# Schematic3.net
KiCad netlist of a schematic drawn in EAGLE
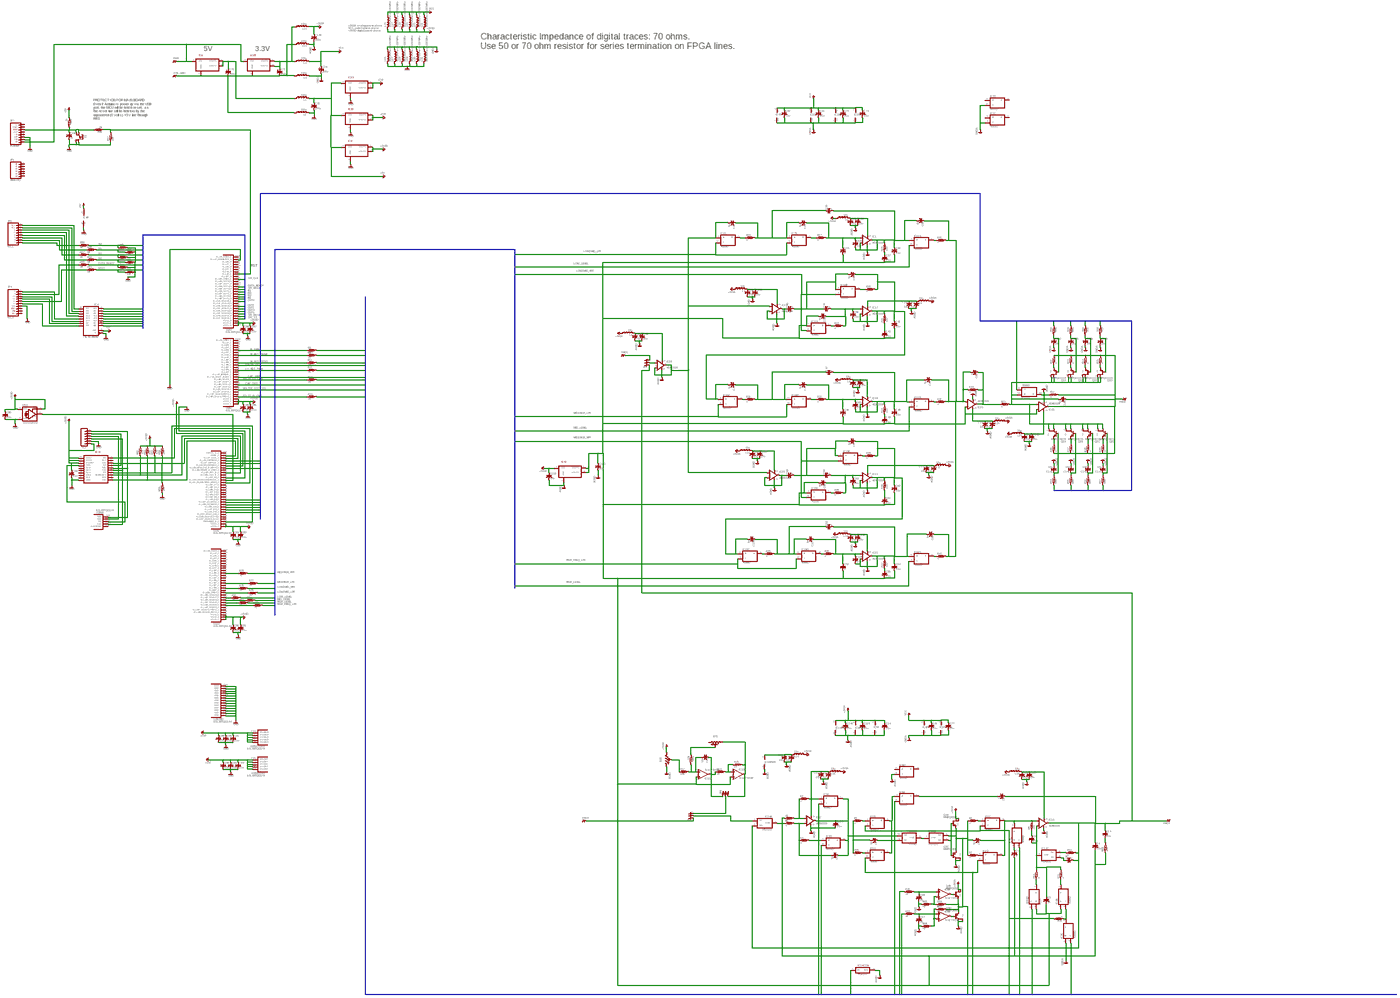
[diagram p0: schematic, sheet 1, overview]
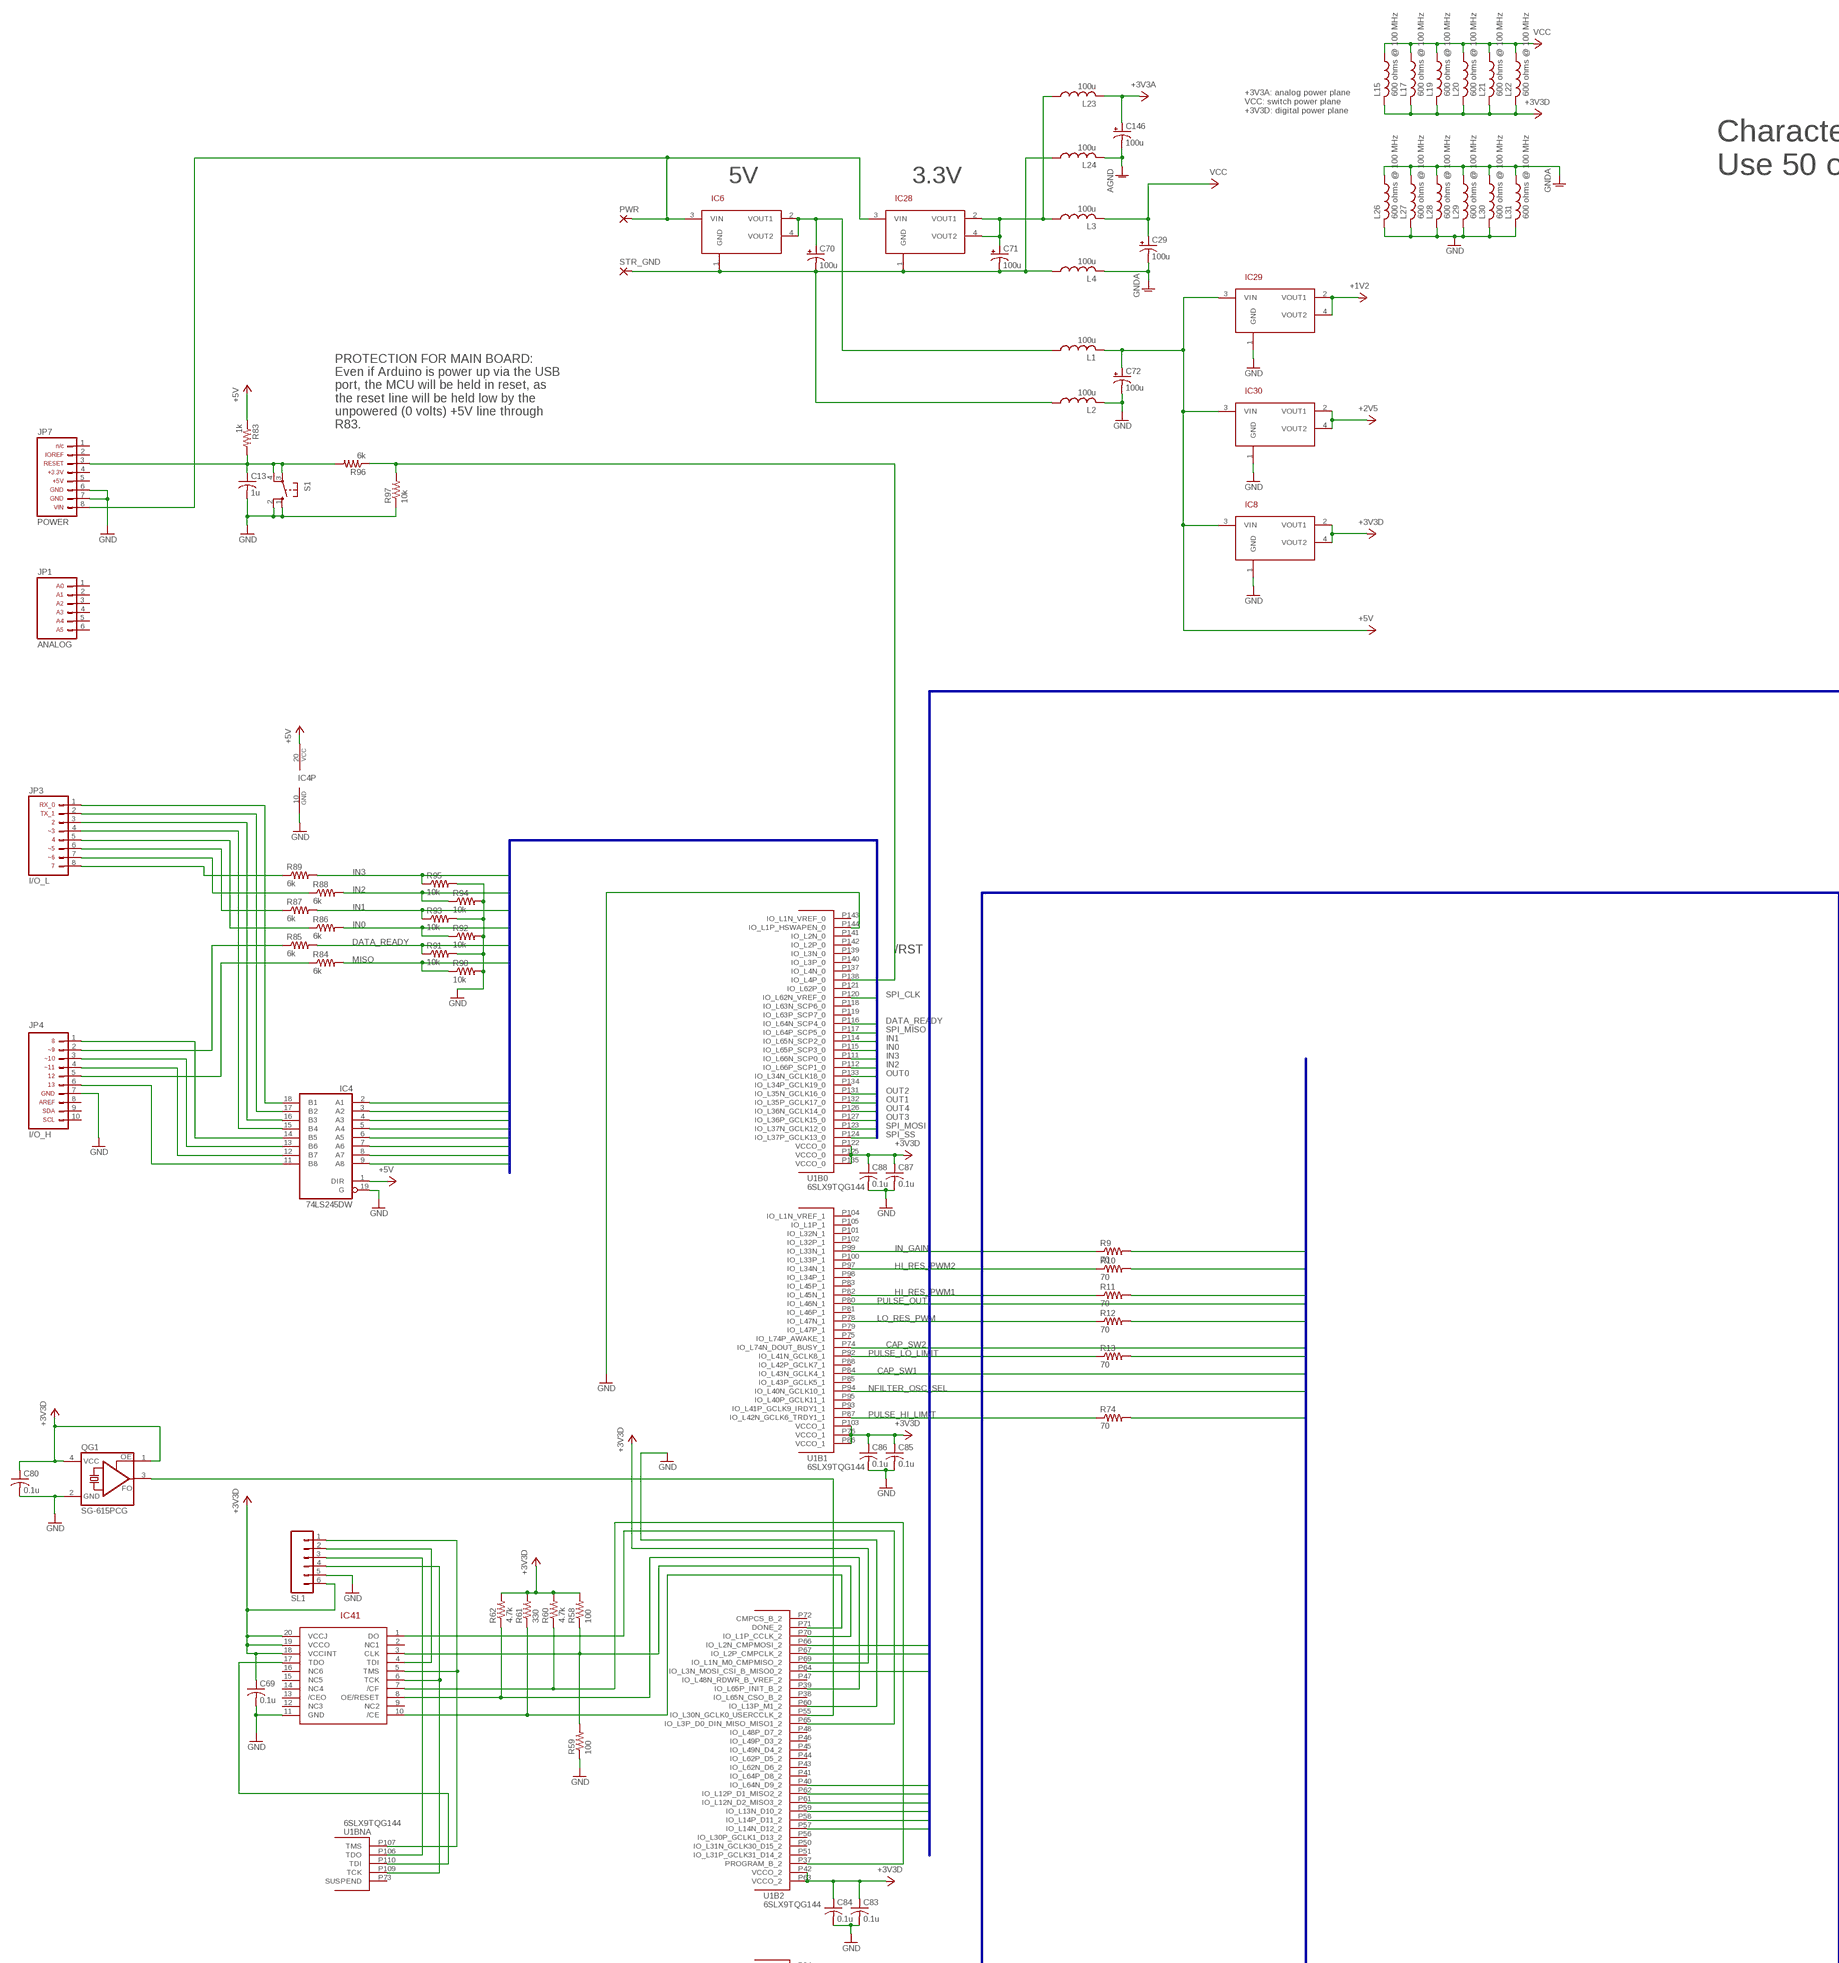
[diagram p1: schematic, sheet 1, part 1 of 6]
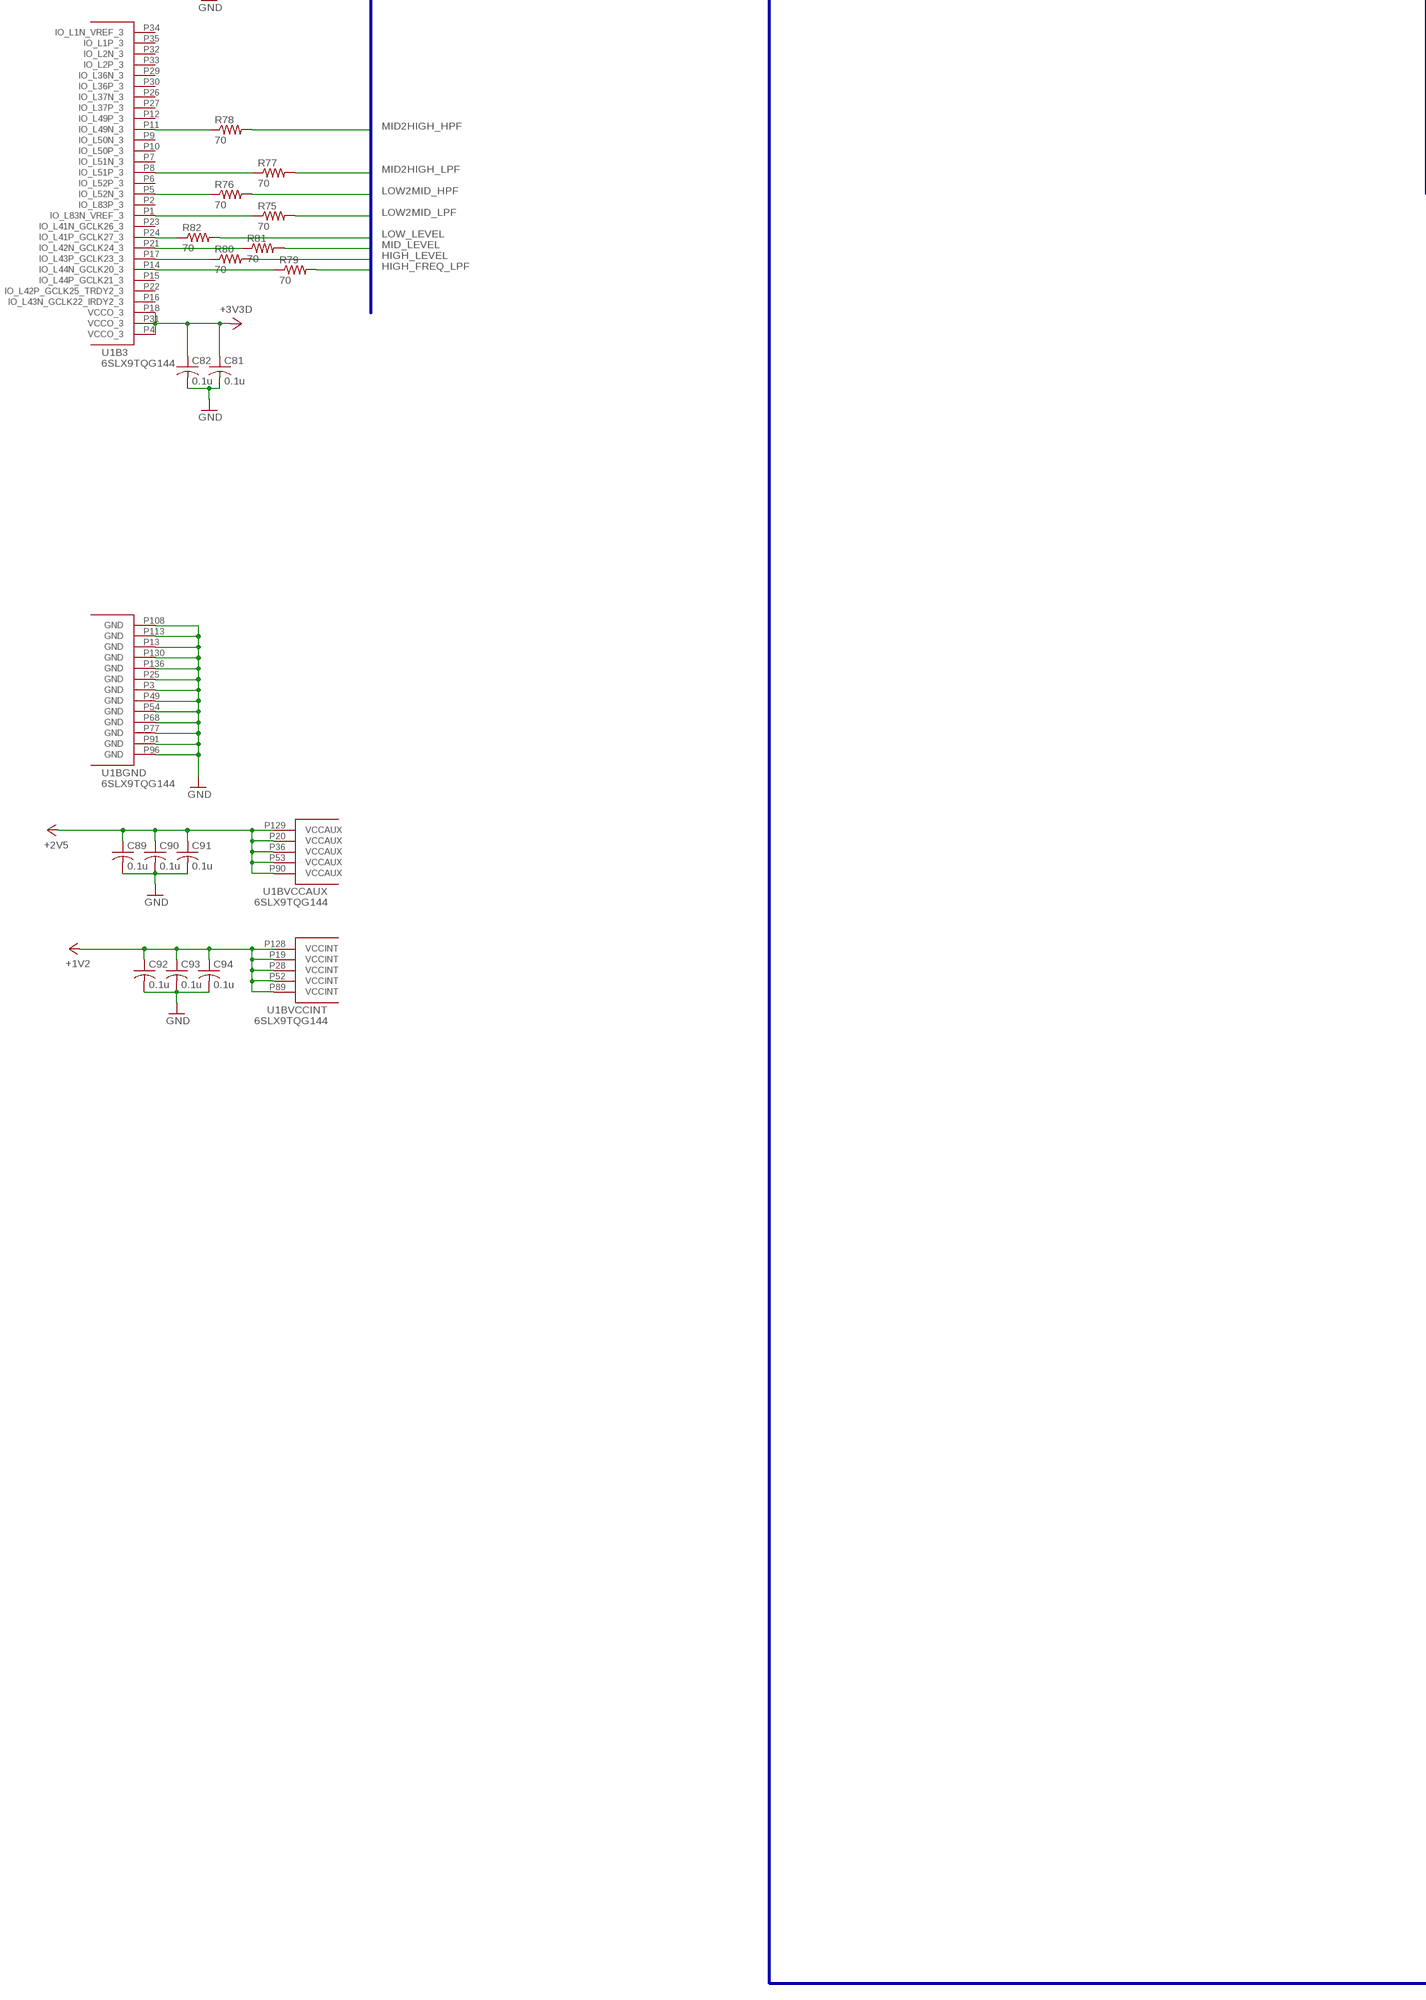
[diagram p2: schematic, sheet 1, part 2 of 6]
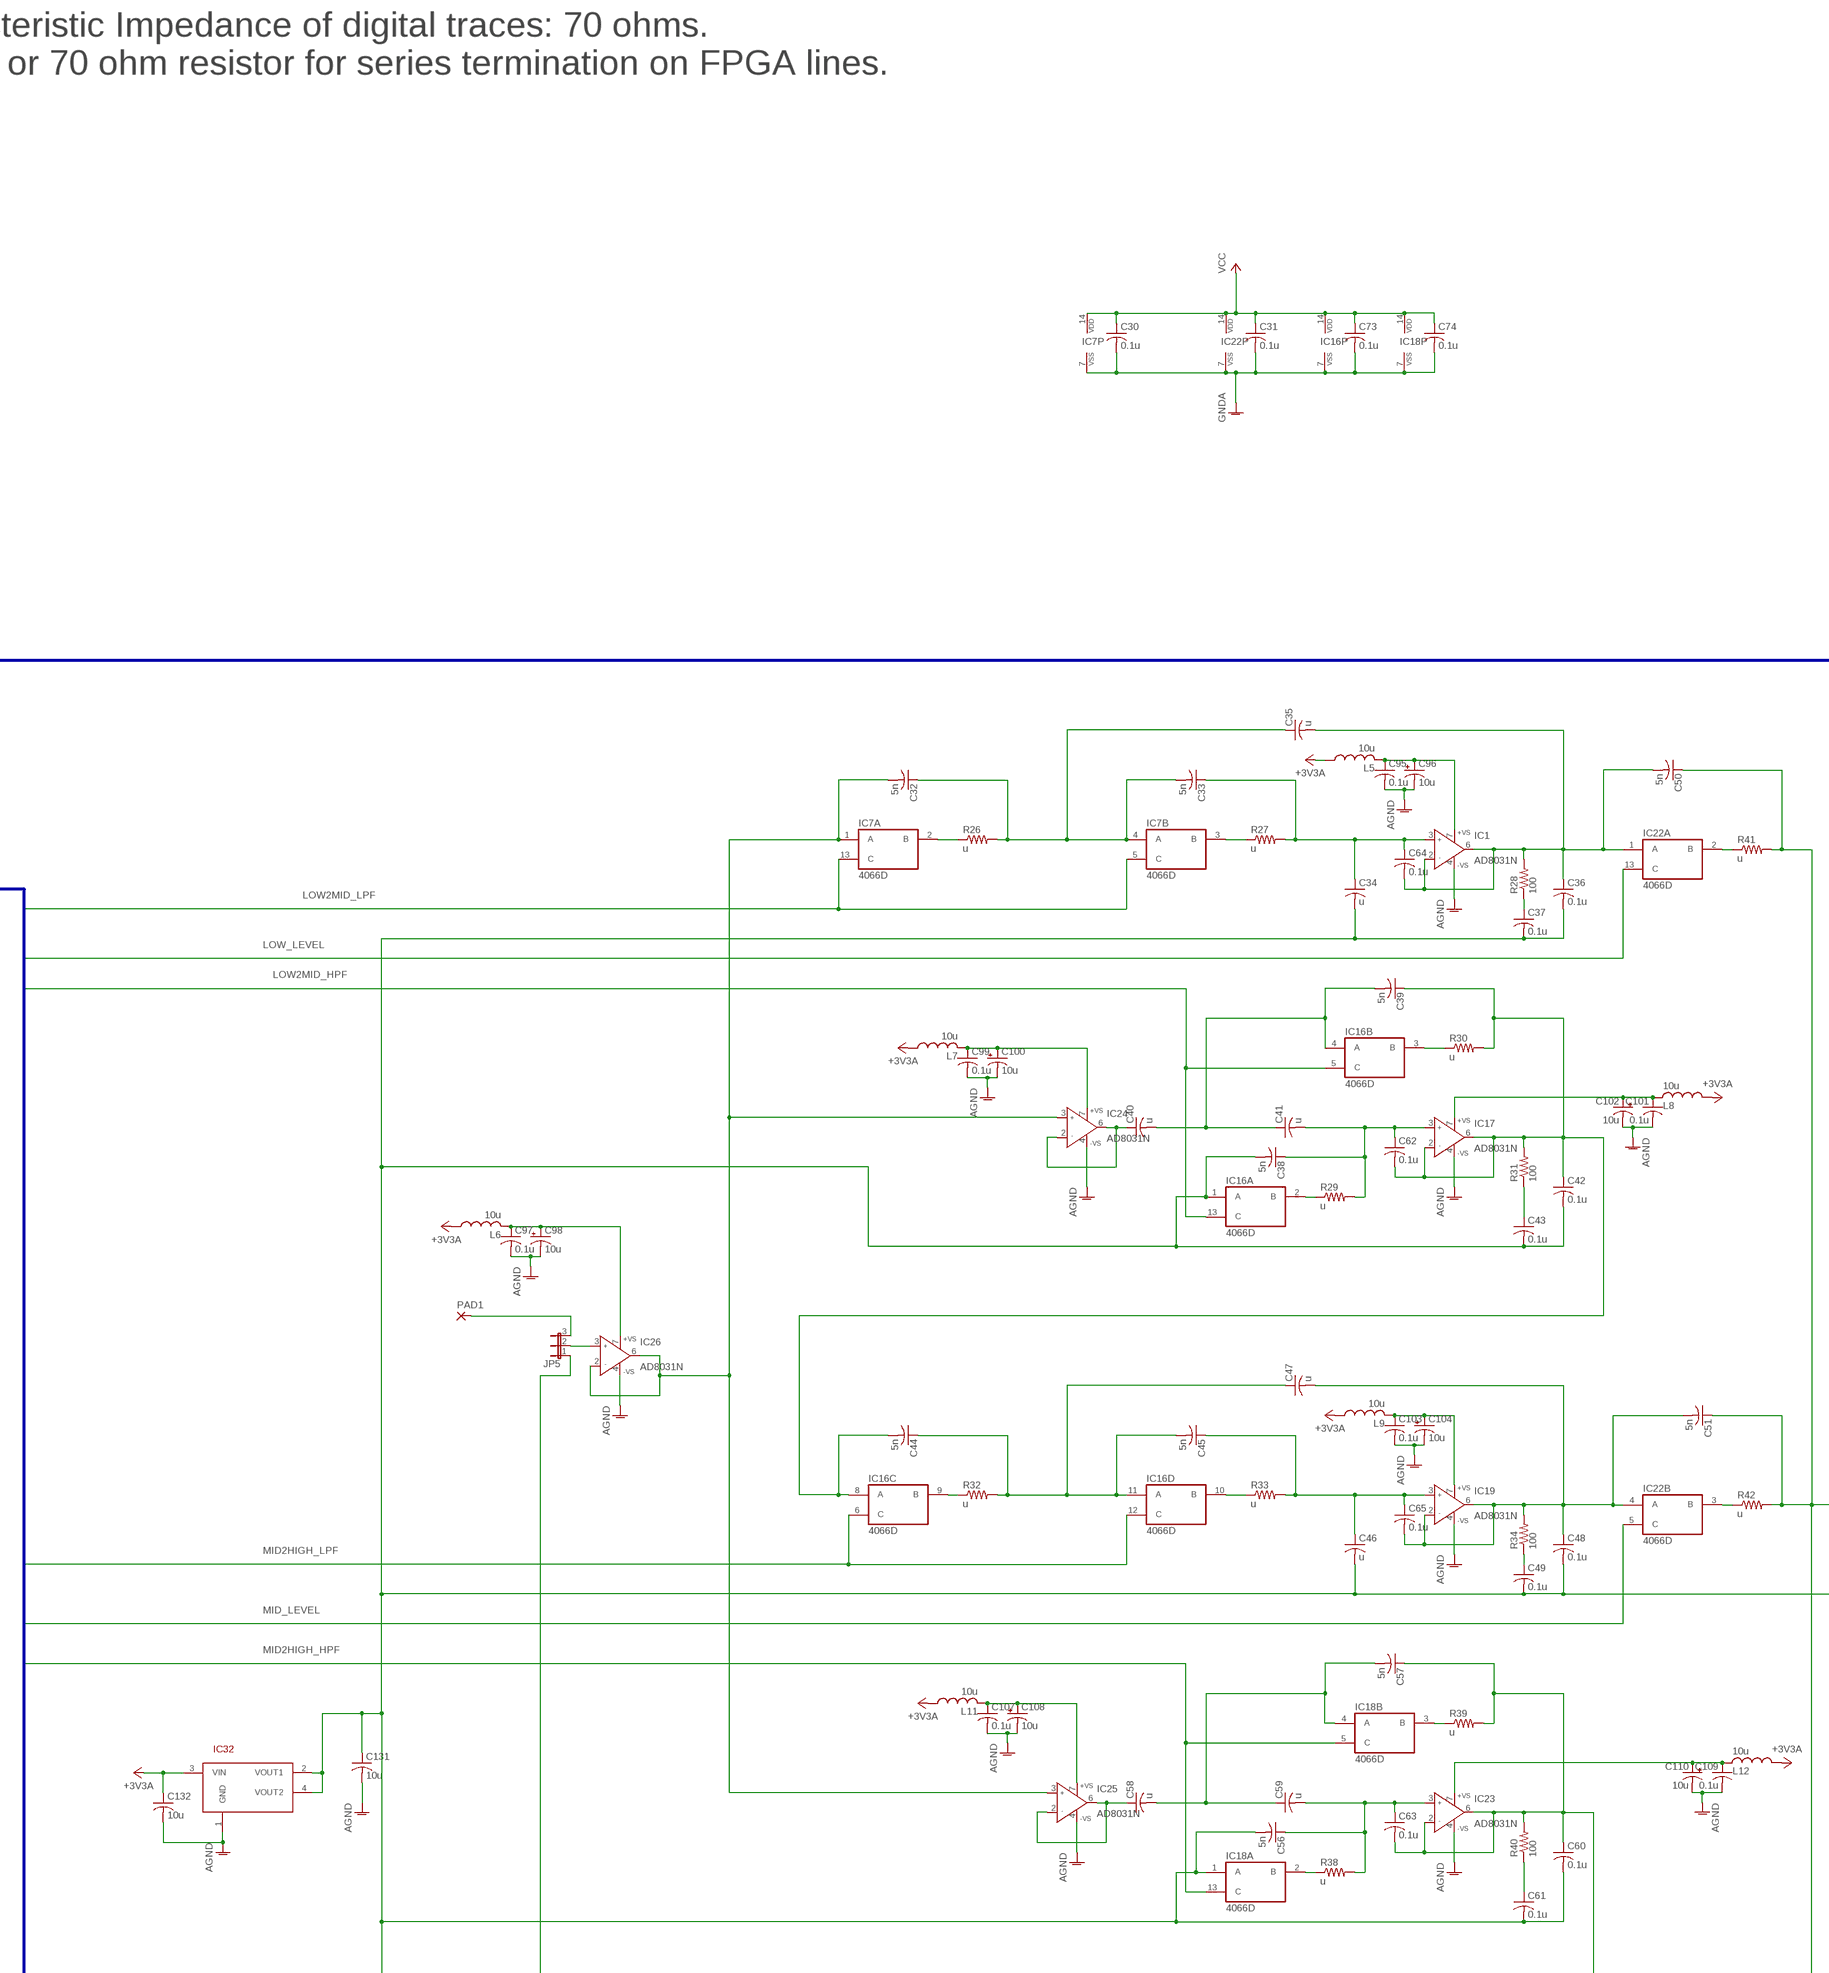
[diagram p3: schematic, sheet 1, part 3 of 6]
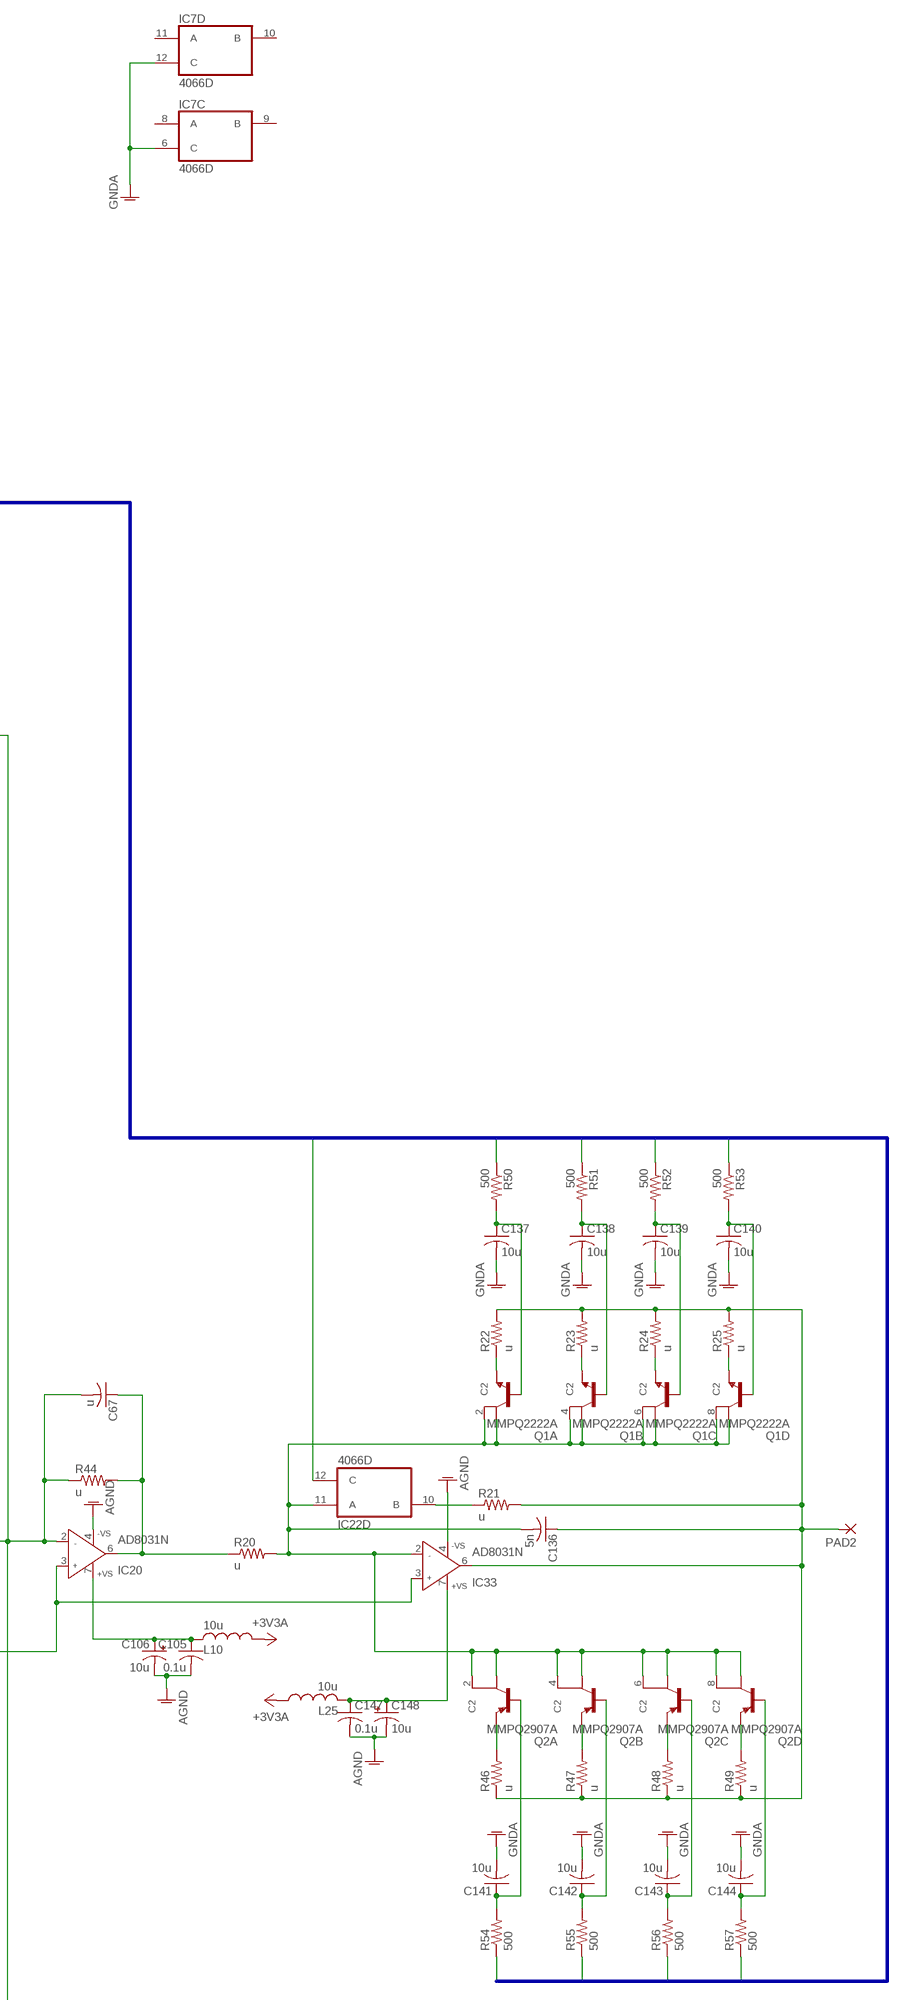
[diagram p4: schematic, sheet 1, part 4 of 6]
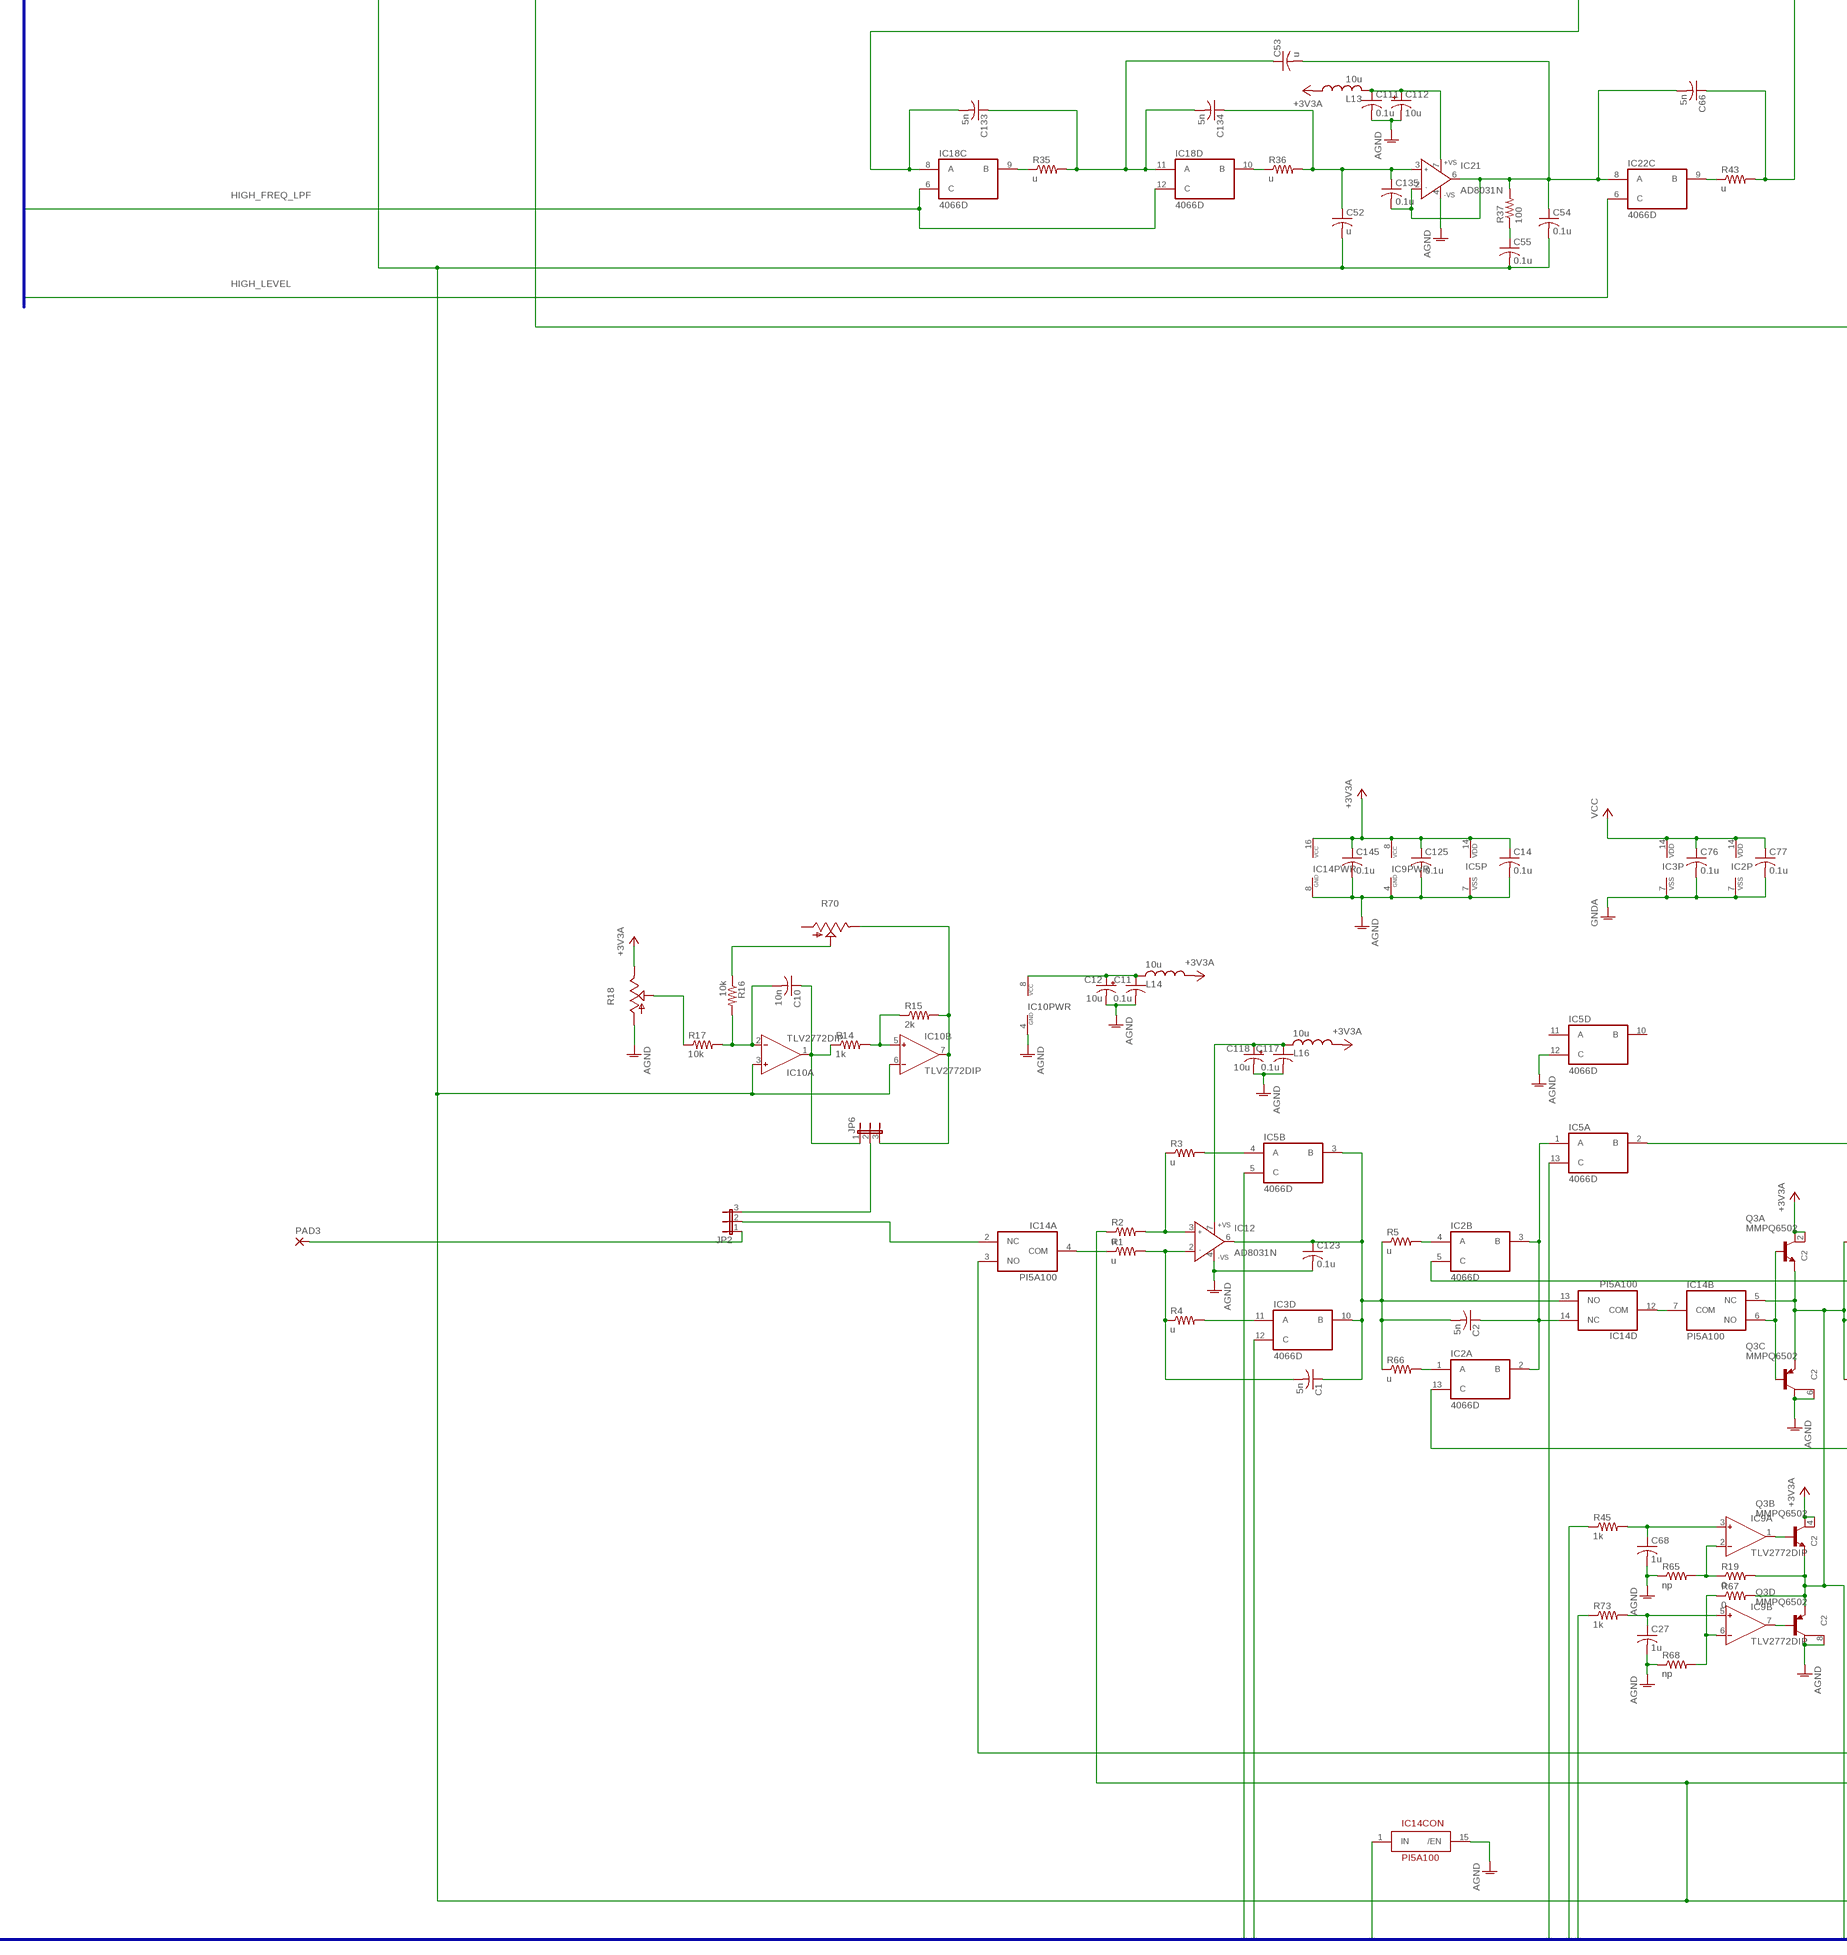
[diagram p5: schematic, sheet 1, part 5 of 6]
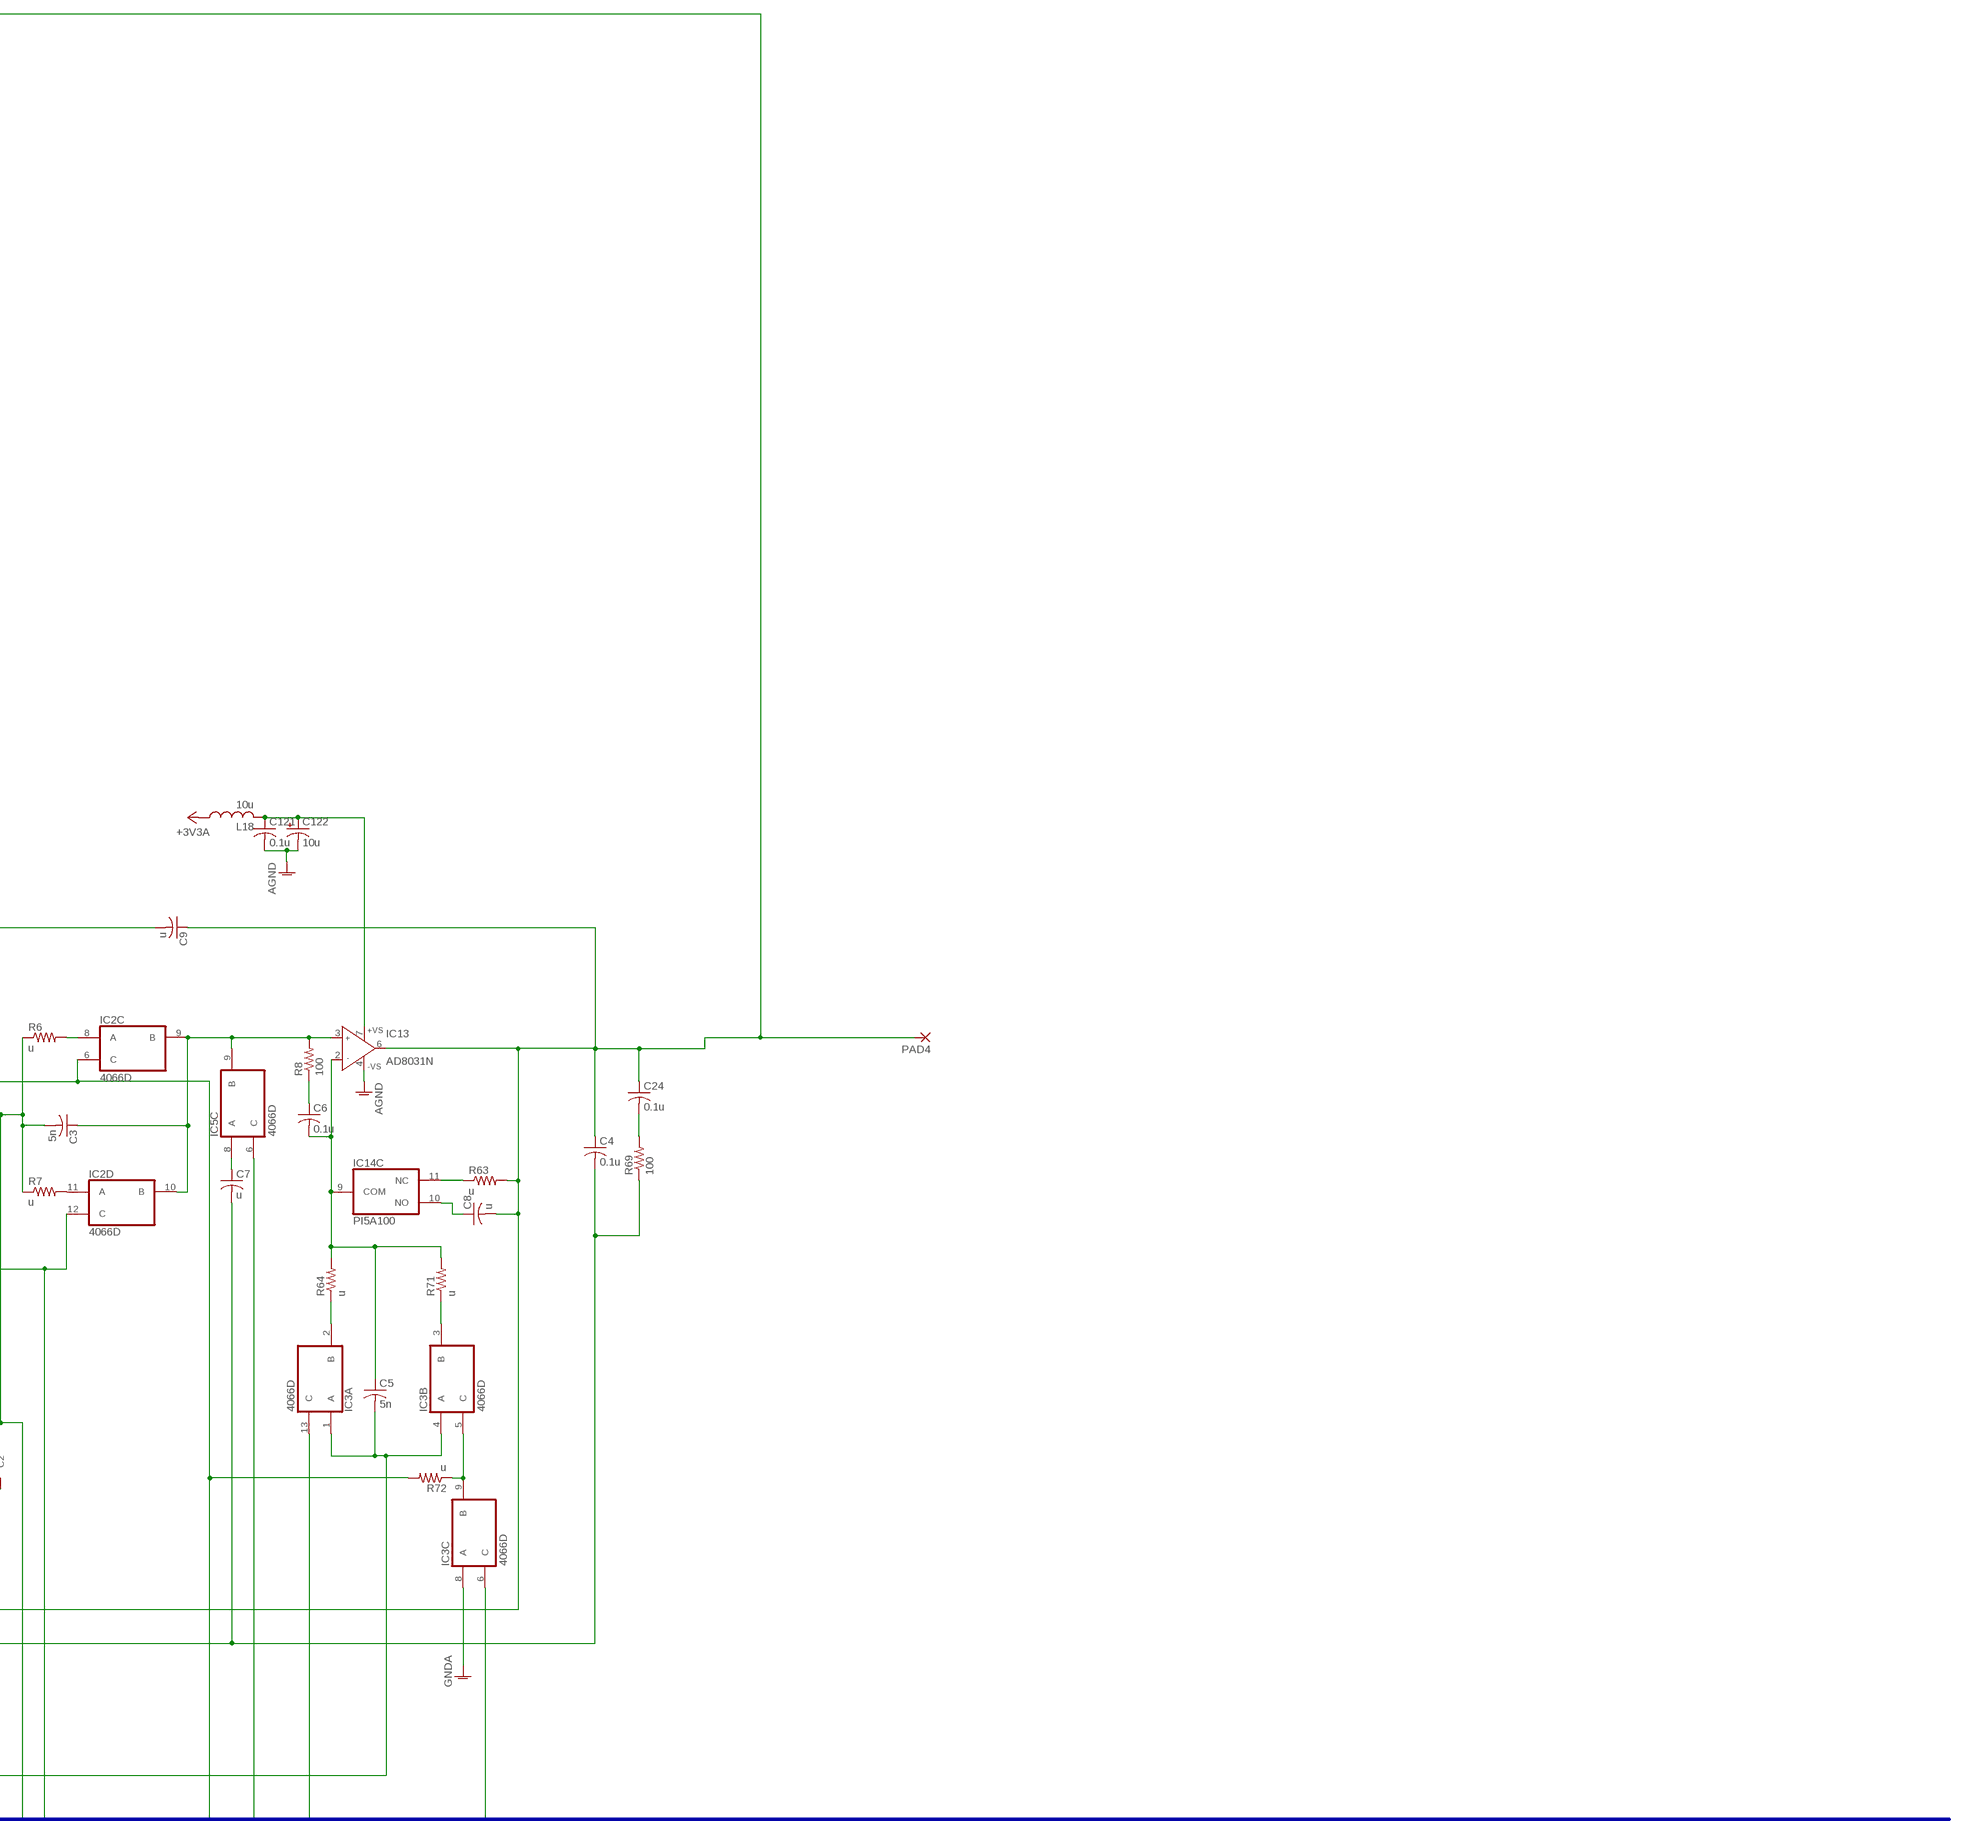
[diagram p6: schematic, sheet 1, part 6 of 6]

(export (version "E")
  (design (tool "Eeschema 10.0.6"))
  (components
    (comp (ref "C1")
      (value "5n")
      (footprint "eagle-import:C050-035X075")
      (libsource (lib "eagle-import") (part "C-US050-035X075"))
    )
    (comp (ref "C2")
      (value "5n")
      (footprint "eagle-import:C050-035X075")
      (libsource (lib "eagle-import") (part "C-US050-035X075"))
    )
    (comp (ref "C3")
      (value "5n")
      (footprint "eagle-import:C050-035X075")
      (libsource (lib "eagle-import") (part "C-US050-035X075"))
    )
    (comp (ref "C4")
      (value "0.1u")
      (footprint "eagle-import:C050-035X075")
      (libsource (lib "eagle-import") (part "C-US050-035X075"))
    )
    (comp (ref "C5")
      (value "5n")
      (footprint "eagle-import:C050-035X075")
      (libsource (lib "eagle-import") (part "C-US050-035X075"))
    )
    (comp (ref "C6")
      (value "0.1u")
      (footprint "eagle-import:C050-035X075")
      (libsource (lib "eagle-import") (part "C-US050-035X075"))
    )
    (comp (ref "C7")
      (value "u")
      (footprint "eagle-import:C050-035X075")
      (libsource (lib "eagle-import") (part "C-US050-035X075"))
    )
    (comp (ref "C8")
      (value "u")
      (footprint "eagle-import:C050-035X075")
      (libsource (lib "eagle-import") (part "C-US050-035X075"))
    )
    (comp (ref "C9")
      (value "u")
      (footprint "eagle-import:C050-035X075")
      (libsource (lib "eagle-import") (part "C-US050-035X075"))
    )
    (comp (ref "C10")
      (value "10n")
      (footprint "eagle-import:C050-035X075")
      (libsource (lib "eagle-import") (part "C-US050-035X075"))
    )
    (comp (ref "C11")
      (value "0.1u")
      (footprint "eagle-import:C0805")
      (libsource (lib "eagle-import") (part "C-USC0805"))
    )
    (comp (ref "C12")
      (value "10u")
      (footprint "eagle-import:A_3216-18R")
      (libsource (lib "eagle-import") (part "CPOL-USA/3216-18R"))
    )
    (comp (ref "C13")
      (value "1u")
      (footprint "eagle-import:C0805")
      (libsource (lib "eagle-import") (part "C-USC0805"))
    )
    (comp (ref "C14")
      (value "0.1u")
      (footprint "eagle-import:C0805")
      (libsource (lib "eagle-import") (part "C-USC0805"))
    )
    (comp (ref "C24")
      (value "0.1u")
      (footprint "eagle-import:C050-035X075")
      (libsource (lib "eagle-import") (part "C-US050-035X075"))
    )
    (comp (ref "C27")
      (value "1u")
      (footprint "eagle-import:C0805")
      (libsource (lib "eagle-import") (part "C-USC0805"))
    )
    (comp (ref "C29")
      (value "100u")
      (footprint "eagle-import:B_3528-21R")
      (libsource (lib "eagle-import") (part "CPOL-USB/3528-21R"))
    )
    (comp (ref "C30")
      (value "0.1u")
      (footprint "eagle-import:C0805")
      (libsource (lib "eagle-import") (part "C-USC0805"))
    )
    (comp (ref "C31")
      (value "0.1u")
      (footprint "eagle-import:C0805")
      (libsource (lib "eagle-import") (part "C-USC0805"))
    )
    (comp (ref "C32")
      (value "5n")
      (footprint "eagle-import:C050-035X075")
      (libsource (lib "eagle-import") (part "C-US050-035X075"))
    )
    (comp (ref "C33")
      (value "5n")
      (footprint "eagle-import:C050-035X075")
      (libsource (lib "eagle-import") (part "C-US050-035X075"))
    )
    (comp (ref "C34")
      (value "u")
      (footprint "eagle-import:C050-035X075")
      (libsource (lib "eagle-import") (part "C-US050-035X075"))
    )
    (comp (ref "C35")
      (value "u")
      (footprint "eagle-import:C050-035X075")
      (libsource (lib "eagle-import") (part "C-US050-035X075"))
    )
    (comp (ref "C36")
      (value "0.1u")
      (footprint "eagle-import:C050-035X075")
      (libsource (lib "eagle-import") (part "C-US050-035X075"))
    )
    (comp (ref "C37")
      (value "0.1u")
      (footprint "eagle-import:C050-035X075")
      (libsource (lib "eagle-import") (part "C-US050-035X075"))
    )
    (comp (ref "C38")
      (value "5n")
      (footprint "eagle-import:C050-035X075")
      (libsource (lib "eagle-import") (part "C-US050-035X075"))
    )
    (comp (ref "C39")
      (value "5n")
      (footprint "eagle-import:C050-035X075")
      (libsource (lib "eagle-import") (part "C-US050-035X075"))
    )
    (comp (ref "C40")
      (value "u")
      (footprint "eagle-import:C050-035X075")
      (libsource (lib "eagle-import") (part "C-US050-035X075"))
    )
    (comp (ref "C41")
      (value "u")
      (footprint "eagle-import:C050-035X075")
      (libsource (lib "eagle-import") (part "C-US050-035X075"))
    )
    (comp (ref "C42")
      (value "0.1u")
      (footprint "eagle-import:C050-035X075")
      (libsource (lib "eagle-import") (part "C-US050-035X075"))
    )
    (comp (ref "C43")
      (value "0.1u")
      (footprint "eagle-import:C050-035X075")
      (libsource (lib "eagle-import") (part "C-US050-035X075"))
    )
    (comp (ref "C44")
      (value "5n")
      (footprint "eagle-import:C050-035X075")
      (libsource (lib "eagle-import") (part "C-US050-035X075"))
    )
    (comp (ref "C45")
      (value "5n")
      (footprint "eagle-import:C050-035X075")
      (libsource (lib "eagle-import") (part "C-US050-035X075"))
    )
    (comp (ref "C46")
      (value "u")
      (footprint "eagle-import:C050-035X075")
      (libsource (lib "eagle-import") (part "C-US050-035X075"))
    )
    (comp (ref "C47")
      (value "u")
      (footprint "eagle-import:C050-035X075")
      (libsource (lib "eagle-import") (part "C-US050-035X075"))
    )
    (comp (ref "C48")
      (value "0.1u")
      (footprint "eagle-import:C050-035X075")
      (libsource (lib "eagle-import") (part "C-US050-035X075"))
    )
    (comp (ref "C49")
      (value "0.1u")
      (footprint "eagle-import:C050-035X075")
      (libsource (lib "eagle-import") (part "C-US050-035X075"))
    )
    (comp (ref "C50")
      (value "5n")
      (footprint "eagle-import:C050-035X075")
      (libsource (lib "eagle-import") (part "C-US050-035X075"))
    )
    (comp (ref "C51")
      (value "5n")
      (footprint "eagle-import:C050-035X075")
      (libsource (lib "eagle-import") (part "C-US050-035X075"))
    )
    (comp (ref "C52")
      (value "u")
      (footprint "eagle-import:C050-035X075")
      (libsource (lib "eagle-import") (part "C-US050-035X075"))
    )
    (comp (ref "C53")
      (value "u")
      (footprint "eagle-import:C050-035X075")
      (libsource (lib "eagle-import") (part "C-US050-035X075"))
    )
    (comp (ref "C54")
      (value "0.1u")
      (footprint "eagle-import:C050-035X075")
      (libsource (lib "eagle-import") (part "C-US050-035X075"))
    )
    (comp (ref "C55")
      (value "0.1u")
      (footprint "eagle-import:C050-035X075")
      (libsource (lib "eagle-import") (part "C-US050-035X075"))
    )
    (comp (ref "C56")
      (value "5n")
      (footprint "eagle-import:C050-035X075")
      (libsource (lib "eagle-import") (part "C-US050-035X075"))
    )
    (comp (ref "C57")
      (value "5n")
      (footprint "eagle-import:C050-035X075")
      (libsource (lib "eagle-import") (part "C-US050-035X075"))
    )
    (comp (ref "C58")
      (value "u")
      (footprint "eagle-import:C050-035X075")
      (libsource (lib "eagle-import") (part "C-US050-035X075"))
    )
    (comp (ref "C59")
      (value "u")
      (footprint "eagle-import:C050-035X075")
      (libsource (lib "eagle-import") (part "C-US050-035X075"))
    )
    (comp (ref "C60")
      (value "0.1u")
      (footprint "eagle-import:C050-035X075")
      (libsource (lib "eagle-import") (part "C-US050-035X075"))
    )
    (comp (ref "C61")
      (value "0.1u")
      (footprint "eagle-import:C050-035X075")
      (libsource (lib "eagle-import") (part "C-US050-035X075"))
    )
    (comp (ref "C62")
      (value "0.1u")
      (footprint "eagle-import:C050-035X075")
      (libsource (lib "eagle-import") (part "C-US050-035X075"))
    )
    (comp (ref "C63")
      (value "0.1u")
      (footprint "eagle-import:C050-035X075")
      (libsource (lib "eagle-import") (part "C-US050-035X075"))
    )
    (comp (ref "C64")
      (value "0.1u")
      (footprint "eagle-import:C050-035X075")
      (libsource (lib "eagle-import") (part "C-US050-035X075"))
    )
    (comp (ref "C65")
      (value "0.1u")
      (footprint "eagle-import:C050-035X075")
      (libsource (lib "eagle-import") (part "C-US050-035X075"))
    )
    (comp (ref "C66")
      (value "5n")
      (footprint "eagle-import:C050-035X075")
      (libsource (lib "eagle-import") (part "C-US050-035X075"))
    )
    (comp (ref "C67")
      (value "u")
      (footprint "eagle-import:C050-035X075")
      (libsource (lib "eagle-import") (part "C-US050-035X075"))
    )
    (comp (ref "C68")
      (value "1u")
      (footprint "eagle-import:C0805")
      (libsource (lib "eagle-import") (part "C-USC0805"))
    )
    (comp (ref "C69")
      (value "0.1u")
      (footprint "eagle-import:C0805")
      (libsource (lib "eagle-import") (part "C-USC0805"))
    )
    (comp (ref "C70")
      (value "100u")
      (footprint "eagle-import:CT3528")
      (libsource (lib "eagle-import") (part "CPOL-USCT3528"))
    )
    (comp (ref "C71")
      (value "100u")
      (footprint "eagle-import:CT3528")
      (libsource (lib "eagle-import") (part "CPOL-USCT3528"))
    )
    (comp (ref "C72")
      (value "100u")
      (footprint "eagle-import:B_3528-21R")
      (libsource (lib "eagle-import") (part "CPOL-USB/3528-21R"))
    )
    (comp (ref "C73")
      (value "0.1u")
      (footprint "eagle-import:C0805")
      (libsource (lib "eagle-import") (part "C-USC0805"))
    )
    (comp (ref "C74")
      (value "0.1u")
      (footprint "eagle-import:C0805")
      (libsource (lib "eagle-import") (part "C-USC0805"))
    )
    (comp (ref "C76")
      (value "0.1u")
      (footprint "eagle-import:C0805")
      (libsource (lib "eagle-import") (part "C-USC0805"))
    )
    (comp (ref "C77")
      (value "0.1u")
      (footprint "eagle-import:C0805")
      (libsource (lib "eagle-import") (part "C-USC0805"))
    )
    (comp (ref "C80")
      (value "0.1u")
      (footprint "eagle-import:C0805")
      (libsource (lib "eagle-import") (part "C-USC0805"))
    )
    (comp (ref "C81")
      (value "0.1u")
      (footprint "eagle-import:C0805")
      (libsource (lib "eagle-import") (part "C-USC0805"))
    )
    (comp (ref "C82")
      (value "0.1u")
      (footprint "eagle-import:C0805")
      (libsource (lib "eagle-import") (part "C-USC0805"))
    )
    (comp (ref "C83")
      (value "0.1u")
      (footprint "eagle-import:C0805")
      (libsource (lib "eagle-import") (part "C-USC0805"))
    )
    (comp (ref "C84")
      (value "0.1u")
      (footprint "eagle-import:C0805")
      (libsource (lib "eagle-import") (part "C-USC0805"))
    )
    (comp (ref "C85")
      (value "0.1u")
      (footprint "eagle-import:C0805")
      (libsource (lib "eagle-import") (part "C-USC0805"))
    )
    (comp (ref "C86")
      (value "0.1u")
      (footprint "eagle-import:C0805")
      (libsource (lib "eagle-import") (part "C-USC0805"))
    )
    (comp (ref "C87")
      (value "0.1u")
      (footprint "eagle-import:C0805")
      (libsource (lib "eagle-import") (part "C-USC0805"))
    )
    (comp (ref "C88")
      (value "0.1u")
      (footprint "eagle-import:C0805")
      (libsource (lib "eagle-import") (part "C-USC0805"))
    )
    (comp (ref "C89")
      (value "0.1u")
      (footprint "eagle-import:C0805")
      (libsource (lib "eagle-import") (part "C-USC0805"))
    )
    (comp (ref "C90")
      (value "0.1u")
      (footprint "eagle-import:C0805")
      (libsource (lib "eagle-import") (part "C-USC0805"))
    )
    (comp (ref "C91")
      (value "0.1u")
      (footprint "eagle-import:C0805")
      (libsource (lib "eagle-import") (part "C-USC0805"))
    )
    (comp (ref "C92")
      (value "0.1u")
      (footprint "eagle-import:C0805")
      (libsource (lib "eagle-import") (part "C-USC0805"))
    )
    (comp (ref "C93")
      (value "0.1u")
      (footprint "eagle-import:C0805")
      (libsource (lib "eagle-import") (part "C-USC0805"))
    )
    (comp (ref "C94")
      (value "0.1u")
      (footprint "eagle-import:C0805")
      (libsource (lib "eagle-import") (part "C-USC0805"))
    )
    (comp (ref "C95")
      (value "0.1u")
      (footprint "eagle-import:C0805")
      (libsource (lib "eagle-import") (part "C-USC0805"))
    )
    (comp (ref "C96")
      (value "10u")
      (footprint "eagle-import:A_3216-18R")
      (libsource (lib "eagle-import") (part "CPOL-USA/3216-18R"))
    )
    (comp (ref "C97")
      (value "0.1u")
      (footprint "eagle-import:C0805")
      (libsource (lib "eagle-import") (part "C-USC0805"))
    )
    (comp (ref "C98")
      (value "10u")
      (footprint "eagle-import:A_3216-18R")
      (libsource (lib "eagle-import") (part "CPOL-USA/3216-18R"))
    )
    (comp (ref "C99")
      (value "0.1u")
      (footprint "eagle-import:C0805")
      (libsource (lib "eagle-import") (part "C-USC0805"))
    )
    (comp (ref "C100")
      (value "10u")
      (footprint "eagle-import:A_3216-18R")
      (libsource (lib "eagle-import") (part "CPOL-USA/3216-18R"))
    )
    (comp (ref "C101")
      (value "0.1u")
      (footprint "eagle-import:C0805")
      (libsource (lib "eagle-import") (part "C-USC0805"))
    )
    (comp (ref "C102")
      (value "10u")
      (footprint "eagle-import:A_3216-18R")
      (libsource (lib "eagle-import") (part "CPOL-USA/3216-18R"))
    )
    (comp (ref "C103")
      (value "0.1u")
      (footprint "eagle-import:C0805")
      (libsource (lib "eagle-import") (part "C-USC0805"))
    )
    (comp (ref "C104")
      (value "10u")
      (footprint "eagle-import:A_3216-18R")
      (libsource (lib "eagle-import") (part "CPOL-USA/3216-18R"))
    )
    (comp (ref "C105")
      (value "0.1u")
      (footprint "eagle-import:C0805")
      (libsource (lib "eagle-import") (part "C-USC0805"))
    )
    (comp (ref "C106")
      (value "10u")
      (footprint "eagle-import:A_3216-18R")
      (libsource (lib "eagle-import") (part "CPOL-USA/3216-18R"))
    )
    (comp (ref "C107")
      (value "0.1u")
      (footprint "eagle-import:C0805")
      (libsource (lib "eagle-import") (part "C-USC0805"))
    )
    (comp (ref "C108")
      (value "10u")
      (footprint "eagle-import:A_3216-18R")
      (libsource (lib "eagle-import") (part "CPOL-USA/3216-18R"))
    )
    (comp (ref "C109")
      (value "0.1u")
      (footprint "eagle-import:C0805")
      (libsource (lib "eagle-import") (part "C-USC0805"))
    )
    (comp (ref "C110")
      (value "10u")
      (footprint "eagle-import:A_3216-18R")
      (libsource (lib "eagle-import") (part "CPOL-USA/3216-18R"))
    )
    (comp (ref "C111")
      (value "0.1u")
      (footprint "eagle-import:C0805")
      (libsource (lib "eagle-import") (part "C-USC0805"))
    )
    (comp (ref "C112")
      (value "10u")
      (footprint "eagle-import:A_3216-18R")
      (libsource (lib "eagle-import") (part "CPOL-USA/3216-18R"))
    )
    (comp (ref "C117")
      (value "0.1u")
      (footprint "eagle-import:C0805")
      (libsource (lib "eagle-import") (part "C-USC0805"))
    )
    (comp (ref "C118")
      (value "10u")
      (footprint "eagle-import:A_3216-18R")
      (libsource (lib "eagle-import") (part "CPOL-USA/3216-18R"))
    )
    (comp (ref "C121")
      (value "0.1u")
      (footprint "eagle-import:C0805")
      (libsource (lib "eagle-import") (part "C-USC0805"))
    )
    (comp (ref "C122")
      (value "10u")
      (footprint "eagle-import:A_3216-18R")
      (libsource (lib "eagle-import") (part "CPOL-USA/3216-18R"))
    )
    (comp (ref "C123")
      (value "0.1u")
      (footprint "eagle-import:C050-035X075")
      (libsource (lib "eagle-import") (part "C-US050-035X075"))
    )
    (comp (ref "C125")
      (value "0.1u")
      (footprint "eagle-import:C0805")
      (libsource (lib "eagle-import") (part "C-USC0805"))
    )
    (comp (ref "C131")
      (value "10u")
      (footprint "eagle-import:C0805")
      (libsource (lib "eagle-import") (part "C-USC0805"))
    )
    (comp (ref "C132")
      (value "10u")
      (footprint "eagle-import:C0805")
      (libsource (lib "eagle-import") (part "C-USC0805"))
    )
    (comp (ref "C133")
      (value "5n")
      (footprint "eagle-import:C050-035X075")
      (libsource (lib "eagle-import") (part "C-US050-035X075"))
    )
    (comp (ref "C134")
      (value "5n")
      (footprint "eagle-import:C050-035X075")
      (libsource (lib "eagle-import") (part "C-US050-035X075"))
    )
    (comp (ref "C135")
      (value "0.1u")
      (footprint "eagle-import:C050-035X075")
      (libsource (lib "eagle-import") (part "C-US050-035X075"))
    )
    (comp (ref "C136")
      (value "5n")
      (footprint "eagle-import:C050-035X075")
      (libsource (lib "eagle-import") (part "C-US050-035X075"))
    )
    (comp (ref "C137")
      (value "10u")
      (footprint "eagle-import:C050-035X075")
      (libsource (lib "eagle-import") (part "C-US050-035X075"))
    )
    (comp (ref "C138")
      (value "10u")
      (footprint "eagle-import:C050-035X075")
      (libsource (lib "eagle-import") (part "C-US050-035X075"))
    )
    (comp (ref "C139")
      (value "10u")
      (footprint "eagle-import:C050-035X075")
      (libsource (lib "eagle-import") (part "C-US050-035X075"))
    )
    (comp (ref "C140")
      (value "10u")
      (footprint "eagle-import:C050-035X075")
      (libsource (lib "eagle-import") (part "C-US050-035X075"))
    )
    (comp (ref "C141")
      (value "10u")
      (footprint "eagle-import:C050-035X075")
      (libsource (lib "eagle-import") (part "C-US050-035X075"))
    )
    (comp (ref "C142")
      (value "10u")
      (footprint "eagle-import:C050-035X075")
      (libsource (lib "eagle-import") (part "C-US050-035X075"))
    )
    (comp (ref "C143")
      (value "10u")
      (footprint "eagle-import:C050-035X075")
      (libsource (lib "eagle-import") (part "C-US050-035X075"))
    )
    (comp (ref "C144")
      (value "10u")
      (footprint "eagle-import:C050-035X075")
      (libsource (lib "eagle-import") (part "C-US050-035X075"))
    )
    (comp (ref "C145")
      (value "0.1u")
      (footprint "eagle-import:C0805")
      (libsource (lib "eagle-import") (part "C-USC0805"))
    )
    (comp (ref "C146")
      (value "100u")
      (footprint "eagle-import:B_3528-21R")
      (libsource (lib "eagle-import") (part "CPOL-USB/3528-21R"))
    )
    (comp (ref "C147")
      (value "0.1u")
      (footprint "eagle-import:C0805")
      (libsource (lib "eagle-import") (part "C-USC0805"))
    )
    (comp (ref "C148")
      (value "10u")
      (footprint "eagle-import:A_3216-18R")
      (libsource (lib "eagle-import") (part "CPOL-USA/3216-18R"))
    )
    (comp (ref "IC1")
      (value "AD8031N")
      (footprint "eagle-import:DIL08")
      (fields (field (name "MPN") "AD8031BNZ"))
      (libsource (lib "eagle-import") (part "AD8031N"))
    )
    (comp (ref "IC2")
      (value "4066D")
      (footprint "eagle-import:SO14")
      (libsource (lib "eagle-import") (part "4066D"))
    )
    (comp (ref "IC3")
      (value "4066D")
      (footprint "eagle-import:SO14")
      (libsource (lib "eagle-import") (part "4066D"))
    )
    (comp (ref "IC4")
      (value "74LS245DW")
      (footprint "eagle-import:SO20W")
      (libsource (lib "eagle-import") (part "74245DWLS"))
    )
    (comp (ref "IC5")
      (value "4066D")
      (footprint "eagle-import:SO14")
      (libsource (lib "eagle-import") (part "4066D"))
    )
    (comp (ref "IC6")
      (value "TLV1117")
      (footprint "eagle-import:SOT223-4")
      (libsource (lib "eagle-import") (part "texas2_TLV1117"))
    )
    (comp (ref "IC7")
      (value "4066D")
      (footprint "eagle-import:SO14")
      (libsource (lib "eagle-import") (part "4066D"))
    )
    (comp (ref "IC8")
      (value "TLV1117")
      (footprint "eagle-import:SOT223-4")
      (libsource (lib "eagle-import") (part "TLV1117"))
    )
    (comp (ref "IC9")
      (value "TLV2772DIP")
      (footprint "eagle-import:DIL08")
      (libsource (lib "eagle-import") (part "TLV2772DIP"))
    )
    (comp (ref "IC10")
      (value "TLV2772DIP")
      (footprint "eagle-import:DIL08")
      (libsource (lib "eagle-import") (part "TLV2772DIP"))
    )
    (comp (ref "IC12")
      (value "AD8031N")
      (footprint "eagle-import:DIL08")
      (fields (field (name "MPN") "AD8031BNZ"))
      (libsource (lib "eagle-import") (part "AD8031N"))
    )
    (comp (ref "IC13")
      (value "AD8031N")
      (footprint "eagle-import:DIL08")
      (fields (field (name "MPN") "AD8031BNZ"))
      (libsource (lib "eagle-import") (part "AD8031N"))
    )
    (comp (ref "IC14")
      (value "PI5A100")
      (footprint "eagle-import:SO-16")
      (libsource (lib "eagle-import") (part "PI5A100"))
    )
    (comp (ref "IC16")
      (value "4066D")
      (footprint "eagle-import:SO14")
      (libsource (lib "eagle-import") (part "4066D"))
    )
    (comp (ref "IC17")
      (value "AD8031N")
      (footprint "eagle-import:DIL08")
      (fields (field (name "MPN") "AD8031BNZ"))
      (libsource (lib "eagle-import") (part "AD8031N"))
    )
    (comp (ref "IC18")
      (value "4066D")
      (footprint "eagle-import:SO14")
      (libsource (lib "eagle-import") (part "4066D"))
    )
    (comp (ref "IC19")
      (value "AD8031N")
      (footprint "eagle-import:DIL08")
      (fields (field (name "MPN") "AD8031BNZ"))
      (libsource (lib "eagle-import") (part "AD8031N"))
    )
    (comp (ref "IC20")
      (value "AD8031N")
      (footprint "eagle-import:DIL08")
      (fields (field (name "MPN") "AD8031BNZ"))
      (libsource (lib "eagle-import") (part "AD8031N"))
    )
    (comp (ref "IC21")
      (value "AD8031N")
      (footprint "eagle-import:DIL08")
      (fields (field (name "MPN") "AD8031BNZ"))
      (libsource (lib "eagle-import") (part "AD8031N"))
    )
    (comp (ref "IC22")
      (value "4066D")
      (footprint "eagle-import:SO14")
      (libsource (lib "eagle-import") (part "4066D"))
    )
    (comp (ref "IC23")
      (value "AD8031N")
      (footprint "eagle-import:DIL08")
      (fields (field (name "MPN") "AD8031BNZ"))
      (libsource (lib "eagle-import") (part "AD8031N"))
    )
    (comp (ref "IC24")
      (value "AD8031N")
      (footprint "eagle-import:DIL08")
      (fields (field (name "MPN") "AD8031BNZ"))
      (libsource (lib "eagle-import") (part "AD8031N"))
    )
    (comp (ref "IC25")
      (value "AD8031N")
      (footprint "eagle-import:DIL08")
      (fields (field (name "MPN") "AD8031BNZ"))
      (libsource (lib "eagle-import") (part "AD8031N"))
    )
    (comp (ref "IC26")
      (value "AD8031N")
      (footprint "eagle-import:DIL08")
      (fields (field (name "MPN") "AD8031BNZ"))
      (libsource (lib "eagle-import") (part "AD8031N"))
    )
    (comp (ref "IC28")
      (value "TLV1117")
      (footprint "eagle-import:SOT223-4")
      (libsource (lib "eagle-import") (part "texas2_TLV1117"))
    )
    (comp (ref "IC29")
      (value "TLV1117")
      (footprint "eagle-import:SOT223-4")
      (libsource (lib "eagle-import") (part "TLV1117"))
    )
    (comp (ref "IC30")
      (value "TLV1117")
      (footprint "eagle-import:SOT223-4")
      (libsource (lib "eagle-import") (part "TLV1117"))
    )
    (comp (ref "IC32")
      (value "TLV1117")
      (footprint "eagle-import:SOT223-4")
      (libsource (lib "eagle-import") (part "TLV1117"))
    )
    (comp (ref "IC33")
      (value "AD8031N")
      (footprint "eagle-import:DIL08")
      (fields (field (name "MPN") "AD8031BNZ"))
      (libsource (lib "eagle-import") (part "AD8031N"))
    )
    (comp (ref "IC41")
      (value "XCFXXS")
      (footprint "eagle-import:TSSOP20")
      (libsource (lib "eagle-import") (part "XCFXXS"))
    )
    (comp (ref "JP1")
      (value "ARDUINO_CONN-ANALOGSIP")
      (footprint "eagle-import:CONN-1X06")
      (libsource (lib "eagle-import") (part "ARDUINO_CONN-ANALOGSIP"))
    )
    (comp (ref "JP2")
      (value "JP2E")
      (footprint "eagle-import:JP2")
      (libsource (lib "eagle-import") (part "JP2E"))
    )
    (comp (ref "JP3")
      (value "ARDUINO_CONN-IO_LSIP")
      (footprint "eagle-import:CONN-1X08")
      (libsource (lib "eagle-import") (part "ARDUINO_CONN-IO_LSIP"))
    )
    (comp (ref "JP4")
      (value "ARDUINO_CONN-IO_HSIP")
      (footprint "eagle-import:CONN-1X10")
      (libsource (lib "eagle-import") (part "ARDUINO_CONN-IO_HSIP"))
    )
    (comp (ref "JP5")
      (value "JP2E")
      (footprint "eagle-import:JP2")
      (libsource (lib "eagle-import") (part "JP2E"))
    )
    (comp (ref "JP6")
      (value "JP2E")
      (footprint "eagle-import:JP2")
      (libsource (lib "eagle-import") (part "JP2E"))
    )
    (comp (ref "JP7")
      (value "ARDUINO_CONN-POWERSIP")
      (footprint "eagle-import:CONN-1X08")
      (libsource (lib "eagle-import") (part "ARDUINO_CONN-POWERSIP"))
    )
    (comp (ref "L1")
      (value "100u")
      (footprint "eagle-import:L5650M")
      (libsource (lib "eagle-import") (part "L-USL5650M"))
    )
    (comp (ref "L2")
      (value "100u")
      (footprint "eagle-import:L5650M")
      (libsource (lib "eagle-import") (part "L-USL5650M"))
    )
    (comp (ref "L3")
      (value "100u")
      (footprint "eagle-import:L5650M")
      (libsource (lib "eagle-import") (part "L-USL5650M"))
    )
    (comp (ref "L4")
      (value "100u")
      (footprint "eagle-import:L5650M")
      (libsource (lib "eagle-import") (part "L-USL5650M"))
    )
    (comp (ref "L5")
      (value "10u")
      (footprint "eagle-import:L0805")
      (libsource (lib "eagle-import") (part "L-USL0805"))
    )
    (comp (ref "L6")
      (value "10u")
      (footprint "eagle-import:L0805")
      (libsource (lib "eagle-import") (part "L-USL0805"))
    )
    (comp (ref "L7")
      (value "10u")
      (footprint "eagle-import:L0805")
      (libsource (lib "eagle-import") (part "L-USL0805"))
    )
    (comp (ref "L8")
      (value "10u")
      (footprint "eagle-import:L0805")
      (libsource (lib "eagle-import") (part "L-USL0805"))
    )
    (comp (ref "L9")
      (value "10u")
      (footprint "eagle-import:L0805")
      (libsource (lib "eagle-import") (part "L-USL0805"))
    )
    (comp (ref "L10")
      (value "10u")
      (footprint "eagle-import:L0805")
      (libsource (lib "eagle-import") (part "L-USL0805"))
    )
    (comp (ref "L11")
      (value "10u")
      (footprint "eagle-import:L0805")
      (libsource (lib "eagle-import") (part "L-USL0805"))
    )
    (comp (ref "L12")
      (value "10u")
      (footprint "eagle-import:L0805")
      (libsource (lib "eagle-import") (part "L-USL0805"))
    )
    (comp (ref "L13")
      (value "10u")
      (footprint "eagle-import:L0805")
      (libsource (lib "eagle-import") (part "L-USL0805"))
    )
    (comp (ref "L14")
      (value "10u")
      (footprint "eagle-import:L0805")
      (libsource (lib "eagle-import") (part "L-USL0805"))
    )
    (comp (ref "L15")
      (value "600 ohms @ 100 MHz")
      (footprint "eagle-import:L0805")
      (libsource (lib "eagle-import") (part "L-USL0805"))
    )
    (comp (ref "L16")
      (value "10u")
      (footprint "eagle-import:L0805")
      (libsource (lib "eagle-import") (part "L-USL0805"))
    )
    (comp (ref "L17")
      (value "600 ohms @ 100 MHz")
      (footprint "eagle-import:L0805")
      (libsource (lib "eagle-import") (part "L-USL0805"))
    )
    (comp (ref "L18")
      (value "10u")
      (footprint "eagle-import:L0805")
      (libsource (lib "eagle-import") (part "L-USL0805"))
    )
    (comp (ref "L19")
      (value "600 ohms @ 100 MHz")
      (footprint "eagle-import:L0805")
      (libsource (lib "eagle-import") (part "L-USL0805"))
    )
    (comp (ref "L20")
      (value "600 ohms @ 100 MHz")
      (footprint "eagle-import:L0805")
      (libsource (lib "eagle-import") (part "L-USL0805"))
    )
    (comp (ref "L21")
      (value "600 ohms @ 100 MHz")
      (footprint "eagle-import:L0805")
      (libsource (lib "eagle-import") (part "L-USL0805"))
    )
    (comp (ref "L22")
      (value "600 ohms @ 100 MHz")
      (footprint "eagle-import:L0805")
      (libsource (lib "eagle-import") (part "L-USL0805"))
    )
    (comp (ref "L23")
      (value "100u")
      (footprint "eagle-import:L5650M")
      (libsource (lib "eagle-import") (part "L-USL5650M"))
    )
    (comp (ref "L24")
      (value "100u")
      (footprint "eagle-import:L5650M")
      (libsource (lib "eagle-import") (part "L-USL5650M"))
    )
    (comp (ref "L25")
      (value "10u")
      (footprint "eagle-import:L0805")
      (libsource (lib "eagle-import") (part "L-USL0805"))
    )
    (comp (ref "L26")
      (value "600 ohms @ 100 MHz")
      (footprint "eagle-import:L0805")
      (libsource (lib "eagle-import") (part "L-USL0805"))
    )
    (comp (ref "L27")
      (value "600 ohms @ 100 MHz")
      (footprint "eagle-import:L0805")
      (libsource (lib "eagle-import") (part "L-USL0805"))
    )
    (comp (ref "L28")
      (value "600 ohms @ 100 MHz")
      (footprint "eagle-import:L0805")
      (libsource (lib "eagle-import") (part "L-USL0805"))
    )
    (comp (ref "L29")
      (value "600 ohms @ 100 MHz")
      (footprint "eagle-import:L0805")
      (libsource (lib "eagle-import") (part "L-USL0805"))
    )
    (comp (ref "L30")
      (value "600 ohms @ 100 MHz")
      (footprint "eagle-import:L0805")
      (libsource (lib "eagle-import") (part "L-USL0805"))
    )
    (comp (ref "L31")
      (value "600 ohms @ 100 MHz")
      (footprint "eagle-import:L0805")
      (libsource (lib "eagle-import") (part "L-USL0805"))
    )
    (comp (ref "PAD1")
      (value "2,54/1,1")
      (footprint "eagle-import:2,54_1,1")
      (libsource (lib "eagle-import") (part "2,54/1,1"))
    )
    (comp (ref "PAD2")
      (value "2,54/1,1")
      (footprint "eagle-import:2,54_1,1")
      (libsource (lib "eagle-import") (part "2,54/1,1"))
    )
    (comp (ref "PAD3")
      (value "2,54/1,1")
      (footprint "eagle-import:2,54_1,1")
      (libsource (lib "eagle-import") (part "2,54/1,1"))
    )
    (comp (ref "PAD4")
      (value "2,54/1,1")
      (footprint "eagle-import:2,54_1,1")
      (libsource (lib "eagle-import") (part "2,54/1,1"))
    )
    (comp (ref "PWR")
      (value "2,54/1,1")
      (footprint "eagle-import:2,54_1,1")
      (libsource (lib "eagle-import") (part "2,54/1,1"))
    )
    (comp (ref "Q1")
      (value "MMPQ2222A")
      (footprint "eagle-import:SO16")
      (libsource (lib "eagle-import") (part "MMPQ2222A"))
    )
    (comp (ref "Q2")
      (value "MMPQ2907A")
      (footprint "eagle-import:SO16")
      (libsource (lib "eagle-import") (part "MMPQ2907A"))
    )
    (comp (ref "Q3")
      (value "MMPQ6502")
      (footprint "eagle-import:SO16")
      (libsource (lib "eagle-import") (part "MMPQ6502"))
    )
    (comp (ref "QG1")
      (value "SG-615PCG")
      (footprint "eagle-import:SG-615")
      (fields (field (name "MPN") "SG615P-50MHZ 50PPM"))
      (libsource (lib "eagle-import") (part "SG-615PCG"))
    )
    (comp (ref "R1")
      (value "u")
      (footprint "eagle-import:0207_10")
      (libsource (lib "eagle-import") (part "R-US_0207/10"))
    )
    (comp (ref "R2")
      (value "u")
      (footprint "eagle-import:0207_10")
      (libsource (lib "eagle-import") (part "R-US_0207/10"))
    )
    (comp (ref "R3")
      (value "u")
      (footprint "eagle-import:0207_10")
      (libsource (lib "eagle-import") (part "R-US_0207/10"))
    )
    (comp (ref "R4")
      (value "u")
      (footprint "eagle-import:0207_10")
      (libsource (lib "eagle-import") (part "R-US_0207/10"))
    )
    (comp (ref "R5")
      (value "u")
      (footprint "eagle-import:0207_10")
      (libsource (lib "eagle-import") (part "R-US_0207/10"))
    )
    (comp (ref "R6")
      (value "u")
      (footprint "eagle-import:0207_10")
      (libsource (lib "eagle-import") (part "R-US_0207/10"))
    )
    (comp (ref "R7")
      (value "u")
      (footprint "eagle-import:0207_10")
      (libsource (lib "eagle-import") (part "R-US_0207/10"))
    )
    (comp (ref "R8")
      (value "100")
      (footprint "eagle-import:0207_10")
      (libsource (lib "eagle-import") (part "R-US_0207/10"))
    )
    (comp (ref "R9")
      (value "70")
      (footprint "eagle-import:R0805")
      (libsource (lib "eagle-import") (part "R-US_R0805"))
    )
    (comp (ref "R10")
      (value "70")
      (footprint "eagle-import:R0805")
      (libsource (lib "eagle-import") (part "R-US_R0805"))
    )
    (comp (ref "R11")
      (value "70")
      (footprint "eagle-import:R0805")
      (libsource (lib "eagle-import") (part "R-US_R0805"))
    )
    (comp (ref "R12")
      (value "70")
      (footprint "eagle-import:R0805")
      (libsource (lib "eagle-import") (part "R-US_R0805"))
    )
    (comp (ref "R13")
      (value "70")
      (footprint "eagle-import:R0805")
      (libsource (lib "eagle-import") (part "R-US_R0805"))
    )
    (comp (ref "R14")
      (value "1k")
      (footprint "eagle-import:0207_10")
      (libsource (lib "eagle-import") (part "R-US_0207/10"))
    )
    (comp (ref "R15")
      (value "2k")
      (footprint "eagle-import:0207_10")
      (libsource (lib "eagle-import") (part "R-US_0207/10"))
    )
    (comp (ref "R16")
      (value "10k")
      (footprint "eagle-import:0207_10")
      (libsource (lib "eagle-import") (part "R-US_0207/10"))
    )
    (comp (ref "R17")
      (value "10k")
      (footprint "eagle-import:0207_10")
      (libsource (lib "eagle-import") (part "R-US_0207/10"))
    )
    (comp (ref "R18")
      (value "TRIM_US-CT6")
      (footprint "eagle-import:CT6")
      (libsource (lib "eagle-import") (part "TRIM_US-CT6"))
    )
    (comp (ref "R19")
      (value "0")
      (footprint "eagle-import:R0805")
      (libsource (lib "eagle-import") (part "R-US_R0805"))
    )
    (comp (ref "R20")
      (value "u")
      (footprint "eagle-import:0207_10")
      (libsource (lib "eagle-import") (part "R-US_0207/10"))
    )
    (comp (ref "R21")
      (value "u")
      (footprint "eagle-import:0207_10")
      (libsource (lib "eagle-import") (part "R-US_0207/10"))
    )
    (comp (ref "R22")
      (value "u")
      (footprint "eagle-import:0207_10")
      (libsource (lib "eagle-import") (part "R-US_0207/10"))
    )
    (comp (ref "R23")
      (value "u")
      (footprint "eagle-import:0207_10")
      (libsource (lib "eagle-import") (part "R-US_0207/10"))
    )
    (comp (ref "R24")
      (value "u")
      (footprint "eagle-import:0207_10")
      (libsource (lib "eagle-import") (part "R-US_0207/10"))
    )
    (comp (ref "R25")
      (value "u")
      (footprint "eagle-import:0207_10")
      (libsource (lib "eagle-import") (part "R-US_0207/10"))
    )
    (comp (ref "R26")
      (value "u")
      (footprint "eagle-import:0207_10")
      (libsource (lib "eagle-import") (part "R-US_0207/10"))
    )
    (comp (ref "R27")
      (value "u")
      (footprint "eagle-import:0207_10")
      (libsource (lib "eagle-import") (part "R-US_0207/10"))
    )
    (comp (ref "R28")
      (value "100")
      (footprint "eagle-import:0207_10")
      (libsource (lib "eagle-import") (part "R-US_0207/10"))
    )
    (comp (ref "R29")
      (value "u")
      (footprint "eagle-import:0207_10")
      (libsource (lib "eagle-import") (part "R-US_0207/10"))
    )
    (comp (ref "R30")
      (value "u")
      (footprint "eagle-import:0207_10")
      (libsource (lib "eagle-import") (part "R-US_0207/10"))
    )
    (comp (ref "R31")
      (value "100")
      (footprint "eagle-import:0207_10")
      (libsource (lib "eagle-import") (part "R-US_0207/10"))
    )
    (comp (ref "R32")
      (value "u")
      (footprint "eagle-import:0204_7")
      (libsource (lib "eagle-import") (part "R-US_0204/7"))
    )
    (comp (ref "R33")
      (value "u")
      (footprint "eagle-import:0204_7")
      (libsource (lib "eagle-import") (part "R-US_0204/7"))
    )
    (comp (ref "R34")
      (value "100")
      (footprint "eagle-import:0207_10")
      (libsource (lib "eagle-import") (part "R-US_0207/10"))
    )
    (comp (ref "R35")
      (value "u")
      (footprint "eagle-import:0207_10")
      (libsource (lib "eagle-import") (part "R-US_0207/10"))
    )
    (comp (ref "R36")
      (value "u")
      (footprint "eagle-import:0207_10")
      (libsource (lib "eagle-import") (part "R-US_0207/10"))
    )
    (comp (ref "R37")
      (value "100")
      (footprint "eagle-import:0207_10")
      (libsource (lib "eagle-import") (part "R-US_0207/10"))
    )
    (comp (ref "R38")
      (value "u")
      (footprint "eagle-import:0207_10")
      (libsource (lib "eagle-import") (part "R-US_0207/10"))
    )
    (comp (ref "R39")
      (value "u")
      (footprint "eagle-import:0204_7")
      (libsource (lib "eagle-import") (part "R-US_0204/7"))
    )
    (comp (ref "R40")
      (value "100")
      (footprint "eagle-import:0207_10")
      (libsource (lib "eagle-import") (part "R-US_0207/10"))
    )
    (comp (ref "R41")
      (value "u")
      (footprint "eagle-import:0207_10")
      (libsource (lib "eagle-import") (part "R-US_0207/10"))
    )
    (comp (ref "R42")
      (value "u")
      (footprint "eagle-import:0207_10")
      (libsource (lib "eagle-import") (part "R-US_0207/10"))
    )
    (comp (ref "R43")
      (value "u")
      (footprint "eagle-import:0207_10")
      (libsource (lib "eagle-import") (part "R-US_0207/10"))
    )
    (comp (ref "R44")
      (value "u")
      (footprint "eagle-import:0207_10")
      (libsource (lib "eagle-import") (part "R-US_0207/10"))
    )
    (comp (ref "R45")
      (value "1k")
      (footprint "eagle-import:R0805")
      (libsource (lib "eagle-import") (part "R-US_R0805"))
    )
    (comp (ref "R46")
      (value "u")
      (footprint "eagle-import:0207_10")
      (libsource (lib "eagle-import") (part "R-US_0207/10"))
    )
    (comp (ref "R47")
      (value "u")
      (footprint "eagle-import:0207_10")
      (libsource (lib "eagle-import") (part "R-US_0207/10"))
    )
    (comp (ref "R48")
      (value "u")
      (footprint "eagle-import:0207_10")
      (libsource (lib "eagle-import") (part "R-US_0207/10"))
    )
    (comp (ref "R49")
      (value "u")
      (footprint "eagle-import:0207_10")
      (libsource (lib "eagle-import") (part "R-US_0207/10"))
    )
    (comp (ref "R50")
      (value "500")
      (footprint "eagle-import:0207_10")
      (libsource (lib "eagle-import") (part "R-US_0207/10"))
    )
    (comp (ref "R51")
      (value "500")
      (footprint "eagle-import:0207_10")
      (libsource (lib "eagle-import") (part "R-US_0207/10"))
    )
    (comp (ref "R52")
      (value "500")
      (footprint "eagle-import:0207_10")
      (libsource (lib "eagle-import") (part "R-US_0207/10"))
    )
    (comp (ref "R53")
      (value "500")
      (footprint "eagle-import:0207_10")
      (libsource (lib "eagle-import") (part "R-US_0207/10"))
    )
    (comp (ref "R54")
      (value "500")
      (footprint "eagle-import:0207_10")
      (libsource (lib "eagle-import") (part "R-US_0207/10"))
    )
    (comp (ref "R55")
      (value "500")
      (footprint "eagle-import:0207_10")
      (libsource (lib "eagle-import") (part "R-US_0207/10"))
    )
    (comp (ref "R56")
      (value "500")
      (footprint "eagle-import:0207_10")
      (libsource (lib "eagle-import") (part "R-US_0207/10"))
    )
    (comp (ref "R57")
      (value "500")
      (footprint "eagle-import:0207_10")
      (libsource (lib "eagle-import") (part "R-US_0207/10"))
    )
    (comp (ref "R58")
      (value "100")
      (footprint "eagle-import:M0805")
      (libsource (lib "eagle-import") (part "R-US_M0805"))
    )
    (comp (ref "R59")
      (value "100")
      (footprint "eagle-import:M0805")
      (libsource (lib "eagle-import") (part "R-US_M0805"))
    )
    (comp (ref "R60")
      (value "4.7k")
      (footprint "eagle-import:M0805")
      (libsource (lib "eagle-import") (part "R-US_M0805"))
    )
    (comp (ref "R61")
      (value "330")
      (footprint "eagle-import:M0805")
      (libsource (lib "eagle-import") (part "R-US_M0805"))
    )
    (comp (ref "R62")
      (value "4.7k")
      (footprint "eagle-import:M0805")
      (libsource (lib "eagle-import") (part "R-US_M0805"))
    )
    (comp (ref "R63")
      (value "u")
      (footprint "eagle-import:0207_10")
      (libsource (lib "eagle-import") (part "R-US_0207/10"))
    )
    (comp (ref "R64")
      (value "u")
      (footprint "eagle-import:0207_10")
      (libsource (lib "eagle-import") (part "R-US_0207/10"))
    )
    (comp (ref "R65")
      (value "np")
      (footprint "eagle-import:R0805")
      (libsource (lib "eagle-import") (part "R-US_R0805"))
    )
    (comp (ref "R66")
      (value "u")
      (footprint "eagle-import:0207_10")
      (libsource (lib "eagle-import") (part "R-US_0207/10"))
    )
    (comp (ref "R67")
      (value "0")
      (footprint "eagle-import:R0805")
      (libsource (lib "eagle-import") (part "R-US_R0805"))
    )
    (comp (ref "R68")
      (value "np")
      (footprint "eagle-import:R0805")
      (libsource (lib "eagle-import") (part "R-US_R0805"))
    )
    (comp (ref "R69")
      (value "100")
      (footprint "eagle-import:0207_10")
      (libsource (lib "eagle-import") (part "R-US_0207/10"))
    )
    (comp (ref "R70")
      (value "TRIM_US-CT6")
      (footprint "eagle-import:CT6")
      (libsource (lib "eagle-import") (part "TRIM_US-CT6"))
    )
    (comp (ref "R71")
      (value "u")
      (footprint "eagle-import:0207_10")
      (libsource (lib "eagle-import") (part "R-US_0207/10"))
    )
    (comp (ref "R72")
      (value "u")
      (footprint "eagle-import:0207_10")
      (libsource (lib "eagle-import") (part "R-US_0207/10"))
    )
    (comp (ref "R73")
      (value "1k")
      (footprint "eagle-import:R0805")
      (libsource (lib "eagle-import") (part "R-US_R0805"))
    )
    (comp (ref "R74")
      (value "70")
      (footprint "eagle-import:R0805")
      (libsource (lib "eagle-import") (part "R-US_R0805"))
    )
    (comp (ref "R75")
      (value "70")
      (footprint "eagle-import:R0805")
      (libsource (lib "eagle-import") (part "R-US_R0805"))
    )
    (comp (ref "R76")
      (value "70")
      (footprint "eagle-import:R0805")
      (libsource (lib "eagle-import") (part "R-US_R0805"))
    )
    (comp (ref "R77")
      (value "70")
      (footprint "eagle-import:R0805")
      (libsource (lib "eagle-import") (part "R-US_R0805"))
    )
    (comp (ref "R78")
      (value "70")
      (footprint "eagle-import:R0805")
      (libsource (lib "eagle-import") (part "R-US_R0805"))
    )
    (comp (ref "R79")
      (value "70")
      (footprint "eagle-import:R0805")
      (libsource (lib "eagle-import") (part "R-US_R0805"))
    )
    (comp (ref "R80")
      (value "70")
      (footprint "eagle-import:R0805")
      (libsource (lib "eagle-import") (part "R-US_R0805"))
    )
    (comp (ref "R81")
      (value "70")
      (footprint "eagle-import:R0805")
      (libsource (lib "eagle-import") (part "R-US_R0805"))
    )
    (comp (ref "R82")
      (value "70")
      (footprint "eagle-import:R0805")
      (libsource (lib "eagle-import") (part "R-US_R0805"))
    )
    (comp (ref "R83")
      (value "1k")
      (footprint "eagle-import:R0805")
      (libsource (lib "eagle-import") (part "R-US_R0805"))
    )
    (comp (ref "R84")
      (value "6k")
      (footprint "eagle-import:R0805")
      (libsource (lib "eagle-import") (part "R-US_R0805"))
    )
    (comp (ref "R85")
      (value "6k")
      (footprint "eagle-import:R0805")
      (libsource (lib "eagle-import") (part "R-US_R0805"))
    )
    (comp (ref "R86")
      (value "6k")
      (footprint "eagle-import:R0805")
      (libsource (lib "eagle-import") (part "R-US_R0805"))
    )
    (comp (ref "R87")
      (value "6k")
      (footprint "eagle-import:R0805")
      (libsource (lib "eagle-import") (part "R-US_R0805"))
    )
    (comp (ref "R88")
      (value "6k")
      (footprint "eagle-import:R0805")
      (libsource (lib "eagle-import") (part "R-US_R0805"))
    )
    (comp (ref "R89")
      (value "6k")
      (footprint "eagle-import:R0805")
      (libsource (lib "eagle-import") (part "R-US_R0805"))
    )
    (comp (ref "R90")
      (value "10k")
      (footprint "eagle-import:R0805")
      (libsource (lib "eagle-import") (part "R-US_R0805"))
    )
    (comp (ref "R91")
      (value "10k")
      (footprint "eagle-import:R0805")
      (libsource (lib "eagle-import") (part "R-US_R0805"))
    )
    (comp (ref "R92")
      (value "10k")
      (footprint "eagle-import:R0805")
      (libsource (lib "eagle-import") (part "R-US_R0805"))
    )
    (comp (ref "R93")
      (value "10k")
      (footprint "eagle-import:R0805")
      (libsource (lib "eagle-import") (part "R-US_R0805"))
    )
    (comp (ref "R94")
      (value "10k")
      (footprint "eagle-import:R0805")
      (libsource (lib "eagle-import") (part "R-US_R0805"))
    )
    (comp (ref "R95")
      (value "10k")
      (footprint "eagle-import:R0805")
      (libsource (lib "eagle-import") (part "R-US_R0805"))
    )
    (comp (ref "R96")
      (value "6k")
      (footprint "eagle-import:R0805")
      (libsource (lib "eagle-import") (part "R-US_R0805"))
    )
    (comp (ref "R97")
      (value "10k")
      (footprint "eagle-import:R0805")
      (libsource (lib "eagle-import") (part "R-US_R0805"))
    )
    (comp (ref "S1")
      (value "10-XX")
      (footprint "eagle-import:B3F-10XX")
      (fields (field (name "MPN") "B3F-1000"))
      (libsource (lib "eagle-import") (part "10-XX"))
    )
    (comp (ref "SL1")
      (value "M06")
      (footprint "eagle-import:06P")
      (libsource (lib "eagle-import") (part "M06"))
    )
    (comp (ref "STR_GND")
      (value "2,54/1,1")
      (footprint "eagle-import:2,54_1,1")
      (libsource (lib "eagle-import") (part "2,54/1,1"))
    )
    (comp (ref "U1")
      (value "6SLX9TQG144")
      (footprint "eagle-import:TQ144")
      (libsource (lib "eagle-import") (part "6SLX9TQG144"))
    )
  )
  (nets
    (net (code "1") (name "+1V2") (class "Default")
      (node (ref "C92") (pin "1") (pinfunction "1_1") (pintype "passive"))
      (node (ref "C93") (pin "1") (pinfunction "1_1") (pintype "passive"))
      (node (ref "C94") (pin "1") (pinfunction "1_1") (pintype "passive"))
      (node (ref "IC29") (pin "2") (pinfunction "VOUT1_2") (pintype "power_in"))
      (node (ref "IC29") (pin "4") (pinfunction "VOUT2_4") (pintype "power_in"))
      (node (ref "U1") (pin "P128") (pinfunction "VCCINT_P128") (pintype "input"))
      (node (ref "U1") (pin "P19") (pinfunction "VCCINT_P19") (pintype "input"))
      (node (ref "U1") (pin "P28") (pinfunction "VCCINT_P28") (pintype "input"))
      (node (ref "U1") (pin "P52") (pinfunction "VCCINT_P52") (pintype "input"))
      (node (ref "U1") (pin "P89") (pinfunction "VCCINT_P89") (pintype "input"))
    )
    (net (code "2") (name "+2V5") (class "Default")
      (node (ref "C89") (pin "1") (pinfunction "1_1") (pintype "passive"))
      (node (ref "C90") (pin "1") (pinfunction "1_1") (pintype "passive"))
      (node (ref "C91") (pin "1") (pinfunction "1_1") (pintype "passive"))
      (node (ref "IC30") (pin "2") (pinfunction "VOUT1_2") (pintype "power_in"))
      (node (ref "IC30") (pin "4") (pinfunction "VOUT2_4") (pintype "power_in"))
      (node (ref "U1") (pin "P129") (pinfunction "VCCAUX_P129") (pintype "input"))
      (node (ref "U1") (pin "P20") (pinfunction "VCCAUX_P20") (pintype "input"))
      (node (ref "U1") (pin "P36") (pinfunction "VCCAUX_P36") (pintype "input"))
      (node (ref "U1") (pin "P53") (pinfunction "VCCAUX_P53") (pintype "input"))
      (node (ref "U1") (pin "P90") (pinfunction "VCCAUX_P90") (pintype "input"))
    )
    (net (code "3") (name "+3V3A") (class "Default")
      (node (ref "C125") (pin "1") (pinfunction "1_1") (pintype "passive"))
      (node (ref "C132") (pin "1") (pinfunction "1_1") (pintype "passive"))
      (node (ref "C14") (pin "1") (pinfunction "1_1") (pintype "passive"))
      (node (ref "C145") (pin "1") (pinfunction "1_1") (pintype "passive"))
      (node (ref "C146") (pin "+") (pinfunction "+_+") (pintype "passive"))
      (node (ref "IC14") (pin "16") (pinfunction "VCC_16") (pintype "power_in"))
      (node (ref "IC32") (pin "3") (pinfunction "VIN_3") (pintype "power_in"))
      (node (ref "IC5") (pin "14") (pinfunction "VDD_14") (pintype "power_in"))
      (node (ref "IC9") (pin "8") (pinfunction "VCC_8") (pintype "power_in"))
      (node (ref "L10") (pin "1") (pinfunction "1_1") (pintype "passive"))
      (node (ref "L11") (pin "1") (pinfunction "1_1") (pintype "passive"))
      (node (ref "L12") (pin "1") (pinfunction "1_1") (pintype "passive"))
      (node (ref "L13") (pin "1") (pinfunction "1_1") (pintype "passive"))
      (node (ref "L14") (pin "1") (pinfunction "1_1") (pintype "passive"))
      (node (ref "L16") (pin "1") (pinfunction "1_1") (pintype "passive"))
      (node (ref "L18") (pin "1") (pinfunction "1_1") (pintype "passive"))
      (node (ref "L23") (pin "2") (pinfunction "2_2") (pintype "passive"))
      (node (ref "L25") (pin "1") (pinfunction "1_1") (pintype "passive"))
      (node (ref "L5") (pin "1") (pinfunction "1_1") (pintype "passive"))
      (node (ref "L6") (pin "1") (pinfunction "1_1") (pintype "passive"))
      (node (ref "L7") (pin "1") (pinfunction "1_1") (pintype "passive"))
      (node (ref "L8") (pin "1") (pinfunction "1_1") (pintype "passive"))
      (node (ref "L9") (pin "1") (pinfunction "1_1") (pintype "passive"))
      (node (ref "Q3") (pin "1") (pinfunction "C1_1") (pintype "passive"))
      (node (ref "Q3") (pin "2") (pinfunction "C2_2") (pintype "passive"))
      (node (ref "Q3") (pin "3") (pinfunction "C1_3") (pintype "passive"))
      (node (ref "Q3") (pin "4") (pinfunction "C2_4") (pintype "passive"))
      (node (ref "R18") (pin "E") (pinfunction "E_E") (pintype "passive"))
    )
    (net (code "4") (name "+3V3D") (class "Default")
      (node (ref "C69") (pin "1") (pinfunction "1_1") (pintype "passive"))
      (node (ref "C80") (pin "1") (pinfunction "1_1") (pintype "passive"))
      (node (ref "C81") (pin "1") (pinfunction "1_1") (pintype "passive"))
      (node (ref "C82") (pin "1") (pinfunction "1_1") (pintype "passive"))
      (node (ref "C83") (pin "1") (pinfunction "1_1") (pintype "passive"))
      (node (ref "C84") (pin "1") (pinfunction "1_1") (pintype "passive"))
      (node (ref "C85") (pin "1") (pinfunction "1_1") (pintype "passive"))
      (node (ref "C86") (pin "1") (pinfunction "1_1") (pintype "passive"))
      (node (ref "C87") (pin "1") (pinfunction "1_1") (pintype "passive"))
      (node (ref "C88") (pin "1") (pinfunction "1_1") (pintype "passive"))
      (node (ref "IC41") (pin "18") (pinfunction "VCCINT_18") (pintype "power_in"))
      (node (ref "IC41") (pin "19") (pinfunction "VCCO_19") (pintype "power_in"))
      (node (ref "IC41") (pin "20") (pinfunction "VCCJ_20") (pintype "power_in"))
      (node (ref "IC8") (pin "2") (pinfunction "VOUT1_2") (pintype "power_in"))
      (node (ref "IC8") (pin "4") (pinfunction "VOUT2_4") (pintype "power_in"))
      (node (ref "L15") (pin "2") (pinfunction "2_2") (pintype "passive"))
      (node (ref "L17") (pin "2") (pinfunction "2_2") (pintype "passive"))
      (node (ref "L19") (pin "2") (pinfunction "2_2") (pintype "passive"))
      (node (ref "L20") (pin "2") (pinfunction "2_2") (pintype "passive"))
      (node (ref "L21") (pin "2") (pinfunction "2_2") (pintype "passive"))
      (node (ref "L22") (pin "2") (pinfunction "2_2") (pintype "passive"))
      (node (ref "QG1") (pin "1") (pinfunction "OE_1") (pintype "input"))
      (node (ref "QG1") (pin "4") (pinfunction "VCC_4") (pintype "power_in"))
      (node (ref "R58") (pin "2") (pinfunction "2_2") (pintype "passive"))
      (node (ref "R60") (pin "2") (pinfunction "2_2") (pintype "passive"))
      (node (ref "R61") (pin "2") (pinfunction "2_2") (pintype "passive"))
      (node (ref "R62") (pin "2") (pinfunction "2_2") (pintype "passive"))
      (node (ref "SL1") (pin "6") (pinfunction "6_6") (pintype "passive"))
      (node (ref "U1") (pin "P103") (pinfunction "VCCO_1_P103") (pintype "input"))
      (node (ref "U1") (pin "P122") (pinfunction "VCCO_0_P122") (pintype "input"))
      (node (ref "U1") (pin "P125") (pinfunction "VCCO_0_P125") (pintype "input"))
      (node (ref "U1") (pin "P135") (pinfunction "VCCO_0_P135") (pintype "input"))
      (node (ref "U1") (pin "P18") (pinfunction "VCCO_3_P18") (pintype "input"))
      (node (ref "U1") (pin "P31") (pinfunction "VCCO_3_P31") (pintype "input"))
      (node (ref "U1") (pin "P4") (pinfunction "VCCO_3_P4") (pintype "input"))
      (node (ref "U1") (pin "P42") (pinfunction "VCCO_2_P42") (pintype "input"))
      (node (ref "U1") (pin "P63") (pinfunction "VCCO_2_P63") (pintype "input"))
      (node (ref "U1") (pin "P69") (pinfunction "IO_L1N_M0_CMPMISO_2_P69") (pintype "bidirectional"))
      (node (ref "U1") (pin "P76") (pinfunction "VCCO_1_P76") (pintype "input"))
      (node (ref "U1") (pin "P86") (pinfunction "VCCO_1_P86") (pintype "input"))
    )
    (net (code "5") (name "+5V") (class "Default")
      (node (ref "C72") (pin "+") (pinfunction "+_+") (pintype "passive"))
      (node (ref "IC29") (pin "3") (pinfunction "VIN_3") (pintype "power_in"))
      (node (ref "IC30") (pin "3") (pinfunction "VIN_3") (pintype "power_in"))
      (node (ref "IC4") (pin "1") (pinfunction "DIR_1") (pintype "input"))
      (node (ref "IC4") (pin "20") (pinfunction "VCC_20") (pintype "power_in"))
      (node (ref "IC8") (pin "3") (pinfunction "VIN_3") (pintype "power_in"))
      (node (ref "L1") (pin "2") (pinfunction "2_2") (pintype "passive"))
      (node (ref "R83") (pin "1") (pinfunction "1_1") (pintype "passive"))
    )
    (net (code "6") (name "/BRKPT0") (class "Default")
      (node (ref "R50") (pin "1") (pinfunction "1_1") (pintype "passive"))
      (node (ref "U1") (pin "P67") (pinfunction "IO_L2P_CMPCLK_2_P67") (pintype "bidirectional"))
    )
    (net (code "7") (name "/BRKPT1") (class "Default")
      (node (ref "R51") (pin "1") (pinfunction "1_1") (pintype "passive"))
      (node (ref "U1") (pin "P66") (pinfunction "IO_L2N_CMPMOSI_2_P66") (pintype "bidirectional"))
    )
    (net (code "8") (name "/BRKPT2") (class "Default")
      (node (ref "R52") (pin "1") (pinfunction "1_1") (pintype "passive"))
      (node (ref "U1") (pin "P64") (pinfunction "IO_L3N_MOSI_CSI_B_MISO0_2_P64") (pintype "bidirectional"))
    )
    (net (code "9") (name "/BRKPT3") (class "Default")
      (node (ref "R53") (pin "1") (pinfunction "1_1") (pintype "passive"))
      (node (ref "U1") (pin "P62") (pinfunction "IO_L12P_D1_MISO2_2_P62") (pintype "bidirectional"))
    )
    (net (code "10") (name "/BRKPT4") (class "Default")
      (node (ref "R54") (pin "1") (pinfunction "1_1") (pintype "passive"))
      (node (ref "U1") (pin "P61") (pinfunction "IO_L12N_D2_MISO3_2_P61") (pintype "bidirectional"))
    )
    (net (code "11") (name "/BRKPT5") (class "Default")
      (node (ref "R55") (pin "1") (pinfunction "1_1") (pintype "passive"))
      (node (ref "U1") (pin "P59") (pinfunction "IO_L13N_D10_2_P59") (pintype "bidirectional"))
    )
    (net (code "12") (name "/BRKPT6") (class "Default")
      (node (ref "R56") (pin "1") (pinfunction "1_1") (pintype "passive"))
      (node (ref "U1") (pin "P58") (pinfunction "IO_L14P_D11_2_P58") (pintype "bidirectional"))
    )
    (net (code "13") (name "/BRKPT7") (class "Default")
      (node (ref "R57") (pin "1") (pinfunction "1_1") (pintype "passive"))
      (node (ref "U1") (pin "P57") (pinfunction "IO_L14N_D12_2_P57") (pintype "bidirectional"))
    )
    (net (code "14") (name "/CAP_SW1") (class "Default")
      (node (ref "IC5") (pin "13") (pinfunction "C_13") (pintype "input"))
      (node (ref "U1") (pin "P84") (pinfunction "IO_L43N_GCLK4_1_P84") (pintype "bidirectional"))
    )
    (net (code "15") (name "/CAP_SW2") (class "Default")
      (node (ref "IC5") (pin "6") (pinfunction "C_6") (pintype "input"))
      (node (ref "U1") (pin "P74") (pinfunction "IO_L74N_DOUT_BUSY_1_P74") (pintype "bidirectional"))
    )
    (net (code "16") (name "/FPGA_IN0") (class "Default")
      (node (ref "R86") (pin "2") (pinfunction "2_2") (pintype "passive"))
      (node (ref "R92") (pin "1") (pinfunction "1_1") (pintype "passive"))
      (node (ref "U1") (pin "P115") (pinfunction "IO_L65P_SCP3_0_P115") (pintype "bidirectional"))
    )
    (net (code "17") (name "/FPGA_IN1") (class "Default")
      (node (ref "R87") (pin "2") (pinfunction "2_2") (pintype "passive"))
      (node (ref "R93") (pin "1") (pinfunction "1_1") (pintype "passive"))
      (node (ref "U1") (pin "P114") (pinfunction "IO_L65N_SCP2_0_P114") (pintype "bidirectional"))
    )
    (net (code "18") (name "/FPGA_IN2") (class "Default")
      (node (ref "R88") (pin "2") (pinfunction "2_2") (pintype "passive"))
      (node (ref "R94") (pin "1") (pinfunction "1_1") (pintype "passive"))
      (node (ref "U1") (pin "P112") (pinfunction "IO_L66P_SCP1_0_P112") (pintype "bidirectional"))
    )
    (net (code "19") (name "/FPGA_IN3") (class "Default")
      (node (ref "R89") (pin "2") (pinfunction "2_2") (pintype "passive"))
      (node (ref "R95") (pin "1") (pinfunction "1_1") (pintype "passive"))
      (node (ref "U1") (pin "P111") (pinfunction "IO_L66N_SCP0_0_P111") (pintype "bidirectional"))
    )
    (net (code "20") (name "/FPGA_OUT0") (class "Default")
      (node (ref "IC4") (pin "2") (pinfunction "A1_2") (pintype "bidirectional"))
      (node (ref "U1") (pin "P133") (pinfunction "IO_L34N_GCLK18_0_P133") (pintype "bidirectional"))
    )
    (net (code "21") (name "/FPGA_OUT1") (class "Default")
      (node (ref "IC4") (pin "3") (pinfunction "A2_3") (pintype "bidirectional"))
      (node (ref "U1") (pin "P132") (pinfunction "IO_L35P_GCLK17_0_P132") (pintype "bidirectional"))
    )
    (net (code "22") (name "/FPGA_OUT2") (class "Default")
      (node (ref "IC4") (pin "4") (pinfunction "A3_4") (pintype "bidirectional"))
      (node (ref "U1") (pin "P131") (pinfunction "IO_L35N_GCLK16_0_P131") (pintype "bidirectional"))
    )
    (net (code "23") (name "/FPGA_OUT3") (class "Default")
      (node (ref "IC4") (pin "5") (pinfunction "A4_5") (pintype "bidirectional"))
      (node (ref "U1") (pin "P127") (pinfunction "IO_L36P_GCLK15_0_P127") (pintype "bidirectional"))
    )
    (net (code "24") (name "/FPGA_OUT4") (class "Default")
      (node (ref "IC4") (pin "6") (pinfunction "A5_6") (pintype "bidirectional"))
      (node (ref "U1") (pin "P126") (pinfunction "IO_L36N_GCLK14_0_P126") (pintype "bidirectional"))
    )
    (net (code "25") (name "/GAIN") (class "Default")
      (node (ref "IC22") (pin "12") (pinfunction "C_12") (pintype "input"))
      (node (ref "U1") (pin "P40") (pinfunction "IO_L64N_D9_2_P40") (pintype "bidirectional"))
    )
    (net (code "26") (name "/HIGH_FREQ_LPF") (class "Default")
      (node (ref "IC18") (pin "12") (pinfunction "C_12") (pintype "input"))
      (node (ref "IC18") (pin "6") (pinfunction "C_6") (pintype "input"))
      (node (ref "R79") (pin "2") (pinfunction "2_2") (pintype "passive"))
    )
    (net (code "27") (name "/HIGH_LEVEL") (class "Default")
      (node (ref "IC22") (pin "6") (pinfunction "C_6") (pintype "input"))
      (node (ref "R80") (pin "2") (pinfunction "2_2") (pintype "passive"))
    )
    (net (code "28") (name "/HI_RES_PWM1") (class "Default")
      (node (ref "IC2") (pin "12") (pinfunction "C_12") (pintype "input"))
      (node (ref "IC2") (pin "13") (pinfunction "C_13") (pintype "input"))
      (node (ref "R11") (pin "2") (pinfunction "2_2") (pintype "passive"))
    )
    (net (code "29") (name "/HI_RES_PWM2") (class "Default")
      (node (ref "IC3") (pin "13") (pinfunction "C_13") (pintype "input"))
      (node (ref "R10") (pin "2") (pinfunction "2_2") (pintype "passive"))
    )
    (net (code "30") (name "/IN_GAIN") (class "Default")
      (node (ref "IC3") (pin "12") (pinfunction "C_12") (pintype "input"))
      (node (ref "R9") (pin "2") (pinfunction "2_2") (pintype "passive"))
    )
    (net (code "31") (name "/LOW2MID_HPF") (class "Default")
      (node (ref "IC16") (pin "13") (pinfunction "C_13") (pintype "input"))
      (node (ref "IC16") (pin "5") (pinfunction "C_5") (pintype "input"))
      (node (ref "R76") (pin "2") (pinfunction "2_2") (pintype "passive"))
    )
    (net (code "32") (name "/LOW2MID_LPF") (class "Default")
      (node (ref "IC7") (pin "13") (pinfunction "C_13") (pintype "input"))
      (node (ref "IC7") (pin "5") (pinfunction "C_5") (pintype "input"))
      (node (ref "R75") (pin "2") (pinfunction "2_2") (pintype "passive"))
    )
    (net (code "33") (name "/LOW_LEVEL") (class "Default")
      (node (ref "IC22") (pin "13") (pinfunction "C_13") (pintype "input"))
      (node (ref "R82") (pin "2") (pinfunction "2_2") (pintype "passive"))
    )
    (net (code "34") (name "/LO_RES_PWM") (class "Default")
      (node (ref "IC2") (pin "5") (pinfunction "C_5") (pintype "input"))
      (node (ref "IC2") (pin "6") (pinfunction "C_6") (pintype "input"))
      (node (ref "R12") (pin "2") (pinfunction "2_2") (pintype "passive"))
      (node (ref "R72") (pin "2") (pinfunction "2_2") (pintype "passive"))
    )
    (net (code "35") (name "/MID2HIGH_HPF") (class "Default")
      (node (ref "IC18") (pin "13") (pinfunction "C_13") (pintype "input"))
      (node (ref "IC18") (pin "5") (pinfunction "C_5") (pintype "input"))
      (node (ref "R78") (pin "2") (pinfunction "2_2") (pintype "passive"))
    )
    (net (code "36") (name "/MID2HIGH_LPF") (class "Default")
      (node (ref "IC16") (pin "12") (pinfunction "C_12") (pintype "input"))
      (node (ref "IC16") (pin "6") (pinfunction "C_6") (pintype "input"))
      (node (ref "R77") (pin "2") (pinfunction "2_2") (pintype "passive"))
    )
    (net (code "37") (name "/MID_LEVEL") (class "Default")
      (node (ref "IC22") (pin "5") (pinfunction "C_5") (pintype "input"))
      (node (ref "R81") (pin "2") (pinfunction "2_2") (pintype "passive"))
    )
    (net (code "38") (name "/NEW_DATA") (class "Default")
      (node (ref "R85") (pin "2") (pinfunction "2_2") (pintype "passive"))
      (node (ref "R91") (pin "1") (pinfunction "1_1") (pintype "passive"))
      (node (ref "U1") (pin "P116") (pinfunction "IO_L64N_SCP4_0_P116") (pintype "bidirectional"))
    )
    (net (code "39") (name "/NFILTER_OSC_SEL") (class "Default")
      (node (ref "IC14") (pin "1") (pinfunction "IN_1") (pintype "bidirectional"))
      (node (ref "IC3") (pin "6") (pinfunction "C_6") (pintype "input"))
      (node (ref "IC5") (pin "5") (pinfunction "C_5") (pintype "input"))
      (node (ref "U1") (pin "P94") (pinfunction "IO_L40N_GCLK10_1_P94") (pintype "bidirectional"))
    )
    (net (code "40") (name "/PULSE_HI_LIMIT") (class "Default")
      (node (ref "R73") (pin "1") (pinfunction "1_1") (pintype "passive"))
      (node (ref "R74") (pin "2") (pinfunction "2_2") (pintype "passive"))
    )
    (net (code "41") (name "/PULSE_LO_LIMIT") (class "Default")
      (node (ref "R13") (pin "2") (pinfunction "2_2") (pintype "passive"))
      (node (ref "R45") (pin "1") (pinfunction "1_1") (pintype "passive"))
    )
    (net (code "42") (name "/PULSE_OUT") (class "Default")
      (node (ref "C3") (pin "2") (pinfunction "2_2") (pintype "passive"))
      (node (ref "IC14") (pin "5") (pinfunction "NC_5") (pintype "tri_state"))
      (node (ref "Q3") (pin "10") (pinfunction "E_10") (pintype "passive"))
      (node (ref "Q3") (pin "12") (pinfunction "E_12") (pintype "passive"))
      (node (ref "Q3") (pin "14") (pinfunction "E_14") (pintype "passive"))
      (node (ref "Q3") (pin "16") (pinfunction "E_16") (pintype "passive"))
      (node (ref "R19") (pin "2") (pinfunction "2_2") (pintype "passive"))
      (node (ref "R6") (pin "1") (pinfunction "1_1") (pintype "passive"))
      (node (ref "R67") (pin "2") (pinfunction "2_2") (pintype "passive"))
      (node (ref "R7") (pin "1") (pinfunction "1_1") (pintype "passive"))
      (node (ref "U1") (pin "P80") (pinfunction "IO_L46N_1_P80") (pintype "bidirectional"))
    )
    (net (code "43") (name "/SPI_CLK") (class "Default")
      (node (ref "IC4") (pin "9") (pinfunction "A8_9") (pintype "bidirectional"))
      (node (ref "U1") (pin "P120") (pinfunction "IO_L62N_VREF_0_P120") (pintype "bidirectional"))
    )
    (net (code "44") (name "/SPI_MISO") (class "Default")
      (node (ref "R84") (pin "2") (pinfunction "2_2") (pintype "passive"))
      (node (ref "R90") (pin "1") (pinfunction "1_1") (pintype "passive"))
      (node (ref "U1") (pin "P117") (pinfunction "IO_L64P_SCP5_0_P117") (pintype "bidirectional"))
    )
    (net (code "45") (name "/SPI_MOSI") (class "Default")
      (node (ref "IC4") (pin "8") (pinfunction "A7_8") (pintype "bidirectional"))
      (node (ref "U1") (pin "P123") (pinfunction "IO_L37N_GCLK12_0_P123") (pintype "bidirectional"))
    )
    (net (code "46") (name "/SPI_SS") (class "Default")
      (node (ref "IC4") (pin "7") (pinfunction "A6_7") (pintype "bidirectional"))
      (node (ref "U1") (pin "P124") (pinfunction "IO_L37P_GCLK13_0_P124") (pintype "bidirectional"))
    )
    (net (code "47") (name "AGND") (class "Default")
      (node (ref "C100") (pin "-") (pinfunction "-_-") (pintype "passive"))
      (node (ref "C101") (pin "2") (pinfunction "2_2") (pintype "passive"))
      (node (ref "C102") (pin "-") (pinfunction "-_-") (pintype "passive"))
      (node (ref "C103") (pin "2") (pinfunction "2_2") (pintype "passive"))
      (node (ref "C104") (pin "-") (pinfunction "-_-") (pintype "passive"))
      (node (ref "C105") (pin "2") (pinfunction "2_2") (pintype "passive"))
      (node (ref "C106") (pin "-") (pinfunction "-_-") (pintype "passive"))
      (node (ref "C107") (pin "2") (pinfunction "2_2") (pintype "passive"))
      (node (ref "C108") (pin "-") (pinfunction "-_-") (pintype "passive"))
      (node (ref "C109") (pin "2") (pinfunction "2_2") (pintype "passive"))
      (node (ref "C11") (pin "2") (pinfunction "2_2") (pintype "passive"))
      (node (ref "C110") (pin "-") (pinfunction "-_-") (pintype "passive"))
      (node (ref "C111") (pin "2") (pinfunction "2_2") (pintype "passive"))
      (node (ref "C112") (pin "-") (pinfunction "-_-") (pintype "passive"))
      (node (ref "C117") (pin "2") (pinfunction "2_2") (pintype "passive"))
      (node (ref "C118") (pin "-") (pinfunction "-_-") (pintype "passive"))
      (node (ref "C12") (pin "-") (pinfunction "-_-") (pintype "passive"))
      (node (ref "C121") (pin "2") (pinfunction "2_2") (pintype "passive"))
      (node (ref "C122") (pin "-") (pinfunction "-_-") (pintype "passive"))
      (node (ref "C123") (pin "2") (pinfunction "2_2") (pintype "passive"))
      (node (ref "C125") (pin "2") (pinfunction "2_2") (pintype "passive"))
      (node (ref "C131") (pin "2") (pinfunction "2_2") (pintype "passive"))
      (node (ref "C132") (pin "2") (pinfunction "2_2") (pintype "passive"))
      (node (ref "C14") (pin "2") (pinfunction "2_2") (pintype "passive"))
      (node (ref "C145") (pin "2") (pinfunction "2_2") (pintype "passive"))
      (node (ref "C146") (pin "-") (pinfunction "-_-") (pintype "passive"))
      (node (ref "C147") (pin "2") (pinfunction "2_2") (pintype "passive"))
      (node (ref "C148") (pin "-") (pinfunction "-_-") (pintype "passive"))
      (node (ref "C27") (pin "2") (pinfunction "2_2") (pintype "passive"))
      (node (ref "C68") (pin "2") (pinfunction "2_2") (pintype "passive"))
      (node (ref "C95") (pin "2") (pinfunction "2_2") (pintype "passive"))
      (node (ref "C96") (pin "-") (pinfunction "-_-") (pintype "passive"))
      (node (ref "C97") (pin "2") (pinfunction "2_2") (pintype "passive"))
      (node (ref "C98") (pin "-") (pinfunction "-_-") (pintype "passive"))
      (node (ref "C99") (pin "2") (pinfunction "2_2") (pintype "passive"))
      (node (ref "IC1") (pin "4") (pinfunction "-VS_4") (pintype "input"))
      (node (ref "IC10") (pin "4") (pinfunction "GND_4") (pintype "power_in"))
      (node (ref "IC12") (pin "4") (pinfunction "-VS_4") (pintype "input"))
      (node (ref "IC13") (pin "4") (pinfunction "-VS_4") (pintype "input"))
      (node (ref "IC14") (pin "15") (pinfunction "/EN_15") (pintype "bidirectional"))
      (node (ref "IC14") (pin "8") (pinfunction "GND_8") (pintype "power_in"))
      (node (ref "IC17") (pin "4") (pinfunction "-VS_4") (pintype "input"))
      (node (ref "IC19") (pin "4") (pinfunction "-VS_4") (pintype "input"))
      (node (ref "IC20") (pin "4") (pinfunction "-VS_4") (pintype "input"))
      (node (ref "IC21") (pin "4") (pinfunction "-VS_4") (pintype "input"))
      (node (ref "IC23") (pin "4") (pinfunction "-VS_4") (pintype "input"))
      (node (ref "IC24") (pin "4") (pinfunction "-VS_4") (pintype "input"))
      (node (ref "IC25") (pin "4") (pinfunction "-VS_4") (pintype "input"))
      (node (ref "IC26") (pin "4") (pinfunction "-VS_4") (pintype "input"))
      (node (ref "IC32") (pin "1") (pinfunction "GND_1") (pintype "power_in"))
      (node (ref "IC33") (pin "4") (pinfunction "-VS_4") (pintype "input"))
      (node (ref "IC5") (pin "12") (pinfunction "C_12") (pintype "input"))
      (node (ref "IC5") (pin "7") (pinfunction "VSS_7") (pintype "power_in"))
      (node (ref "IC9") (pin "4") (pinfunction "GND_4") (pintype "power_in"))
      (node (ref "L24") (pin "2") (pinfunction "2_2") (pintype "passive"))
      (node (ref "Q3") (pin "5") (pinfunction "C_5") (pintype "passive"))
      (node (ref "Q3") (pin "6") (pinfunction "C2_6") (pintype "passive"))
      (node (ref "Q3") (pin "7") (pinfunction "C_7") (pintype "passive"))
      (node (ref "Q3") (pin "8") (pinfunction "C2_8") (pintype "passive"))
      (node (ref "R18") (pin "A") (pinfunction "A_A") (pintype "passive"))
      (node (ref "R65") (pin "1") (pinfunction "1_1") (pintype "passive"))
      (node (ref "R68") (pin "1") (pinfunction "1_1") (pintype "passive"))
    )
    (net (code "48") (name "GND") (class "Default")
      (node (ref "C13") (pin "2") (pinfunction "2_2") (pintype "passive"))
      (node (ref "C69") (pin "2") (pinfunction "2_2") (pintype "passive"))
      (node (ref "C72") (pin "-") (pinfunction "-_-") (pintype "passive"))
      (node (ref "C80") (pin "2") (pinfunction "2_2") (pintype "passive"))
      (node (ref "C81") (pin "2") (pinfunction "2_2") (pintype "passive"))
      (node (ref "C82") (pin "2") (pinfunction "2_2") (pintype "passive"))
      (node (ref "C83") (pin "2") (pinfunction "2_2") (pintype "passive"))
      (node (ref "C84") (pin "2") (pinfunction "2_2") (pintype "passive"))
      (node (ref "C85") (pin "2") (pinfunction "2_2") (pintype "passive"))
      (node (ref "C86") (pin "2") (pinfunction "2_2") (pintype "passive"))
      (node (ref "C87") (pin "2") (pinfunction "2_2") (pintype "passive"))
      (node (ref "C88") (pin "2") (pinfunction "2_2") (pintype "passive"))
      (node (ref "C89") (pin "2") (pinfunction "2_2") (pintype "passive"))
      (node (ref "C90") (pin "2") (pinfunction "2_2") (pintype "passive"))
      (node (ref "C91") (pin "2") (pinfunction "2_2") (pintype "passive"))
      (node (ref "C92") (pin "2") (pinfunction "2_2") (pintype "passive"))
      (node (ref "C93") (pin "2") (pinfunction "2_2") (pintype "passive"))
      (node (ref "C94") (pin "2") (pinfunction "2_2") (pintype "passive"))
      (node (ref "IC29") (pin "1") (pinfunction "GND_1") (pintype "power_in"))
      (node (ref "IC30") (pin "1") (pinfunction "GND_1") (pintype "power_in"))
      (node (ref "IC4") (pin "10") (pinfunction "GND_10") (pintype "power_in"))
      (node (ref "IC4") (pin "19") (pinfunction "G_19") (pintype "input"))
      (node (ref "IC41") (pin "11") (pinfunction "GND_11") (pintype "power_in"))
      (node (ref "IC8") (pin "1") (pinfunction "GND_1") (pintype "power_in"))
      (node (ref "JP4") (pin "7") (pinfunction "7_7") (pintype "passive"))
      (node (ref "JP7") (pin "6") (pinfunction "6_6") (pintype "passive"))
      (node (ref "JP7") (pin "7") (pinfunction "7_7") (pintype "passive"))
      (node (ref "L2") (pin "2") (pinfunction "2_2") (pintype "passive"))
      (node (ref "L26") (pin "2") (pinfunction "2_2") (pintype "passive"))
      (node (ref "L27") (pin "2") (pinfunction "2_2") (pintype "passive"))
      (node (ref "L28") (pin "2") (pinfunction "2_2") (pintype "passive"))
      (node (ref "L29") (pin "2") (pinfunction "2_2") (pintype "passive"))
      (node (ref "L30") (pin "2") (pinfunction "2_2") (pintype "passive"))
      (node (ref "L31") (pin "2") (pinfunction "2_2") (pintype "passive"))
      (node (ref "QG1") (pin "2") (pinfunction "GND_2") (pintype "power_in"))
      (node (ref "R59") (pin "1") (pinfunction "1_1") (pintype "passive"))
      (node (ref "R90") (pin "2") (pinfunction "2_2") (pintype "passive"))
      (node (ref "R91") (pin "2") (pinfunction "2_2") (pintype "passive"))
      (node (ref "R92") (pin "2") (pinfunction "2_2") (pintype "passive"))
      (node (ref "R93") (pin "2") (pinfunction "2_2") (pintype "passive"))
      (node (ref "R94") (pin "2") (pinfunction "2_2") (pintype "passive"))
      (node (ref "R95") (pin "2") (pinfunction "2_2") (pintype "passive"))
      (node (ref "R97") (pin "1") (pinfunction "1_1") (pintype "passive"))
      (node (ref "S1") (pin "1") (pinfunction "S_1") (pintype "passive"))
      (node (ref "S1") (pin "2") (pinfunction "S1_2") (pintype "passive"))
      (node (ref "SL1") (pin "5") (pinfunction "5_5") (pintype "passive"))
      (node (ref "U1") (pin "P108") (pinfunction "GND_P108") (pintype "power_in"))
      (node (ref "U1") (pin "P113") (pinfunction "GND_P113") (pintype "power_in"))
      (node (ref "U1") (pin "P13") (pinfunction "GND_P13") (pintype "power_in"))
      (node (ref "U1") (pin "P130") (pinfunction "GND_P130") (pintype "power_in"))
      (node (ref "U1") (pin "P136") (pinfunction "GND_P136") (pintype "power_in"))
      (node (ref "U1") (pin "P144") (pinfunction "IO_L1P_HSWAPEN_0_P144") (pintype "bidirectional"))
      (node (ref "U1") (pin "P25") (pinfunction "GND_P25") (pintype "power_in"))
      (node (ref "U1") (pin "P3") (pinfunction "GND_P3") (pintype "power_in"))
      (node (ref "U1") (pin "P49") (pinfunction "GND_P49") (pintype "power_in"))
      (node (ref "U1") (pin "P54") (pinfunction "GND_P54") (pintype "power_in"))
      (node (ref "U1") (pin "P60") (pinfunction "IO_L13P_M1_2_P60") (pintype "bidirectional"))
      (node (ref "U1") (pin "P68") (pinfunction "GND_P68") (pintype "power_in"))
      (node (ref "U1") (pin "P77") (pinfunction "GND_P77") (pintype "power_in"))
      (node (ref "U1") (pin "P91") (pinfunction "GND_P91") (pintype "power_in"))
      (node (ref "U1") (pin "P96") (pinfunction "GND_P96") (pintype "power_in"))
    )
    (net (code "49") (name "GNDA") (class "Default")
      (node (ref "C137") (pin "2") (pinfunction "2_2") (pintype "passive"))
      (node (ref "C138") (pin "2") (pinfunction "2_2") (pintype "passive"))
      (node (ref "C139") (pin "2") (pinfunction "2_2") (pintype "passive"))
      (node (ref "C140") (pin "2") (pinfunction "2_2") (pintype "passive"))
      (node (ref "C141") (pin "2") (pinfunction "2_2") (pintype "passive"))
      (node (ref "C142") (pin "2") (pinfunction "2_2") (pintype "passive"))
      (node (ref "C143") (pin "2") (pinfunction "2_2") (pintype "passive"))
      (node (ref "C144") (pin "2") (pinfunction "2_2") (pintype "passive"))
      (node (ref "C29") (pin "-") (pinfunction "-_-") (pintype "passive"))
      (node (ref "C30") (pin "2") (pinfunction "2_2") (pintype "passive"))
      (node (ref "C31") (pin "2") (pinfunction "2_2") (pintype "passive"))
      (node (ref "C73") (pin "2") (pinfunction "2_2") (pintype "passive"))
      (node (ref "C74") (pin "2") (pinfunction "2_2") (pintype "passive"))
      (node (ref "C76") (pin "2") (pinfunction "2_2") (pintype "passive"))
      (node (ref "C77") (pin "2") (pinfunction "2_2") (pintype "passive"))
      (node (ref "IC16") (pin "7") (pinfunction "VSS_7") (pintype "power_in"))
      (node (ref "IC18") (pin "7") (pinfunction "VSS_7") (pintype "power_in"))
      (node (ref "IC2") (pin "7") (pinfunction "VSS_7") (pintype "power_in"))
      (node (ref "IC22") (pin "7") (pinfunction "VSS_7") (pintype "power_in"))
      (node (ref "IC3") (pin "7") (pinfunction "VSS_7") (pintype "power_in"))
      (node (ref "IC3") (pin "8") (pinfunction "A_8") (pintype "tri_state"))
      (node (ref "IC7") (pin "12") (pinfunction "C_12") (pintype "input"))
      (node (ref "IC7") (pin "6") (pinfunction "C_6") (pintype "input"))
      (node (ref "IC7") (pin "7") (pinfunction "VSS_7") (pintype "power_in"))
      (node (ref "L26") (pin "1") (pinfunction "1_1") (pintype "passive"))
      (node (ref "L27") (pin "1") (pinfunction "1_1") (pintype "passive"))
      (node (ref "L28") (pin "1") (pinfunction "1_1") (pintype "passive"))
      (node (ref "L29") (pin "1") (pinfunction "1_1") (pintype "passive"))
      (node (ref "L30") (pin "1") (pinfunction "1_1") (pintype "passive"))
      (node (ref "L31") (pin "1") (pinfunction "1_1") (pintype "passive"))
      (node (ref "L4") (pin "2") (pinfunction "2_2") (pintype "passive"))
    )
    (net (code "50") (name "Net-(C6-Pad1)") (class "Default")
      (node (ref "C6") (pin "1") (pinfunction "1_1") (pintype "passive"))
      (node (ref "R8") (pin "1") (pinfunction "1_1") (pintype "passive"))
    )
    (net (code "51") (name "Net-(C24-Pad2)") (class "Default")
      (node (ref "C24") (pin "2") (pinfunction "2_2") (pintype "passive"))
      (node (ref "R69") (pin "2") (pinfunction "2_2") (pintype "passive"))
    )
    (net (code "52") (name "Net-(C37-Pad1)") (class "Default")
      (node (ref "C37") (pin "1") (pinfunction "1_1") (pintype "passive"))
      (node (ref "R28") (pin "1") (pinfunction "1_1") (pintype "passive"))
    )
    (net (code "53") (name "Net-(C43-Pad1)") (class "Default")
      (node (ref "C43") (pin "1") (pinfunction "1_1") (pintype "passive"))
      (node (ref "R31") (pin "1") (pinfunction "1_1") (pintype "passive"))
    )
    (net (code "54") (name "Net-(C49-Pad1)") (class "Default")
      (node (ref "C49") (pin "1") (pinfunction "1_1") (pintype "passive"))
      (node (ref "R34") (pin "1") (pinfunction "1_1") (pintype "passive"))
    )
    (net (code "55") (name "Net-(C55-Pad1)") (class "Default")
      (node (ref "C55") (pin "1") (pinfunction "1_1") (pintype "passive"))
      (node (ref "R37") (pin "1") (pinfunction "1_1") (pintype "passive"))
    )
    (net (code "56") (name "Net-(C61-Pad1)") (class "Default")
      (node (ref "C61") (pin "1") (pinfunction "1_1") (pintype "passive"))
      (node (ref "R40") (pin "1") (pinfunction "1_1") (pintype "passive"))
    )
    (net (code "57") (name "Net-(IC1-+VS)") (class "Default")
      (node (ref "C95") (pin "1") (pinfunction "1_1") (pintype "passive"))
      (node (ref "C96") (pin "+") (pinfunction "+_+") (pintype "passive"))
      (node (ref "IC1") (pin "7") (pinfunction "+VS_7") (pintype "input"))
      (node (ref "L5") (pin "2") (pinfunction "2_2") (pintype "passive"))
    )
    (net (code "58") (name "Net-(IC1-IN+)") (class "Default")
      (node (ref "C33") (pin "1") (pinfunction "1_1") (pintype "passive"))
      (node (ref "C34") (pin "1") (pinfunction "1_1") (pintype "passive"))
      (node (ref "C64") (pin "1") (pinfunction "1_1") (pintype "passive"))
      (node (ref "IC1") (pin "3") (pinfunction "IN+_3") (pintype "input"))
      (node (ref "R27") (pin "2") (pinfunction "2_2") (pintype "passive"))
    )
    (net (code "59") (name "Net-(IC1-IN-)") (class "Default")
      (node (ref "C35") (pin "2") (pinfunction "2_2") (pintype "passive"))
      (node (ref "C36") (pin "1") (pinfunction "1_1") (pintype "passive"))
      (node (ref "C50") (pin "2") (pinfunction "2_2") (pintype "passive"))
      (node (ref "C64") (pin "2") (pinfunction "2_2") (pintype "passive"))
      (node (ref "IC1") (pin "2") (pinfunction "IN-_2") (pintype "input"))
      (node (ref "IC1") (pin "6") (pinfunction "OUT_6") (pintype "output"))
      (node (ref "IC22") (pin "1") (pinfunction "A_1") (pintype "tri_state"))
      (node (ref "R28") (pin "2") (pinfunction "2_2") (pintype "passive"))
    )
    (net (code "60") (name "Net-(IC2A-A)") (class "Default")
      (node (ref "IC2") (pin "1") (pinfunction "A_1") (pintype "tri_state"))
      (node (ref "R66") (pin "2") (pinfunction "2_2") (pintype "passive"))
    )
    (net (code "61") (name "Net-(IC2B-A)") (class "Default")
      (node (ref "IC2") (pin "4") (pinfunction "A_4") (pintype "tri_state"))
      (node (ref "R5") (pin "2") (pinfunction "2_2") (pintype "passive"))
    )
    (net (code "62") (name "Net-(IC2C-A)") (class "Default")
      (node (ref "IC2") (pin "8") (pinfunction "A_8") (pintype "tri_state"))
      (node (ref "R6") (pin "2") (pinfunction "2_2") (pintype "passive"))
    )
    (net (code "63") (name "Net-(IC2D-A)") (class "Default")
      (node (ref "IC2") (pin "11") (pinfunction "A_11") (pintype "tri_state"))
      (node (ref "R7") (pin "2") (pinfunction "2_2") (pintype "passive"))
    )
    (net (code "64") (name "Net-(IC3A-B)") (class "Default")
      (node (ref "IC3") (pin "2") (pinfunction "B_2") (pintype "tri_state"))
      (node (ref "R64") (pin "1") (pinfunction "1_1") (pintype "passive"))
    )
    (net (code "65") (name "Net-(IC3B-B)") (class "Default")
      (node (ref "IC3") (pin "3") (pinfunction "B_3") (pintype "tri_state"))
      (node (ref "R71") (pin "1") (pinfunction "1_1") (pintype "passive"))
    )
    (net (code "66") (name "Net-(IC3B-C)") (class "Default")
      (node (ref "IC3") (pin "5") (pinfunction "C_5") (pintype "input"))
      (node (ref "IC3") (pin "9") (pinfunction "B_9") (pintype "tri_state"))
      (node (ref "R72") (pin "1") (pinfunction "1_1") (pintype "passive"))
    )
    (net (code "67") (name "Net-(IC3D-A)") (class "Default")
      (node (ref "IC3") (pin "11") (pinfunction "A_11") (pintype "tri_state"))
      (node (ref "R4") (pin "2") (pinfunction "2_2") (pintype "passive"))
    )
    (net (code "68") (name "Net-(IC4A-B1)") (class "Default")
      (node (ref "IC4") (pin "18") (pinfunction "B1_18") (pintype "bidirectional"))
      (node (ref "JP3") (pin "1") (pinfunction "1_1") (pintype "passive"))
    )
    (net (code "69") (name "Net-(IC4A-B2)") (class "Default")
      (node (ref "IC4") (pin "17") (pinfunction "B2_17") (pintype "bidirectional"))
      (node (ref "JP3") (pin "2") (pinfunction "2_2") (pintype "passive"))
    )
    (net (code "70") (name "Net-(IC4A-B3)") (class "Default")
      (node (ref "IC4") (pin "16") (pinfunction "B3_16") (pintype "bidirectional"))
      (node (ref "JP3") (pin "3") (pinfunction "3_3") (pintype "passive"))
    )
    (net (code "71") (name "Net-(IC4A-B4)") (class "Default")
      (node (ref "IC4") (pin "15") (pinfunction "B4_15") (pintype "bidirectional"))
      (node (ref "JP3") (pin "4") (pinfunction "4_4") (pintype "passive"))
    )
    (net (code "72") (name "Net-(IC4A-B5)") (class "Default")
      (node (ref "IC4") (pin "14") (pinfunction "B5_14") (pintype "bidirectional"))
      (node (ref "JP4") (pin "1") (pinfunction "1_1") (pintype "passive"))
    )
    (net (code "73") (name "Net-(IC4A-B6)") (class "Default")
      (node (ref "IC4") (pin "13") (pinfunction "B6_13") (pintype "bidirectional"))
      (node (ref "JP4") (pin "3") (pinfunction "3_3") (pintype "passive"))
    )
    (net (code "74") (name "Net-(IC4A-B7)") (class "Default")
      (node (ref "IC4") (pin "12") (pinfunction "B7_12") (pintype "bidirectional"))
      (node (ref "JP4") (pin "4") (pinfunction "4_4") (pintype "passive"))
    )
    (net (code "75") (name "Net-(IC4A-B8)") (class "Default")
      (node (ref "IC4") (pin "11") (pinfunction "B8_11") (pintype "bidirectional"))
      (node (ref "JP4") (pin "6") (pinfunction "6_6") (pintype "passive"))
    )
    (net (code "76") (name "Net-(IC5A-B)") (class "Default")
      (node (ref "C9") (pin "2") (pinfunction "2_2") (pintype "passive"))
      (node (ref "IC5") (pin "2") (pinfunction "B_2") (pintype "tri_state"))
    )
    (net (code "77") (name "Net-(IC5B-A)") (class "Default")
      (node (ref "IC5") (pin "4") (pinfunction "A_4") (pintype "tri_state"))
      (node (ref "R3") (pin "2") (pinfunction "2_2") (pintype "passive"))
    )
    (net (code "78") (name "Net-(IC5C-A)") (class "Default")
      (node (ref "C7") (pin "1") (pinfunction "1_1") (pintype "passive"))
      (node (ref "IC5") (pin "8") (pinfunction "A_8") (pintype "tri_state"))
    )
    (net (code "79") (name "Net-(IC6-VOUT1)") (class "Default")
      (node (ref "C70") (pin "+") (pinfunction "+_+") (pintype "passive"))
      (node (ref "IC6") (pin "2") (pinfunction "VOUT1_2") (pintype "power_in"))
      (node (ref "IC6") (pin "4") (pinfunction "VOUT2_4") (pintype "power_in"))
      (node (ref "L1") (pin "1") (pinfunction "1_1") (pintype "passive"))
    )
    (net (code "80") (name "Net-(IC7A-B)") (class "Default")
      (node (ref "IC7") (pin "2") (pinfunction "B_2") (pintype "tri_state"))
      (node (ref "R26") (pin "1") (pinfunction "1_1") (pintype "passive"))
    )
    (net (code "81") (name "Net-(IC7B-A)") (class "Default")
      (node (ref "C32") (pin "1") (pinfunction "1_1") (pintype "passive"))
      (node (ref "C33") (pin "2") (pinfunction "2_2") (pintype "passive"))
      (node (ref "C35") (pin "1") (pinfunction "1_1") (pintype "passive"))
      (node (ref "IC7") (pin "4") (pinfunction "A_4") (pintype "tri_state"))
      (node (ref "R26") (pin "2") (pinfunction "2_2") (pintype "passive"))
    )
    (net (code "82") (name "Net-(IC7B-B)") (class "Default")
      (node (ref "IC7") (pin "3") (pinfunction "B_3") (pintype "tri_state"))
      (node (ref "R27") (pin "1") (pinfunction "1_1") (pintype "passive"))
    )
    (net (code "83") (name "Net-(IC9A-IN+)") (class "Default")
      (node (ref "C68") (pin "1") (pinfunction "1_1") (pintype "passive"))
      (node (ref "IC9") (pin "3") (pinfunction "IN+_3") (pintype "input"))
      (node (ref "R45") (pin "2") (pinfunction "2_2") (pintype "passive"))
    )
    (net (code "84") (name "Net-(IC9A-IN-)") (class "Default")
      (node (ref "IC9") (pin "2") (pinfunction "IN-_2") (pintype "input"))
      (node (ref "R19") (pin "1") (pinfunction "1_1") (pintype "passive"))
      (node (ref "R65") (pin "2") (pinfunction "2_2") (pintype "passive"))
    )
    (net (code "85") (name "Net-(IC9A-OUT)") (class "Default")
      (node (ref "IC9") (pin "1") (pinfunction "OUT_1") (pintype "output"))
      (node (ref "Q3") (pin "13") (pinfunction "B_13") (pintype "passive"))
    )
    (net (code "86") (name "Net-(IC9B-IN+)") (class "Default")
      (node (ref "C27") (pin "1") (pinfunction "1_1") (pintype "passive"))
      (node (ref "IC9") (pin "5") (pinfunction "IN+_5") (pintype "input"))
      (node (ref "R73") (pin "2") (pinfunction "2_2") (pintype "passive"))
    )
    (net (code "87") (name "Net-(IC9B-IN-)") (class "Default")
      (node (ref "IC9") (pin "6") (pinfunction "IN-_6") (pintype "input"))
      (node (ref "R67") (pin "1") (pinfunction "1_1") (pintype "passive"))
      (node (ref "R68") (pin "2") (pinfunction "2_2") (pintype "passive"))
    )
    (net (code "88") (name "Net-(IC9B-OUT)") (class "Default")
      (node (ref "IC9") (pin "7") (pinfunction "OUT_7") (pintype "output"))
      (node (ref "Q3") (pin "9") (pinfunction "B_9") (pintype "passive"))
    )
    (net (code "89") (name "Net-(IC10A-IN+)") (class "Default")
      (node (ref "C131") (pin "1") (pinfunction "1_1") (pintype "passive"))
      (node (ref "C34") (pin "2") (pinfunction "2_2") (pintype "passive"))
      (node (ref "C36") (pin "2") (pinfunction "2_2") (pintype "passive"))
      (node (ref "C37") (pin "2") (pinfunction "2_2") (pintype "passive"))
      (node (ref "C38") (pin "2") (pinfunction "2_2") (pintype "passive"))
      (node (ref "C4") (pin "2") (pinfunction "2_2") (pintype "passive"))
      (node (ref "C42") (pin "2") (pinfunction "2_2") (pintype "passive"))
      (node (ref "C43") (pin "2") (pinfunction "2_2") (pintype "passive"))
      (node (ref "C46") (pin "2") (pinfunction "2_2") (pintype "passive"))
      (node (ref "C48") (pin "2") (pinfunction "2_2") (pintype "passive"))
      (node (ref "C49") (pin "2") (pinfunction "2_2") (pintype "passive"))
      (node (ref "C5") (pin "2") (pinfunction "2_2") (pintype "passive"))
      (node (ref "C52") (pin "2") (pinfunction "2_2") (pintype "passive"))
      (node (ref "C54") (pin "2") (pinfunction "2_2") (pintype "passive"))
      (node (ref "C55") (pin "2") (pinfunction "2_2") (pintype "passive"))
      (node (ref "C56") (pin "2") (pinfunction "2_2") (pintype "passive"))
      (node (ref "C60") (pin "2") (pinfunction "2_2") (pintype "passive"))
      (node (ref "C61") (pin "2") (pinfunction "2_2") (pintype "passive"))
      (node (ref "C7") (pin "2") (pinfunction "2_2") (pintype "passive"))
      (node (ref "IC10") (pin "3") (pinfunction "IN+_3") (pintype "input"))
      (node (ref "IC10") (pin "6") (pinfunction "IN-_6") (pintype "input"))
      (node (ref "IC16") (pin "1") (pinfunction "A_1") (pintype "tri_state"))
      (node (ref "IC18") (pin "1") (pinfunction "A_1") (pintype "tri_state"))
      (node (ref "IC20") (pin "3") (pinfunction "IN+_3") (pintype "input"))
      (node (ref "IC3") (pin "1") (pinfunction "A_1") (pintype "tri_state"))
      (node (ref "IC3") (pin "4") (pinfunction "A_4") (pintype "tri_state"))
      (node (ref "IC32") (pin "2") (pinfunction "VOUT1_2") (pintype "power_in"))
      (node (ref "IC32") (pin "4") (pinfunction "VOUT2_4") (pintype "power_in"))
      (node (ref "IC33") (pin "3") (pinfunction "IN+_3") (pintype "input"))
      (node (ref "R2") (pin "1") (pinfunction "1_1") (pintype "passive"))
      (node (ref "R69") (pin "1") (pinfunction "1_1") (pintype "passive"))
    )
    (net (code "90") (name "Net-(IC10A-IN-)") (class "Default")
      (node (ref "C10") (pin "2") (pinfunction "2_2") (pintype "passive"))
      (node (ref "IC10") (pin "2") (pinfunction "IN-_2") (pintype "input"))
      (node (ref "R16") (pin "2") (pinfunction "2_2") (pintype "passive"))
      (node (ref "R17") (pin "2") (pinfunction "2_2") (pintype "passive"))
    )
    (net (code "91") (name "Net-(IC10A-OUT)") (class "Default")
      (node (ref "C10") (pin "1") (pinfunction "1_1") (pintype "passive"))
      (node (ref "IC10") (pin "1") (pinfunction "OUT_1") (pintype "output"))
      (node (ref "JP6") (pin "1") (pinfunction "1_1") (pintype "passive"))
      (node (ref "R14") (pin "1") (pinfunction "1_1") (pintype "passive"))
    )
    (net (code "92") (name "Net-(IC10B-IN+)") (class "Default")
      (node (ref "IC10") (pin "5") (pinfunction "IN+_5") (pintype "input"))
      (node (ref "R14") (pin "2") (pinfunction "2_2") (pintype "passive"))
      (node (ref "R15") (pin "1") (pinfunction "1_1") (pintype "passive"))
    )
    (net (code "93") (name "Net-(IC10B-OUT)") (class "Default")
      (node (ref "IC10") (pin "7") (pinfunction "OUT_7") (pintype "output"))
      (node (ref "JP6") (pin "3") (pinfunction "3_3") (pintype "passive"))
      (node (ref "R15") (pin "2") (pinfunction "2_2") (pintype "passive"))
      (node (ref "R70") (pin "E") (pinfunction "E_E") (pintype "passive"))
    )
    (net (code "94") (name "Net-(IC10C-VCC)") (class "Default")
      (node (ref "C11") (pin "1") (pinfunction "1_1") (pintype "passive"))
      (node (ref "C12") (pin "+") (pinfunction "+_+") (pintype "passive"))
      (node (ref "IC10") (pin "8") (pinfunction "VCC_8") (pintype "power_in"))
      (node (ref "L14") (pin "2") (pinfunction "2_2") (pintype "passive"))
    )
    (net (code "95") (name "Net-(IC12-+VS)") (class "Default")
      (node (ref "C117") (pin "1") (pinfunction "1_1") (pintype "passive"))
      (node (ref "C118") (pin "+") (pinfunction "+_+") (pintype "passive"))
      (node (ref "IC12") (pin "7") (pinfunction "+VS_7") (pintype "input"))
      (node (ref "L16") (pin "2") (pinfunction "2_2") (pintype "passive"))
    )
    (net (code "96") (name "Net-(IC12-IN+)") (class "Default")
      (node (ref "IC12") (pin "3") (pinfunction "IN+_3") (pintype "input"))
      (node (ref "R2") (pin "2") (pinfunction "2_2") (pintype "passive"))
      (node (ref "R3") (pin "1") (pinfunction "1_1") (pintype "passive"))
    )
    (net (code "97") (name "Net-(IC12-IN-)") (class "Default")
      (node (ref "C1") (pin "2") (pinfunction "2_2") (pintype "passive"))
      (node (ref "IC12") (pin "2") (pinfunction "IN-_2") (pintype "input"))
      (node (ref "R1") (pin "2") (pinfunction "2_2") (pintype "passive"))
      (node (ref "R4") (pin "1") (pinfunction "1_1") (pintype "passive"))
    )
    (net (code "98") (name "Net-(IC12-OUT)") (class "Default")
      (node (ref "C1") (pin "1") (pinfunction "1_1") (pintype "passive"))
      (node (ref "C123") (pin "1") (pinfunction "1_1") (pintype "passive"))
      (node (ref "C2") (pin "2") (pinfunction "2_2") (pintype "passive"))
      (node (ref "IC12") (pin "6") (pinfunction "OUT_6") (pintype "output"))
      (node (ref "IC14") (pin "13") (pinfunction "NO_13") (pintype "input"))
      (node (ref "IC3") (pin "10") (pinfunction "B_10") (pintype "tri_state"))
      (node (ref "IC5") (pin "3") (pinfunction "B_3") (pintype "tri_state"))
      (node (ref "R5") (pin "1") (pinfunction "1_1") (pintype "passive"))
      (node (ref "R66") (pin "1") (pinfunction "1_1") (pintype "passive"))
    )
    (net (code "99") (name "Net-(IC13-+VS)") (class "Default")
      (node (ref "C121") (pin "1") (pinfunction "1_1") (pintype "passive"))
      (node (ref "C122") (pin "+") (pinfunction "+_+") (pintype "passive"))
      (node (ref "IC13") (pin "7") (pinfunction "+VS_7") (pintype "input"))
      (node (ref "L18") (pin "2") (pinfunction "2_2") (pintype "passive"))
    )
    (net (code "100") (name "Net-(IC13-IN+)") (class "Default")
      (node (ref "C3") (pin "1") (pinfunction "1_1") (pintype "passive"))
      (node (ref "IC13") (pin "3") (pinfunction "IN+_3") (pintype "input"))
      (node (ref "IC2") (pin "10") (pinfunction "B_10") (pintype "tri_state"))
      (node (ref "IC2") (pin "9") (pinfunction "B_9") (pintype "tri_state"))
      (node (ref "IC5") (pin "9") (pinfunction "B_9") (pintype "tri_state"))
      (node (ref "R8") (pin "2") (pinfunction "2_2") (pintype "passive"))
    )
    (net (code "101") (name "Net-(IC13-IN-)") (class "Default")
      (node (ref "C5") (pin "1") (pinfunction "1_1") (pintype "passive"))
      (node (ref "C6") (pin "2") (pinfunction "2_2") (pintype "passive"))
      (node (ref "IC13") (pin "2") (pinfunction "IN-_2") (pintype "input"))
      (node (ref "IC14") (pin "9") (pinfunction "COM_9") (pintype "tri_state"))
      (node (ref "R64") (pin "2") (pinfunction "2_2") (pintype "passive"))
      (node (ref "R71") (pin "2") (pinfunction "2_2") (pintype "passive"))
    )
    (net (code "102") (name "Net-(IC13-OUT)") (class "Default")
      (node (ref "C24") (pin "1") (pinfunction "1_1") (pintype "passive"))
      (node (ref "C4") (pin "1") (pinfunction "1_1") (pintype "passive"))
      (node (ref "C8") (pin "2") (pinfunction "2_2") (pintype "passive"))
      (node (ref "C9") (pin "1") (pinfunction "1_1") (pintype "passive"))
      (node (ref "IC13") (pin "6") (pinfunction "OUT_6") (pintype "output"))
      (node (ref "IC14") (pin "3") (pinfunction "NO_3") (pintype "input"))
      (node (ref "JP5") (pin "1") (pinfunction "1_1") (pintype "passive"))
      (node (ref "PAD4") (pin "1") (pinfunction "P_1") (pintype "passive"))
      (node (ref "R63") (pin "2") (pinfunction "2_2") (pintype "passive"))
    )
    (net (code "103") (name "Net-(IC14A-COM)") (class "Default")
      (node (ref "IC14") (pin "4") (pinfunction "COM_4") (pintype "tri_state"))
      (node (ref "R1") (pin "1") (pinfunction "1_1") (pintype "passive"))
    )
    (net (code "104") (name "Net-(IC14A-NC)") (class "Default")
      (node (ref "IC14") (pin "2") (pinfunction "NC_2") (pintype "tri_state"))
      (node (ref "JP2") (pin "2") (pinfunction "2_2") (pintype "passive"))
    )
    (net (code "105") (name "Net-(IC14B-COM)") (class "Default")
      (node (ref "IC14") (pin "12") (pinfunction "COM_12") (pintype "tri_state"))
      (node (ref "IC14") (pin "7") (pinfunction "COM_7") (pintype "tri_state"))
    )
    (net (code "106") (name "Net-(IC14B-NO)") (class "Default")
      (node (ref "IC14") (pin "6") (pinfunction "NO_6") (pintype "input"))
      (node (ref "Q3") (pin "11") (pinfunction "B_11") (pintype "passive"))
      (node (ref "Q3") (pin "15") (pinfunction "B_15") (pintype "passive"))
    )
    (net (code "107") (name "Net-(IC14C-NC)") (class "Default")
      (node (ref "IC14") (pin "11") (pinfunction "NC_11") (pintype "tri_state"))
      (node (ref "R63") (pin "1") (pinfunction "1_1") (pintype "passive"))
    )
    (net (code "108") (name "Net-(IC14C-NO)") (class "Default")
      (node (ref "C8") (pin "1") (pinfunction "1_1") (pintype "passive"))
      (node (ref "IC14") (pin "10") (pinfunction "NO_10") (pintype "input"))
    )
    (net (code "109") (name "Net-(IC14E-NC)") (class "Default")
      (node (ref "C2") (pin "1") (pinfunction "1_1") (pintype "passive"))
      (node (ref "IC14") (pin "14") (pinfunction "NC_14") (pintype "tri_state"))
      (node (ref "IC2") (pin "2") (pinfunction "B_2") (pintype "tri_state"))
      (node (ref "IC2") (pin "3") (pinfunction "B_3") (pintype "tri_state"))
      (node (ref "IC5") (pin "1") (pinfunction "A_1") (pintype "tri_state"))
    )
    (net (code "110") (name "Net-(IC16A-B)") (class "Default")
      (node (ref "IC16") (pin "2") (pinfunction "B_2") (pintype "tri_state"))
      (node (ref "R29") (pin "1") (pinfunction "1_1") (pintype "passive"))
    )
    (net (code "111") (name "Net-(IC16B-A)") (class "Default")
      (node (ref "C39") (pin "2") (pinfunction "2_2") (pintype "passive"))
      (node (ref "C40") (pin "2") (pinfunction "2_2") (pintype "passive"))
      (node (ref "C41") (pin "1") (pinfunction "1_1") (pintype "passive"))
      (node (ref "IC16") (pin "4") (pinfunction "A_4") (pintype "tri_state"))
    )
    (net (code "112") (name "Net-(IC16B-B)") (class "Default")
      (node (ref "IC16") (pin "3") (pinfunction "B_3") (pintype "tri_state"))
      (node (ref "R30") (pin "1") (pinfunction "1_1") (pintype "passive"))
    )
    (net (code "113") (name "Net-(IC16C-A)") (class "Default")
      (node (ref "C39") (pin "1") (pinfunction "1_1") (pintype "passive"))
      (node (ref "C42") (pin "1") (pinfunction "1_1") (pintype "passive"))
      (node (ref "C44") (pin "2") (pinfunction "2_2") (pintype "passive"))
      (node (ref "C62") (pin "2") (pinfunction "2_2") (pintype "passive"))
      (node (ref "IC16") (pin "8") (pinfunction "A_8") (pintype "tri_state"))
      (node (ref "IC17") (pin "2") (pinfunction "IN-_2") (pintype "input"))
      (node (ref "IC17") (pin "6") (pinfunction "OUT_6") (pintype "output"))
      (node (ref "R30") (pin "2") (pinfunction "2_2") (pintype "passive"))
      (node (ref "R31") (pin "2") (pinfunction "2_2") (pintype "passive"))
    )
    (net (code "114") (name "Net-(IC16C-B)") (class "Default")
      (node (ref "IC16") (pin "9") (pinfunction "B_9") (pintype "tri_state"))
      (node (ref "R32") (pin "1") (pinfunction "1_1") (pintype "passive"))
    )
    (net (code "115") (name "Net-(IC16D-A)") (class "Default")
      (node (ref "C44") (pin "1") (pinfunction "1_1") (pintype "passive"))
      (node (ref "C45") (pin "2") (pinfunction "2_2") (pintype "passive"))
      (node (ref "C47") (pin "1") (pinfunction "1_1") (pintype "passive"))
      (node (ref "IC16") (pin "11") (pinfunction "A_11") (pintype "tri_state"))
      (node (ref "R32") (pin "2") (pinfunction "2_2") (pintype "passive"))
    )
    (net (code "116") (name "Net-(IC16D-B)") (class "Default")
      (node (ref "IC16") (pin "10") (pinfunction "B_10") (pintype "tri_state"))
      (node (ref "R33") (pin "1") (pinfunction "1_1") (pintype "passive"))
    )
    (net (code "117") (name "Net-(IC17-+VS)") (class "Default")
      (node (ref "C101") (pin "1") (pinfunction "1_1") (pintype "passive"))
      (node (ref "C102") (pin "+") (pinfunction "+_+") (pintype "passive"))
      (node (ref "IC17") (pin "7") (pinfunction "+VS_7") (pintype "input"))
      (node (ref "L8") (pin "2") (pinfunction "2_2") (pintype "passive"))
    )
    (net (code "118") (name "Net-(IC17-IN+)") (class "Default")
      (node (ref "C38") (pin "1") (pinfunction "1_1") (pintype "passive"))
      (node (ref "C41") (pin "2") (pinfunction "2_2") (pintype "passive"))
      (node (ref "C62") (pin "1") (pinfunction "1_1") (pintype "passive"))
      (node (ref "IC17") (pin "3") (pinfunction "IN+_3") (pintype "input"))
      (node (ref "R29") (pin "2") (pinfunction "2_2") (pintype "passive"))
    )
    (net (code "119") (name "Net-(IC18A-B)") (class "Default")
      (node (ref "IC18") (pin "2") (pinfunction "B_2") (pintype "tri_state"))
      (node (ref "R38") (pin "1") (pinfunction "1_1") (pintype "passive"))
    )
    (net (code "120") (name "Net-(IC18B-A)") (class "Default")
      (node (ref "C57") (pin "2") (pinfunction "2_2") (pintype "passive"))
      (node (ref "C58") (pin "2") (pinfunction "2_2") (pintype "passive"))
      (node (ref "C59") (pin "1") (pinfunction "1_1") (pintype "passive"))
      (node (ref "IC18") (pin "4") (pinfunction "A_4") (pintype "tri_state"))
    )
    (net (code "121") (name "Net-(IC18B-B)") (class "Default")
      (node (ref "IC18") (pin "3") (pinfunction "B_3") (pintype "tri_state"))
      (node (ref "R39") (pin "1") (pinfunction "1_1") (pintype "passive"))
    )
    (net (code "122") (name "Net-(IC18C-A)") (class "Default")
      (node (ref "C133") (pin "2") (pinfunction "2_2") (pintype "passive"))
      (node (ref "C57") (pin "1") (pinfunction "1_1") (pintype "passive"))
      (node (ref "C60") (pin "1") (pinfunction "1_1") (pintype "passive"))
      (node (ref "C63") (pin "2") (pinfunction "2_2") (pintype "passive"))
      (node (ref "IC18") (pin "8") (pinfunction "A_8") (pintype "tri_state"))
      (node (ref "IC23") (pin "2") (pinfunction "IN-_2") (pintype "input"))
      (node (ref "IC23") (pin "6") (pinfunction "OUT_6") (pintype "output"))
      (node (ref "R39") (pin "2") (pinfunction "2_2") (pintype "passive"))
      (node (ref "R40") (pin "2") (pinfunction "2_2") (pintype "passive"))
    )
    (net (code "123") (name "Net-(IC18C-B)") (class "Default")
      (node (ref "IC18") (pin "9") (pinfunction "B_9") (pintype "tri_state"))
      (node (ref "R35") (pin "1") (pinfunction "1_1") (pintype "passive"))
    )
    (net (code "124") (name "Net-(IC18D-A)") (class "Default")
      (node (ref "C133") (pin "1") (pinfunction "1_1") (pintype "passive"))
      (node (ref "C134") (pin "2") (pinfunction "2_2") (pintype "passive"))
      (node (ref "C53") (pin "1") (pinfunction "1_1") (pintype "passive"))
      (node (ref "IC18") (pin "11") (pinfunction "A_11") (pintype "tri_state"))
      (node (ref "R35") (pin "2") (pinfunction "2_2") (pintype "passive"))
    )
    (net (code "125") (name "Net-(IC18D-B)") (class "Default")
      (node (ref "IC18") (pin "10") (pinfunction "B_10") (pintype "tri_state"))
      (node (ref "R36") (pin "1") (pinfunction "1_1") (pintype "passive"))
    )
    (net (code "126") (name "Net-(IC19-+VS)") (class "Default")
      (node (ref "C103") (pin "1") (pinfunction "1_1") (pintype "passive"))
      (node (ref "C104") (pin "+") (pinfunction "+_+") (pintype "passive"))
      (node (ref "IC19") (pin "7") (pinfunction "+VS_7") (pintype "input"))
      (node (ref "L9") (pin "2") (pinfunction "2_2") (pintype "passive"))
    )
    (net (code "127") (name "Net-(IC19-IN+)") (class "Default")
      (node (ref "C45") (pin "1") (pinfunction "1_1") (pintype "passive"))
      (node (ref "C46") (pin "1") (pinfunction "1_1") (pintype "passive"))
      (node (ref "C65") (pin "1") (pinfunction "1_1") (pintype "passive"))
      (node (ref "IC19") (pin "3") (pinfunction "IN+_3") (pintype "input"))
      (node (ref "R33") (pin "2") (pinfunction "2_2") (pintype "passive"))
    )
    (net (code "128") (name "Net-(IC19-IN-)") (class "Default")
      (node (ref "C47") (pin "2") (pinfunction "2_2") (pintype "passive"))
      (node (ref "C48") (pin "1") (pinfunction "1_1") (pintype "passive"))
      (node (ref "C51") (pin "2") (pinfunction "2_2") (pintype "passive"))
      (node (ref "C65") (pin "2") (pinfunction "2_2") (pintype "passive"))
      (node (ref "IC19") (pin "2") (pinfunction "IN-_2") (pintype "input"))
      (node (ref "IC19") (pin "6") (pinfunction "OUT_6") (pintype "output"))
      (node (ref "IC22") (pin "4") (pinfunction "A_4") (pintype "tri_state"))
      (node (ref "R34") (pin "2") (pinfunction "2_2") (pintype "passive"))
    )
    (net (code "129") (name "Net-(IC20-+VS)") (class "Default")
      (node (ref "C105") (pin "1") (pinfunction "1_1") (pintype "passive"))
      (node (ref "C106") (pin "+") (pinfunction "+_+") (pintype "passive"))
      (node (ref "IC20") (pin "7") (pinfunction "+VS_7") (pintype "input"))
      (node (ref "L10") (pin "2") (pinfunction "2_2") (pintype "passive"))
    )
    (net (code "130") (name "Net-(IC20-IN-)") (class "Default")
      (node (ref "C50") (pin "1") (pinfunction "1_1") (pintype "passive"))
      (node (ref "C51") (pin "1") (pinfunction "1_1") (pintype "passive"))
      (node (ref "C66") (pin "1") (pinfunction "1_1") (pintype "passive"))
      (node (ref "C67") (pin "2") (pinfunction "2_2") (pintype "passive"))
      (node (ref "IC20") (pin "2") (pinfunction "IN-_2") (pintype "input"))
      (node (ref "R41") (pin "2") (pinfunction "2_2") (pintype "passive"))
      (node (ref "R42") (pin "2") (pinfunction "2_2") (pintype "passive"))
      (node (ref "R43") (pin "2") (pinfunction "2_2") (pintype "passive"))
      (node (ref "R44") (pin "1") (pinfunction "1_1") (pintype "passive"))
    )
    (net (code "131") (name "Net-(IC20-OUT)") (class "Default")
      (node (ref "C67") (pin "1") (pinfunction "1_1") (pintype "passive"))
      (node (ref "IC20") (pin "6") (pinfunction "OUT_6") (pintype "output"))
      (node (ref "R20") (pin "1") (pinfunction "1_1") (pintype "passive"))
      (node (ref "R44") (pin "2") (pinfunction "2_2") (pintype "passive"))
    )
    (net (code "132") (name "Net-(IC21-+VS)") (class "Default")
      (node (ref "C111") (pin "1") (pinfunction "1_1") (pintype "passive"))
      (node (ref "C112") (pin "+") (pinfunction "+_+") (pintype "passive"))
      (node (ref "IC21") (pin "7") (pinfunction "+VS_7") (pintype "input"))
      (node (ref "L13") (pin "2") (pinfunction "2_2") (pintype "passive"))
    )
    (net (code "133") (name "Net-(IC21-IN+)") (class "Default")
      (node (ref "C134") (pin "1") (pinfunction "1_1") (pintype "passive"))
      (node (ref "C135") (pin "1") (pinfunction "1_1") (pintype "passive"))
      (node (ref "C52") (pin "1") (pinfunction "1_1") (pintype "passive"))
      (node (ref "IC21") (pin "3") (pinfunction "IN+_3") (pintype "input"))
      (node (ref "R36") (pin "2") (pinfunction "2_2") (pintype "passive"))
    )
    (net (code "134") (name "Net-(IC21-IN-)") (class "Default")
      (node (ref "C135") (pin "2") (pinfunction "2_2") (pintype "passive"))
      (node (ref "C53") (pin "2") (pinfunction "2_2") (pintype "passive"))
      (node (ref "C54") (pin "1") (pinfunction "1_1") (pintype "passive"))
      (node (ref "C66") (pin "2") (pinfunction "2_2") (pintype "passive"))
      (node (ref "IC21") (pin "2") (pinfunction "IN-_2") (pintype "input"))
      (node (ref "IC21") (pin "6") (pinfunction "OUT_6") (pintype "output"))
      (node (ref "IC22") (pin "8") (pinfunction "A_8") (pintype "tri_state"))
      (node (ref "R37") (pin "2") (pinfunction "2_2") (pintype "passive"))
    )
    (net (code "135") (name "Net-(IC22A-B)") (class "Default")
      (node (ref "IC22") (pin "2") (pinfunction "B_2") (pintype "tri_state"))
      (node (ref "R41") (pin "1") (pinfunction "1_1") (pintype "passive"))
    )
    (net (code "136") (name "Net-(IC22B-B)") (class "Default")
      (node (ref "IC22") (pin "3") (pinfunction "B_3") (pintype "tri_state"))
      (node (ref "R42") (pin "1") (pinfunction "1_1") (pintype "passive"))
    )
    (net (code "137") (name "Net-(IC22C-B)") (class "Default")
      (node (ref "IC22") (pin "9") (pinfunction "B_9") (pintype "tri_state"))
      (node (ref "R43") (pin "1") (pinfunction "1_1") (pintype "passive"))
    )
    (net (code "138") (name "Net-(IC22D-A)") (class "Default")
      (node (ref "C136") (pin "2") (pinfunction "2_2") (pintype "passive"))
      (node (ref "IC22") (pin "11") (pinfunction "A_11") (pintype "tri_state"))
      (node (ref "IC33") (pin "2") (pinfunction "IN-_2") (pintype "input"))
      (node (ref "Q1") (pin "1") (pinfunction "C1_1") (pintype "passive"))
      (node (ref "Q1") (pin "2") (pinfunction "C2_2") (pintype "passive"))
      (node (ref "Q1") (pin "3") (pinfunction "C1_3") (pintype "passive"))
      (node (ref "Q1") (pin "4") (pinfunction "C2_4") (pintype "passive"))
      (node (ref "Q1") (pin "5") (pinfunction "C1_5") (pintype "passive"))
      (node (ref "Q1") (pin "6") (pinfunction "C2_6") (pintype "passive"))
      (node (ref "Q1") (pin "7") (pinfunction "C1_7") (pintype "passive"))
      (node (ref "Q1") (pin "8") (pinfunction "C2_8") (pintype "passive"))
      (node (ref "Q2") (pin "1") (pinfunction "C_1") (pintype "passive"))
      (node (ref "Q2") (pin "2") (pinfunction "C2_2") (pintype "passive"))
      (node (ref "Q2") (pin "3") (pinfunction "C_3") (pintype "passive"))
      (node (ref "Q2") (pin "4") (pinfunction "C2_4") (pintype "passive"))
      (node (ref "Q2") (pin "5") (pinfunction "C_5") (pintype "passive"))
      (node (ref "Q2") (pin "6") (pinfunction "C2_6") (pintype "passive"))
      (node (ref "Q2") (pin "7") (pinfunction "C_7") (pintype "passive"))
      (node (ref "Q2") (pin "8") (pinfunction "C2_8") (pintype "passive"))
      (node (ref "R20") (pin "2") (pinfunction "2_2") (pintype "passive"))
    )
    (net (code "139") (name "Net-(IC22D-B)") (class "Default")
      (node (ref "IC22") (pin "10") (pinfunction "B_10") (pintype "tri_state"))
      (node (ref "R21") (pin "1") (pinfunction "1_1") (pintype "passive"))
    )
    (net (code "140") (name "Net-(IC23-+VS)") (class "Default")
      (node (ref "C109") (pin "1") (pinfunction "1_1") (pintype "passive"))
      (node (ref "C110") (pin "+") (pinfunction "+_+") (pintype "passive"))
      (node (ref "IC23") (pin "7") (pinfunction "+VS_7") (pintype "input"))
      (node (ref "L12") (pin "2") (pinfunction "2_2") (pintype "passive"))
    )
    (net (code "141") (name "Net-(IC23-IN+)") (class "Default")
      (node (ref "C56") (pin "1") (pinfunction "1_1") (pintype "passive"))
      (node (ref "C59") (pin "2") (pinfunction "2_2") (pintype "passive"))
      (node (ref "C63") (pin "1") (pinfunction "1_1") (pintype "passive"))
      (node (ref "IC23") (pin "3") (pinfunction "IN+_3") (pintype "input"))
      (node (ref "R38") (pin "2") (pinfunction "2_2") (pintype "passive"))
    )
    (net (code "142") (name "Net-(IC24-+VS)") (class "Default")
      (node (ref "C100") (pin "+") (pinfunction "+_+") (pintype "passive"))
      (node (ref "C99") (pin "1") (pinfunction "1_1") (pintype "passive"))
      (node (ref "IC24") (pin "7") (pinfunction "+VS_7") (pintype "input"))
      (node (ref "L7") (pin "2") (pinfunction "2_2") (pintype "passive"))
    )
    (net (code "143") (name "Net-(IC24-IN+)") (class "Default")
      (node (ref "C32") (pin "2") (pinfunction "2_2") (pintype "passive"))
      (node (ref "IC24") (pin "3") (pinfunction "IN+_3") (pintype "input"))
      (node (ref "IC25") (pin "3") (pinfunction "IN+_3") (pintype "input"))
      (node (ref "IC26") (pin "2") (pinfunction "IN-_2") (pintype "input"))
      (node (ref "IC26") (pin "6") (pinfunction "OUT_6") (pintype "output"))
      (node (ref "IC7") (pin "1") (pinfunction "A_1") (pintype "tri_state"))
    )
    (net (code "144") (name "Net-(IC24-IN-)") (class "Default")
      (node (ref "C40") (pin "1") (pinfunction "1_1") (pintype "passive"))
      (node (ref "IC24") (pin "2") (pinfunction "IN-_2") (pintype "input"))
      (node (ref "IC24") (pin "6") (pinfunction "OUT_6") (pintype "output"))
    )
    (net (code "145") (name "Net-(IC25-+VS)") (class "Default")
      (node (ref "C107") (pin "1") (pinfunction "1_1") (pintype "passive"))
      (node (ref "C108") (pin "+") (pinfunction "+_+") (pintype "passive"))
      (node (ref "IC25") (pin "7") (pinfunction "+VS_7") (pintype "input"))
      (node (ref "L11") (pin "2") (pinfunction "2_2") (pintype "passive"))
    )
    (net (code "146") (name "Net-(IC25-IN-)") (class "Default")
      (node (ref "C58") (pin "1") (pinfunction "1_1") (pintype "passive"))
      (node (ref "IC25") (pin "2") (pinfunction "IN-_2") (pintype "input"))
      (node (ref "IC25") (pin "6") (pinfunction "OUT_6") (pintype "output"))
    )
    (net (code "147") (name "Net-(IC26-+VS)") (class "Default")
      (node (ref "C97") (pin "1") (pinfunction "1_1") (pintype "passive"))
      (node (ref "C98") (pin "+") (pinfunction "+_+") (pintype "passive"))
      (node (ref "IC26") (pin "7") (pinfunction "+VS_7") (pintype "input"))
      (node (ref "L6") (pin "2") (pinfunction "2_2") (pintype "passive"))
    )
    (net (code "148") (name "Net-(IC26-IN+)") (class "Default")
      (node (ref "IC26") (pin "3") (pinfunction "IN+_3") (pintype "input"))
      (node (ref "JP5") (pin "2") (pinfunction "2_2") (pintype "passive"))
    )
    (net (code "149") (name "Net-(IC28-GND)") (class "Default")
      (node (ref "C70") (pin "-") (pinfunction "-_-") (pintype "passive"))
      (node (ref "C71") (pin "-") (pinfunction "-_-") (pintype "passive"))
      (node (ref "IC28") (pin "1") (pinfunction "GND_1") (pintype "power_in"))
      (node (ref "IC6") (pin "1") (pinfunction "GND_1") (pintype "power_in"))
      (node (ref "L2") (pin "1") (pinfunction "1_1") (pintype "passive"))
      (node (ref "L24") (pin "1") (pinfunction "1_1") (pintype "passive"))
      (node (ref "L4") (pin "1") (pinfunction "1_1") (pintype "passive"))
      (node (ref "STR_GND") (pin "1") (pinfunction "P_1") (pintype "passive"))
    )
    (net (code "150") (name "Net-(IC28-VIN)") (class "Default")
      (node (ref "IC28") (pin "3") (pinfunction "VIN_3") (pintype "power_in"))
      (node (ref "IC6") (pin "3") (pinfunction "VIN_3") (pintype "power_in"))
      (node (ref "JP7") (pin "8") (pinfunction "8_8") (pintype "passive"))
      (node (ref "PWR") (pin "1") (pinfunction "P_1") (pintype "passive"))
    )
    (net (code "151") (name "Net-(IC28-VOUT1)") (class "Default")
      (node (ref "C71") (pin "+") (pinfunction "+_+") (pintype "passive"))
      (node (ref "IC28") (pin "2") (pinfunction "VOUT1_2") (pintype "power_in"))
      (node (ref "IC28") (pin "4") (pinfunction "VOUT2_4") (pintype "power_in"))
      (node (ref "L23") (pin "1") (pinfunction "1_1") (pintype "passive"))
      (node (ref "L3") (pin "1") (pinfunction "1_1") (pintype "passive"))
    )
    (net (code "152") (name "Net-(IC33-+VS)") (class "Default")
      (node (ref "C147") (pin "1") (pinfunction "1_1") (pintype "passive"))
      (node (ref "C148") (pin "+") (pinfunction "+_+") (pintype "passive"))
      (node (ref "IC33") (pin "7") (pinfunction "+VS_7") (pintype "input"))
      (node (ref "L25") (pin "2") (pinfunction "2_2") (pintype "passive"))
    )
    (net (code "153") (name "Net-(IC33-OUT)") (class "Default")
      (node (ref "C136") (pin "1") (pinfunction "1_1") (pintype "passive"))
      (node (ref "IC33") (pin "6") (pinfunction "OUT_6") (pintype "output"))
      (node (ref "PAD2") (pin "1") (pinfunction "P_1") (pintype "passive"))
      (node (ref "R21") (pin "2") (pinfunction "2_2") (pintype "passive"))
      (node (ref "R22") (pin "2") (pinfunction "2_2") (pintype "passive"))
      (node (ref "R23") (pin "2") (pinfunction "2_2") (pintype "passive"))
      (node (ref "R24") (pin "2") (pinfunction "2_2") (pintype "passive"))
      (node (ref "R25") (pin "2") (pinfunction "2_2") (pintype "passive"))
      (node (ref "R46") (pin "1") (pinfunction "1_1") (pintype "passive"))
      (node (ref "R47") (pin "1") (pinfunction "1_1") (pintype "passive"))
      (node (ref "R48") (pin "1") (pinfunction "1_1") (pintype "passive"))
      (node (ref "R49") (pin "1") (pinfunction "1_1") (pintype "passive"))
    )
    (net (code "154") (name "Net-(IC41-CLK)") (class "Default")
      (node (ref "IC41") (pin "3") (pinfunction "CLK_3") (pintype "bidirectional"))
      (node (ref "R58") (pin "1") (pinfunction "1_1") (pintype "passive"))
      (node (ref "R59") (pin "2") (pinfunction "2_2") (pintype "passive"))
      (node (ref "U1") (pin "P70") (pinfunction "IO_L1P_CCLK_2_P70") (pintype "bidirectional"))
    )
    (net (code "155") (name "Net-(IC41-DO)") (class "Default")
      (node (ref "IC41") (pin "1") (pinfunction "DO_1") (pintype "bidirectional"))
      (node (ref "U1") (pin "P65") (pinfunction "IO_L3P_D0_DIN_MISO_MISO1_2_P65") (pintype "bidirectional"))
    )
    (net (code "156") (name "Net-(IC41-OE{slash}RESET)") (class "Default")
      (node (ref "IC41") (pin "8") (pinfunction "OE/RESET_8") (pintype "bidirectional"))
      (node (ref "R62") (pin "1") (pinfunction "1_1") (pintype "passive"))
      (node (ref "U1") (pin "P39") (pinfunction "IO_L65P_INIT_B_2_P39") (pintype "bidirectional"))
    )
    (net (code "157") (name "Net-(IC41-TCK)") (class "Default")
      (node (ref "IC41") (pin "6") (pinfunction "TCK_6") (pintype "bidirectional"))
      (node (ref "SL1") (pin "4") (pinfunction "4_4") (pintype "passive"))
      (node (ref "U1") (pin "P109") (pinfunction "TCK_P109") (pintype "bidirectional"))
    )
    (net (code "158") (name "Net-(IC41-TDI)") (class "Default")
      (node (ref "IC41") (pin "4") (pinfunction "TDI_4") (pintype "bidirectional"))
      (node (ref "SL1") (pin "2") (pinfunction "2_2") (pintype "passive"))
    )
    (net (code "159") (name "Net-(IC41-TDO)") (class "Default")
      (node (ref "IC41") (pin "17") (pinfunction "TDO_17") (pintype "bidirectional"))
      (node (ref "U1") (pin "P110") (pinfunction "TDI_P110") (pintype "bidirectional"))
    )
    (net (code "160") (name "Net-(IC41-TMS)") (class "Default")
      (node (ref "IC41") (pin "5") (pinfunction "TMS_5") (pintype "bidirectional"))
      (node (ref "SL1") (pin "1") (pinfunction "1_1") (pintype "passive"))
      (node (ref "U1") (pin "P107") (pinfunction "TMS_P107") (pintype "bidirectional"))
    )
    (net (code "161") (name "Net-(IC41-{slash}CE)") (class "Default")
      (node (ref "IC41") (pin "10") (pinfunction "/CE_10") (pintype "bidirectional"))
      (node (ref "R61") (pin "1") (pinfunction "1_1") (pintype "passive"))
      (node (ref "U1") (pin "P71") (pinfunction "DONE_2_P71") (pintype "bidirectional"))
    )
    (net (code "162") (name "Net-(IC41-{slash}CF)") (class "Default")
      (node (ref "IC41") (pin "7") (pinfunction "/CF_7") (pintype "bidirectional"))
      (node (ref "R60") (pin "1") (pinfunction "1_1") (pintype "passive"))
      (node (ref "U1") (pin "P37") (pinfunction "PROGRAM_B_2_P37") (pintype "bidirectional"))
    )
    (net (code "163") (name "Net-(JP2-Pad3)") (class "Default")
      (node (ref "JP2") (pin "3") (pinfunction "3_3") (pintype "passive"))
      (node (ref "JP6") (pin "2") (pinfunction "2_2") (pintype "passive"))
    )
    (net (code "164") (name "Net-(JP3-Pad5)") (class "Default")
      (node (ref "JP3") (pin "5") (pinfunction "5_5") (pintype "passive"))
      (node (ref "R86") (pin "1") (pinfunction "1_1") (pintype "passive"))
    )
    (net (code "165") (name "Net-(JP3-Pad6)") (class "Default")
      (node (ref "JP3") (pin "6") (pinfunction "6_6") (pintype "passive"))
      (node (ref "R87") (pin "1") (pinfunction "1_1") (pintype "passive"))
    )
    (net (code "166") (name "Net-(JP3-Pad7)") (class "Default")
      (node (ref "JP3") (pin "7") (pinfunction "7_7") (pintype "passive"))
      (node (ref "R88") (pin "1") (pinfunction "1_1") (pintype "passive"))
    )
    (net (code "167") (name "Net-(JP3-Pad8)") (class "Default")
      (node (ref "JP3") (pin "8") (pinfunction "8_8") (pintype "passive"))
      (node (ref "R89") (pin "1") (pinfunction "1_1") (pintype "passive"))
    )
    (net (code "168") (name "Net-(JP4-Pad2)") (class "Default")
      (node (ref "JP4") (pin "2") (pinfunction "2_2") (pintype "passive"))
      (node (ref "R85") (pin "1") (pinfunction "1_1") (pintype "passive"))
    )
    (net (code "169") (name "Net-(JP4-Pad5)") (class "Default")
      (node (ref "JP4") (pin "5") (pinfunction "5_5") (pintype "passive"))
      (node (ref "R84") (pin "1") (pinfunction "1_1") (pintype "passive"))
    )
    (net (code "170") (name "Net-(PAD1-P)") (class "Default")
      (node (ref "JP5") (pin "3") (pinfunction "3_3") (pintype "passive"))
      (node (ref "PAD1") (pin "1") (pinfunction "P_1") (pintype "passive"))
    )
    (net (code "171") (name "Net-(PAD3-P)") (class "Default")
      (node (ref "JP2") (pin "1") (pinfunction "1_1") (pintype "passive"))
      (node (ref "PAD3") (pin "1") (pinfunction "P_1") (pintype "passive"))
    )
    (net (code "172") (name "Net-(Q1A-B)") (class "Default")
      (node (ref "C137") (pin "1") (pinfunction "1_1") (pintype "passive"))
      (node (ref "Q1") (pin "15") (pinfunction "B_15") (pintype "passive"))
      (node (ref "R50") (pin "2") (pinfunction "2_2") (pintype "passive"))
    )
    (net (code "173") (name "Net-(Q1A-E)") (class "Default")
      (node (ref "Q1") (pin "16") (pinfunction "E_16") (pintype "passive"))
      (node (ref "R22") (pin "1") (pinfunction "1_1") (pintype "passive"))
    )
    (net (code "174") (name "Net-(Q1B-B)") (class "Default")
      (node (ref "C138") (pin "1") (pinfunction "1_1") (pintype "passive"))
      (node (ref "Q1") (pin "13") (pinfunction "B_13") (pintype "passive"))
      (node (ref "R51") (pin "2") (pinfunction "2_2") (pintype "passive"))
    )
    (net (code "175") (name "Net-(Q1B-E)") (class "Default")
      (node (ref "Q1") (pin "14") (pinfunction "E_14") (pintype "passive"))
      (node (ref "R23") (pin "1") (pinfunction "1_1") (pintype "passive"))
    )
    (net (code "176") (name "Net-(Q1C-B)") (class "Default")
      (node (ref "C139") (pin "1") (pinfunction "1_1") (pintype "passive"))
      (node (ref "Q1") (pin "11") (pinfunction "B_11") (pintype "passive"))
      (node (ref "R52") (pin "2") (pinfunction "2_2") (pintype "passive"))
    )
    (net (code "177") (name "Net-(Q1C-E)") (class "Default")
      (node (ref "Q1") (pin "12") (pinfunction "E_12") (pintype "passive"))
      (node (ref "R24") (pin "1") (pinfunction "1_1") (pintype "passive"))
    )
    (net (code "178") (name "Net-(Q1D-B)") (class "Default")
      (node (ref "C140") (pin "1") (pinfunction "1_1") (pintype "passive"))
      (node (ref "Q1") (pin "9") (pinfunction "B_9") (pintype "passive"))
      (node (ref "R53") (pin "2") (pinfunction "2_2") (pintype "passive"))
    )
    (net (code "179") (name "Net-(Q1D-E)") (class "Default")
      (node (ref "Q1") (pin "10") (pinfunction "E_10") (pintype "passive"))
      (node (ref "R25") (pin "1") (pinfunction "1_1") (pintype "passive"))
    )
    (net (code "180") (name "Net-(Q2A-B)") (class "Default")
      (node (ref "C141") (pin "1") (pinfunction "1_1") (pintype "passive"))
      (node (ref "Q2") (pin "15") (pinfunction "B_15") (pintype "passive"))
      (node (ref "R54") (pin "2") (pinfunction "2_2") (pintype "passive"))
    )
    (net (code "181") (name "Net-(Q2A-E)") (class "Default")
      (node (ref "Q2") (pin "16") (pinfunction "E_16") (pintype "passive"))
      (node (ref "R46") (pin "2") (pinfunction "2_2") (pintype "passive"))
    )
    (net (code "182") (name "Net-(Q2B-B)") (class "Default")
      (node (ref "C142") (pin "1") (pinfunction "1_1") (pintype "passive"))
      (node (ref "Q2") (pin "13") (pinfunction "B_13") (pintype "passive"))
      (node (ref "R55") (pin "2") (pinfunction "2_2") (pintype "passive"))
    )
    (net (code "183") (name "Net-(Q2B-E)") (class "Default")
      (node (ref "Q2") (pin "14") (pinfunction "E_14") (pintype "passive"))
      (node (ref "R47") (pin "2") (pinfunction "2_2") (pintype "passive"))
    )
    (net (code "184") (name "Net-(Q2C-B)") (class "Default")
      (node (ref "C143") (pin "1") (pinfunction "1_1") (pintype "passive"))
      (node (ref "Q2") (pin "11") (pinfunction "B_11") (pintype "passive"))
      (node (ref "R56") (pin "2") (pinfunction "2_2") (pintype "passive"))
    )
    (net (code "185") (name "Net-(Q2C-E)") (class "Default")
      (node (ref "Q2") (pin "12") (pinfunction "E_12") (pintype "passive"))
      (node (ref "R48") (pin "2") (pinfunction "2_2") (pintype "passive"))
    )
    (net (code "186") (name "Net-(Q2D-B)") (class "Default")
      (node (ref "C144") (pin "1") (pinfunction "1_1") (pintype "passive"))
      (node (ref "Q2") (pin "9") (pinfunction "B_9") (pintype "passive"))
      (node (ref "R57") (pin "2") (pinfunction "2_2") (pintype "passive"))
    )
    (net (code "187") (name "Net-(Q2D-E)") (class "Default")
      (node (ref "Q2") (pin "10") (pinfunction "E_10") (pintype "passive"))
      (node (ref "R49") (pin "2") (pinfunction "2_2") (pintype "passive"))
    )
    (net (code "188") (name "Net-(QG1-FO)") (class "Default")
      (node (ref "QG1") (pin "3") (pinfunction "FO_3") (pintype "output"))
      (node (ref "U1") (pin "P55") (pinfunction "IO_L30N_GCLK0_USERCCLK_2_P55") (pintype "bidirectional"))
    )
    (net (code "189") (name "Net-(R16-Pad1)") (class "Default")
      (node (ref "R16") (pin "1") (pinfunction "1_1") (pintype "passive"))
      (node (ref "R70") (pin "S") (pinfunction "S_S") (pintype "passive"))
    )
    (net (code "190") (name "Net-(R17-Pad1)") (class "Default")
      (node (ref "R17") (pin "1") (pinfunction "1_1") (pintype "passive"))
      (node (ref "R18") (pin "S") (pinfunction "S_S") (pintype "passive"))
    )
    (net (code "191") (name "Net-(S1-P)") (class "Default")
      (node (ref "C13") (pin "1") (pinfunction "1_1") (pintype "passive"))
      (node (ref "JP7") (pin "3") (pinfunction "3_3") (pintype "passive"))
      (node (ref "R83") (pin "2") (pinfunction "2_2") (pintype "passive"))
      (node (ref "R96") (pin "2") (pinfunction "2_2") (pintype "passive"))
      (node (ref "S1") (pin "3") (pinfunction "P_3") (pintype "passive"))
      (node (ref "S1") (pin "4") (pinfunction "P1_4") (pintype "passive"))
    )
    (net (code "192") (name "Net-(U1A-IO_L4P_0)") (class "Default")
      (node (ref "R96") (pin "1") (pinfunction "1_1") (pintype "passive"))
      (node (ref "R97") (pin "2") (pinfunction "2_2") (pintype "passive"))
      (node (ref "U1") (pin "P138") (pinfunction "IO_L4P_0_P138") (pintype "bidirectional"))
    )
    (net (code "193") (name "Net-(U1B-IO_L33N_1)") (class "Default")
      (node (ref "R9") (pin "1") (pinfunction "1_1") (pintype "passive"))
      (node (ref "U1") (pin "P99") (pinfunction "IO_L33N_1_P99") (pintype "bidirectional"))
    )
    (net (code "194") (name "Net-(U1B-IO_L34N_1)") (class "Default")
      (node (ref "R10") (pin "1") (pinfunction "1_1") (pintype "passive"))
      (node (ref "U1") (pin "P97") (pinfunction "IO_L34N_1_P97") (pintype "bidirectional"))
    )
    (net (code "195") (name "Net-(U1B-IO_L41N_GCLK8_1)") (class "Default")
      (node (ref "R13") (pin "1") (pinfunction "1_1") (pintype "passive"))
      (node (ref "U1") (pin "P92") (pinfunction "IO_L41N_GCLK8_1_P92") (pintype "bidirectional"))
    )
    (net (code "196") (name "Net-(U1B-IO_L42N_GCLK6_TRDY1_1)") (class "Default")
      (node (ref "R74") (pin "1") (pinfunction "1_1") (pintype "passive"))
      (node (ref "U1") (pin "P87") (pinfunction "IO_L42N_GCLK6_TRDY1_1_P87") (pintype "bidirectional"))
    )
    (net (code "197") (name "Net-(U1B-IO_L45N_1)") (class "Default")
      (node (ref "R11") (pin "1") (pinfunction "1_1") (pintype "passive"))
      (node (ref "U1") (pin "P82") (pinfunction "IO_L45N_1_P82") (pintype "bidirectional"))
    )
    (net (code "198") (name "Net-(U1B-IO_L47N_1)") (class "Default")
      (node (ref "R12") (pin "1") (pinfunction "1_1") (pintype "passive"))
      (node (ref "U1") (pin "P78") (pinfunction "IO_L47N_1_P78") (pintype "bidirectional"))
    )
    (net (code "199") (name "Net-(U1D-IO_L41P_GCLK27_3)") (class "Default")
      (node (ref "R82") (pin "1") (pinfunction "1_1") (pintype "passive"))
      (node (ref "U1") (pin "P24") (pinfunction "IO_L41P_GCLK27_3_P24") (pintype "bidirectional"))
    )
    (net (code "200") (name "Net-(U1D-IO_L42N_GCLK24_3)") (class "Default")
      (node (ref "R81") (pin "1") (pinfunction "1_1") (pintype "passive"))
      (node (ref "U1") (pin "P21") (pinfunction "IO_L42N_GCLK24_3_P21") (pintype "bidirectional"))
    )
    (net (code "201") (name "Net-(U1D-IO_L43P_GCLK23_3)") (class "Default")
      (node (ref "R80") (pin "1") (pinfunction "1_1") (pintype "passive"))
      (node (ref "U1") (pin "P17") (pinfunction "IO_L43P_GCLK23_3_P17") (pintype "bidirectional"))
    )
    (net (code "202") (name "Net-(U1D-IO_L44N_GCLK20_3)") (class "Default")
      (node (ref "R79") (pin "1") (pinfunction "1_1") (pintype "passive"))
      (node (ref "U1") (pin "P14") (pinfunction "IO_L44N_GCLK20_3_P14") (pintype "bidirectional"))
    )
    (net (code "203") (name "Net-(U1D-IO_L49N_3)") (class "Default")
      (node (ref "R78") (pin "1") (pinfunction "1_1") (pintype "passive"))
      (node (ref "U1") (pin "P11") (pinfunction "IO_L49N_3_P11") (pintype "bidirectional"))
    )
    (net (code "204") (name "Net-(U1D-IO_L51P_3)") (class "Default")
      (node (ref "R77") (pin "1") (pinfunction "1_1") (pintype "passive"))
      (node (ref "U1") (pin "P8") (pinfunction "IO_L51P_3_P8") (pintype "bidirectional"))
    )
    (net (code "205") (name "Net-(U1D-IO_L52N_3)") (class "Default")
      (node (ref "R76") (pin "1") (pinfunction "1_1") (pintype "passive"))
      (node (ref "U1") (pin "P5") (pinfunction "IO_L52N_3_P5") (pintype "bidirectional"))
    )
    (net (code "206") (name "Net-(U1D-IO_L83N_VREF_3)") (class "Default")
      (node (ref "R75") (pin "1") (pinfunction "1_1") (pintype "passive"))
      (node (ref "U1") (pin "P1") (pinfunction "IO_L83N_VREF_3_P1") (pintype "bidirectional"))
    )
    (net (code "207") (name "Net-(U1F-TDO)") (class "Default")
      (node (ref "SL1") (pin "3") (pinfunction "3_3") (pintype "passive"))
      (node (ref "U1") (pin "P106") (pinfunction "TDO_P106") (pintype "bidirectional"))
    )
    (net (code "208") (name "VCC") (class "Default")
      (node (ref "C29") (pin "+") (pinfunction "+_+") (pintype "passive"))
      (node (ref "C30") (pin "1") (pinfunction "1_1") (pintype "passive"))
      (node (ref "C31") (pin "1") (pinfunction "1_1") (pintype "passive"))
      (node (ref "C73") (pin "1") (pinfunction "1_1") (pintype "passive"))
      (node (ref "C74") (pin "1") (pinfunction "1_1") (pintype "passive"))
      (node (ref "C76") (pin "1") (pinfunction "1_1") (pintype "passive"))
      (node (ref "C77") (pin "1") (pinfunction "1_1") (pintype "passive"))
      (node (ref "IC16") (pin "14") (pinfunction "VDD_14") (pintype "power_in"))
      (node (ref "IC18") (pin "14") (pinfunction "VDD_14") (pintype "power_in"))
      (node (ref "IC2") (pin "14") (pinfunction "VDD_14") (pintype "power_in"))
      (node (ref "IC22") (pin "14") (pinfunction "VDD_14") (pintype "power_in"))
      (node (ref "IC3") (pin "14") (pinfunction "VDD_14") (pintype "power_in"))
      (node (ref "IC7") (pin "14") (pinfunction "VDD_14") (pintype "power_in"))
      (node (ref "L15") (pin "1") (pinfunction "1_1") (pintype "passive"))
      (node (ref "L17") (pin "1") (pinfunction "1_1") (pintype "passive"))
      (node (ref "L19") (pin "1") (pinfunction "1_1") (pintype "passive"))
      (node (ref "L20") (pin "1") (pinfunction "1_1") (pintype "passive"))
      (node (ref "L21") (pin "1") (pinfunction "1_1") (pintype "passive"))
      (node (ref "L22") (pin "1") (pinfunction "1_1") (pintype "passive"))
      (node (ref "L3") (pin "2") (pinfunction "2_2") (pintype "passive"))
    )
    (net (code "209") (name "unconnected-(IC5D-A-Pad11)") (class "Default")
      (node (ref "IC5") (pin "11") (pinfunction "A_11") (pintype "tri_state"))
    )
    (net (code "210") (name "unconnected-(IC5D-B-Pad10)") (class "Default")
      (node (ref "IC5") (pin "10") (pinfunction "B_10") (pintype "tri_state"))
    )
    (net (code "211") (name "unconnected-(IC7C-A-Pad8)") (class "Default")
      (node (ref "IC7") (pin "8") (pinfunction "A_8") (pintype "tri_state"))
    )
    (net (code "212") (name "unconnected-(IC7C-B-Pad9)") (class "Default")
      (node (ref "IC7") (pin "9") (pinfunction "B_9") (pintype "tri_state"))
    )
    (net (code "213") (name "unconnected-(IC7D-A-Pad11)") (class "Default")
      (node (ref "IC7") (pin "11") (pinfunction "A_11") (pintype "tri_state"))
    )
    (net (code "214") (name "unconnected-(IC7D-B-Pad10)") (class "Default")
      (node (ref "IC7") (pin "10") (pinfunction "B_10") (pintype "tri_state"))
    )
    (net (code "215") (name "unconnected-(IC41-NC1-Pad2)") (class "Default")
      (node (ref "IC41") (pin "2") (pinfunction "NC1_2") (pintype "no_connect"))
    )
    (net (code "216") (name "unconnected-(IC41-NC2-Pad9)") (class "Default")
      (node (ref "IC41") (pin "9") (pinfunction "NC2_9") (pintype "no_connect"))
    )
    (net (code "217") (name "unconnected-(IC41-NC3-Pad12)") (class "Default")
      (node (ref "IC41") (pin "12") (pinfunction "NC3_12") (pintype "no_connect"))
    )
    (net (code "218") (name "unconnected-(IC41-NC4-Pad14)") (class "Default")
      (node (ref "IC41") (pin "14") (pinfunction "NC4_14") (pintype "no_connect"))
    )
    (net (code "219") (name "unconnected-(IC41-NC5-Pad15)") (class "Default")
      (node (ref "IC41") (pin "15") (pinfunction "NC5_15") (pintype "no_connect"))
    )
    (net (code "220") (name "unconnected-(IC41-NC6-Pad16)") (class "Default")
      (node (ref "IC41") (pin "16") (pinfunction "NC6_16") (pintype "no_connect"))
    )
    (net (code "221") (name "unconnected-(IC41-{slash}CEO-Pad13)") (class "Default")
      (node (ref "IC41") (pin "13") (pinfunction "/CEO_13") (pintype "bidirectional"))
    )
    (net (code "222") (name "unconnected-(JP1-Pad1)") (class "Default")
      (node (ref "JP1") (pin "1") (pinfunction "1_1") (pintype "passive"))
    )
    (net (code "223") (name "unconnected-(JP1-Pad2)") (class "Default")
      (node (ref "JP1") (pin "2") (pinfunction "2_2") (pintype "passive"))
    )
    (net (code "224") (name "unconnected-(JP1-Pad3)") (class "Default")
      (node (ref "JP1") (pin "3") (pinfunction "3_3") (pintype "passive"))
    )
    (net (code "225") (name "unconnected-(JP1-Pad4)") (class "Default")
      (node (ref "JP1") (pin "4") (pinfunction "4_4") (pintype "passive"))
    )
    (net (code "226") (name "unconnected-(JP1-Pad5)") (class "Default")
      (node (ref "JP1") (pin "5") (pinfunction "5_5") (pintype "passive"))
    )
    (net (code "227") (name "unconnected-(JP1-Pad6)") (class "Default")
      (node (ref "JP1") (pin "6") (pinfunction "6_6") (pintype "passive"))
    )
    (net (code "228") (name "unconnected-(JP4-Pad8)") (class "Default")
      (node (ref "JP4") (pin "8") (pinfunction "8_8") (pintype "passive"))
    )
    (net (code "229") (name "unconnected-(JP4-Pad9)") (class "Default")
      (node (ref "JP4") (pin "9") (pinfunction "9_9") (pintype "passive"))
    )
    (net (code "230") (name "unconnected-(JP4-Pad10)") (class "Default")
      (node (ref "JP4") (pin "10") (pinfunction "10_10") (pintype "passive"))
    )
    (net (code "231") (name "unconnected-(JP7-Pad1)") (class "Default")
      (node (ref "JP7") (pin "1") (pinfunction "1_1") (pintype "passive"))
    )
    (net (code "232") (name "unconnected-(JP7-Pad2)") (class "Default")
      (node (ref "JP7") (pin "2") (pinfunction "2_2") (pintype "passive"))
    )
    (net (code "233") (name "unconnected-(JP7-Pad4)") (class "Default")
      (node (ref "JP7") (pin "4") (pinfunction "4_4") (pintype "passive"))
    )
    (net (code "234") (name "unconnected-(JP7-Pad5)") (class "Default")
      (node (ref "JP7") (pin "5") (pinfunction "5_5") (pintype "passive"))
    )
    (net (code "235") (name "unconnected-(R70-PadA)") (class "Default")
      (node (ref "R70") (pin "A") (pinfunction "A_A") (pintype "passive"))
    )
    (net (code "236") (name "unconnected-(U1A-IO_L1N_VREF_0-PadP143)") (class "Default")
      (node (ref "U1") (pin "P143") (pinfunction "IO_L1N_VREF_0_P143") (pintype "bidirectional"))
    )
    (net (code "237") (name "unconnected-(U1A-IO_L2N_0-PadP141)") (class "Default")
      (node (ref "U1") (pin "P141") (pinfunction "IO_L2N_0_P141") (pintype "bidirectional"))
    )
    (net (code "238") (name "unconnected-(U1A-IO_L2P_0-PadP142)") (class "Default")
      (node (ref "U1") (pin "P142") (pinfunction "IO_L2P_0_P142") (pintype "bidirectional"))
    )
    (net (code "239") (name "unconnected-(U1A-IO_L3N_0-PadP139)") (class "Default")
      (node (ref "U1") (pin "P139") (pinfunction "IO_L3N_0_P139") (pintype "bidirectional"))
    )
    (net (code "240") (name "unconnected-(U1A-IO_L3P_0-PadP140)") (class "Default")
      (node (ref "U1") (pin "P140") (pinfunction "IO_L3P_0_P140") (pintype "bidirectional"))
    )
    (net (code "241") (name "unconnected-(U1A-IO_L4N_0-PadP137)") (class "Default")
      (node (ref "U1") (pin "P137") (pinfunction "IO_L4N_0_P137") (pintype "bidirectional"))
    )
    (net (code "242") (name "unconnected-(U1A-IO_L34P_GCLK19_0-PadP134)") (class "Default")
      (node (ref "U1") (pin "P134") (pinfunction "IO_L34P_GCLK19_0_P134") (pintype "bidirectional"))
    )
    (net (code "243") (name "unconnected-(U1A-IO_L62P_0-PadP121)") (class "Default")
      (node (ref "U1") (pin "P121") (pinfunction "IO_L62P_0_P121") (pintype "bidirectional"))
    )
    (net (code "244") (name "unconnected-(U1A-IO_L63N_SCP6_0-PadP118)") (class "Default")
      (node (ref "U1") (pin "P118") (pinfunction "IO_L63N_SCP6_0_P118") (pintype "bidirectional"))
    )
    (net (code "245") (name "unconnected-(U1A-IO_L63P_SCP7_0-PadP119)") (class "Default")
      (node (ref "U1") (pin "P119") (pinfunction "IO_L63P_SCP7_0_P119") (pintype "bidirectional"))
    )
    (net (code "246") (name "unconnected-(U1B-IO_L1N_VREF_1-PadP104)") (class "Default")
      (node (ref "U1") (pin "P104") (pinfunction "IO_L1N_VREF_1_P104") (pintype "bidirectional"))
    )
    (net (code "247") (name "unconnected-(U1B-IO_L1P_1-PadP105)") (class "Default")
      (node (ref "U1") (pin "P105") (pinfunction "IO_L1P_1_P105") (pintype "bidirectional"))
    )
    (net (code "248") (name "unconnected-(U1B-IO_L32N_1-PadP101)") (class "Default")
      (node (ref "U1") (pin "P101") (pinfunction "IO_L32N_1_P101") (pintype "bidirectional"))
    )
    (net (code "249") (name "unconnected-(U1B-IO_L32P_1-PadP102)") (class "Default")
      (node (ref "U1") (pin "P102") (pinfunction "IO_L32P_1_P102") (pintype "bidirectional"))
    )
    (net (code "250") (name "unconnected-(U1B-IO_L33P_1-PadP100)") (class "Default")
      (node (ref "U1") (pin "P100") (pinfunction "IO_L33P_1_P100") (pintype "bidirectional"))
    )
    (net (code "251") (name "unconnected-(U1B-IO_L34P_1-PadP98)") (class "Default")
      (node (ref "U1") (pin "P98") (pinfunction "IO_L34P_1_P98") (pintype "bidirectional"))
    )
    (net (code "252") (name "unconnected-(U1B-IO_L40P_GCLK11_1-PadP95)") (class "Default")
      (node (ref "U1") (pin "P95") (pinfunction "IO_L40P_GCLK11_1_P95") (pintype "bidirectional"))
    )
    (net (code "253") (name "unconnected-(U1B-IO_L41P_GCLK9_IRDY1_1-PadP93)") (class "Default")
      (node (ref "U1") (pin "P93") (pinfunction "IO_L41P_GCLK9_IRDY1_1_P93") (pintype "bidirectional"))
    )
    (net (code "254") (name "unconnected-(U1B-IO_L42P_GCLK7_1-PadP88)") (class "Default")
      (node (ref "U1") (pin "P88") (pinfunction "IO_L42P_GCLK7_1_P88") (pintype "bidirectional"))
    )
    (net (code "255") (name "unconnected-(U1B-IO_L43P_GCLK5_1-PadP85)") (class "Default")
      (node (ref "U1") (pin "P85") (pinfunction "IO_L43P_GCLK5_1_P85") (pintype "bidirectional"))
    )
    (net (code "256") (name "unconnected-(U1B-IO_L45P_1-PadP83)") (class "Default")
      (node (ref "U1") (pin "P83") (pinfunction "IO_L45P_1_P83") (pintype "bidirectional"))
    )
    (net (code "257") (name "unconnected-(U1B-IO_L46P_1-PadP81)") (class "Default")
      (node (ref "U1") (pin "P81") (pinfunction "IO_L46P_1_P81") (pintype "bidirectional"))
    )
    (net (code "258") (name "unconnected-(U1B-IO_L47P_1-PadP79)") (class "Default")
      (node (ref "U1") (pin "P79") (pinfunction "IO_L47P_1_P79") (pintype "bidirectional"))
    )
    (net (code "259") (name "unconnected-(U1B-IO_L74P_AWAKE_1-PadP75)") (class "Default")
      (node (ref "U1") (pin "P75") (pinfunction "IO_L74P_AWAKE_1_P75") (pintype "bidirectional"))
    )
    (net (code "260") (name "unconnected-(U1C-CMPCS_B_2-PadP72)") (class "Default")
      (node (ref "U1") (pin "P72") (pinfunction "CMPCS_B_2_P72") (pintype "bidirectional"))
    )
    (net (code "261") (name "unconnected-(U1C-IO_L30P_GCLK1_D13_2-PadP56)") (class "Default")
      (node (ref "U1") (pin "P56") (pinfunction "IO_L30P_GCLK1_D13_2_P56") (pintype "bidirectional"))
    )
    (net (code "262") (name "unconnected-(U1C-IO_L31N_GCLK30_D15_2-PadP50)") (class "Default")
      (node (ref "U1") (pin "P50") (pinfunction "IO_L31N_GCLK30_D15_2_P50") (pintype "bidirectional"))
    )
    (net (code "263") (name "unconnected-(U1C-IO_L31P_GCLK31_D14_2-PadP51)") (class "Default")
      (node (ref "U1") (pin "P51") (pinfunction "IO_L31P_GCLK31_D14_2_P51") (pintype "bidirectional"))
    )
    (net (code "264") (name "unconnected-(U1C-IO_L48N_RDWR_B_VREF_2-PadP47)") (class "Default")
      (node (ref "U1") (pin "P47") (pinfunction "IO_L48N_RDWR_B_VREF_2_P47") (pintype "bidirectional"))
    )
    (net (code "265") (name "unconnected-(U1C-IO_L48P_D7_2-PadP48)") (class "Default")
      (node (ref "U1") (pin "P48") (pinfunction "IO_L48P_D7_2_P48") (pintype "bidirectional"))
    )
    (net (code "266") (name "unconnected-(U1C-IO_L49N_D4_2-PadP45)") (class "Default")
      (node (ref "U1") (pin "P45") (pinfunction "IO_L49N_D4_2_P45") (pintype "bidirectional"))
    )
    (net (code "267") (name "unconnected-(U1C-IO_L49P_D3_2-PadP46)") (class "Default")
      (node (ref "U1") (pin "P46") (pinfunction "IO_L49P_D3_2_P46") (pintype "bidirectional"))
    )
    (net (code "268") (name "unconnected-(U1C-IO_L62N_D6_2-PadP43)") (class "Default")
      (node (ref "U1") (pin "P43") (pinfunction "IO_L62N_D6_2_P43") (pintype "bidirectional"))
    )
    (net (code "269") (name "unconnected-(U1C-IO_L62P_D5_2-PadP44)") (class "Default")
      (node (ref "U1") (pin "P44") (pinfunction "IO_L62P_D5_2_P44") (pintype "bidirectional"))
    )
    (net (code "270") (name "unconnected-(U1C-IO_L64P_D8_2-PadP41)") (class "Default")
      (node (ref "U1") (pin "P41") (pinfunction "IO_L64P_D8_2_P41") (pintype "bidirectional"))
    )
    (net (code "271") (name "unconnected-(U1C-IO_L65N_CSO_B_2-PadP38)") (class "Default")
      (node (ref "U1") (pin "P38") (pinfunction "IO_L65N_CSO_B_2_P38") (pintype "bidirectional"))
    )
    (net (code "272") (name "unconnected-(U1D-IO_L1N_VREF_3-PadP34)") (class "Default")
      (node (ref "U1") (pin "P34") (pinfunction "IO_L1N_VREF_3_P34") (pintype "bidirectional"))
    )
    (net (code "273") (name "unconnected-(U1D-IO_L1P_3-PadP35)") (class "Default")
      (node (ref "U1") (pin "P35") (pinfunction "IO_L1P_3_P35") (pintype "bidirectional"))
    )
    (net (code "274") (name "unconnected-(U1D-IO_L2N_3-PadP32)") (class "Default")
      (node (ref "U1") (pin "P32") (pinfunction "IO_L2N_3_P32") (pintype "bidirectional"))
    )
    (net (code "275") (name "unconnected-(U1D-IO_L2P_3-PadP33)") (class "Default")
      (node (ref "U1") (pin "P33") (pinfunction "IO_L2P_3_P33") (pintype "bidirectional"))
    )
    (net (code "276") (name "unconnected-(U1D-IO_L36N_3-PadP29)") (class "Default")
      (node (ref "U1") (pin "P29") (pinfunction "IO_L36N_3_P29") (pintype "bidirectional"))
    )
    (net (code "277") (name "unconnected-(U1D-IO_L36P_3-PadP30)") (class "Default")
      (node (ref "U1") (pin "P30") (pinfunction "IO_L36P_3_P30") (pintype "bidirectional"))
    )
    (net (code "278") (name "unconnected-(U1D-IO_L37N_3-PadP26)") (class "Default")
      (node (ref "U1") (pin "P26") (pinfunction "IO_L37N_3_P26") (pintype "bidirectional"))
    )
    (net (code "279") (name "unconnected-(U1D-IO_L37P_3-PadP27)") (class "Default")
      (node (ref "U1") (pin "P27") (pinfunction "IO_L37P_3_P27") (pintype "bidirectional"))
    )
    (net (code "280") (name "unconnected-(U1D-IO_L41N_GCLK26_3-PadP23)") (class "Default")
      (node (ref "U1") (pin "P23") (pinfunction "IO_L41N_GCLK26_3_P23") (pintype "bidirectional"))
    )
    (net (code "281") (name "unconnected-(U1D-IO_L42P_GCLK25_TRDY2_3-PadP22)") (class "Default")
      (node (ref "U1") (pin "P22") (pinfunction "IO_L42P_GCLK25_TRDY2_3_P22") (pintype "bidirectional"))
    )
    (net (code "282") (name "unconnected-(U1D-IO_L43N_GCLK22_IRDY2_3-PadP16)") (class "Default")
      (node (ref "U1") (pin "P16") (pinfunction "IO_L43N_GCLK22_IRDY2_3_P16") (pintype "bidirectional"))
    )
    (net (code "283") (name "unconnected-(U1D-IO_L44P_GCLK21_3-PadP15)") (class "Default")
      (node (ref "U1") (pin "P15") (pinfunction "IO_L44P_GCLK21_3_P15") (pintype "bidirectional"))
    )
    (net (code "284") (name "unconnected-(U1D-IO_L49P_3-PadP12)") (class "Default")
      (node (ref "U1") (pin "P12") (pinfunction "IO_L49P_3_P12") (pintype "bidirectional"))
    )
    (net (code "285") (name "unconnected-(U1D-IO_L50N_3-PadP9)") (class "Default")
      (node (ref "U1") (pin "P9") (pinfunction "IO_L50N_3_P9") (pintype "bidirectional"))
    )
    (net (code "286") (name "unconnected-(U1D-IO_L50P_3-PadP10)") (class "Default")
      (node (ref "U1") (pin "P10") (pinfunction "IO_L50P_3_P10") (pintype "bidirectional"))
    )
    (net (code "287") (name "unconnected-(U1D-IO_L51N_3-PadP7)") (class "Default")
      (node (ref "U1") (pin "P7") (pinfunction "IO_L51N_3_P7") (pintype "bidirectional"))
    )
    (net (code "288") (name "unconnected-(U1D-IO_L52P_3-PadP6)") (class "Default")
      (node (ref "U1") (pin "P6") (pinfunction "IO_L52P_3_P6") (pintype "bidirectional"))
    )
    (net (code "289") (name "unconnected-(U1D-IO_L83P_3-PadP2)") (class "Default")
      (node (ref "U1") (pin "P2") (pinfunction "IO_L83P_3_P2") (pintype "bidirectional"))
    )
    (net (code "290") (name "unconnected-(U1F-SUSPEND-PadP73)") (class "Default")
      (node (ref "U1") (pin "P73") (pinfunction "SUSPEND_P73") (pintype "bidirectional"))
    )
  )
)
